# UCirKitBreadboardWithEverything2Top.net
KiCad netlist of a schematic drawn in EAGLE
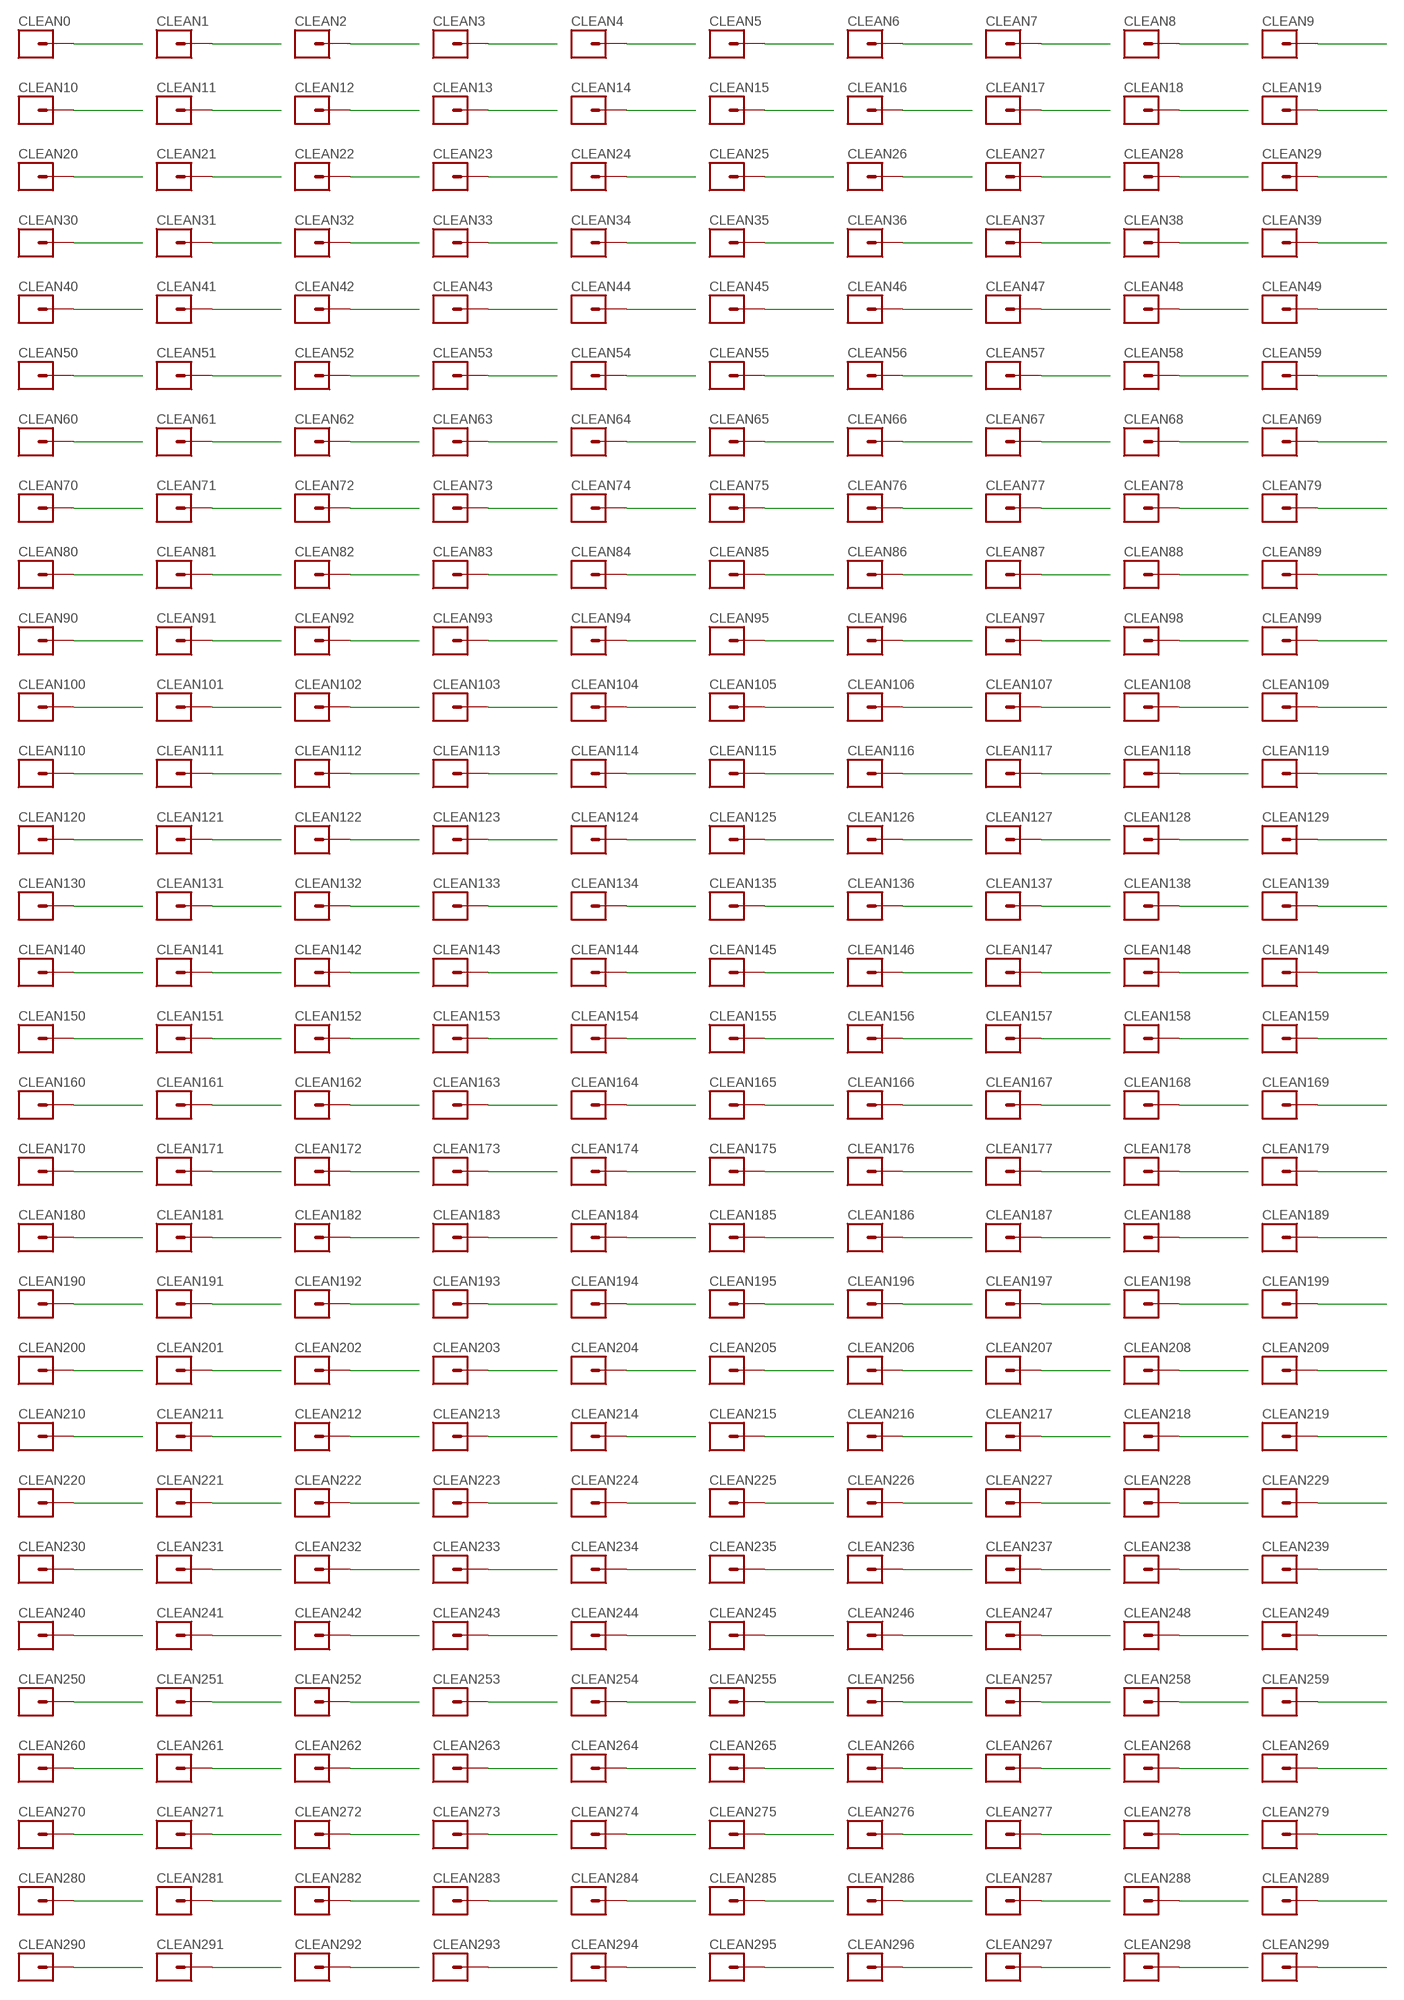
[diagram p0: schematic, sheet 1, part 1 of 2]
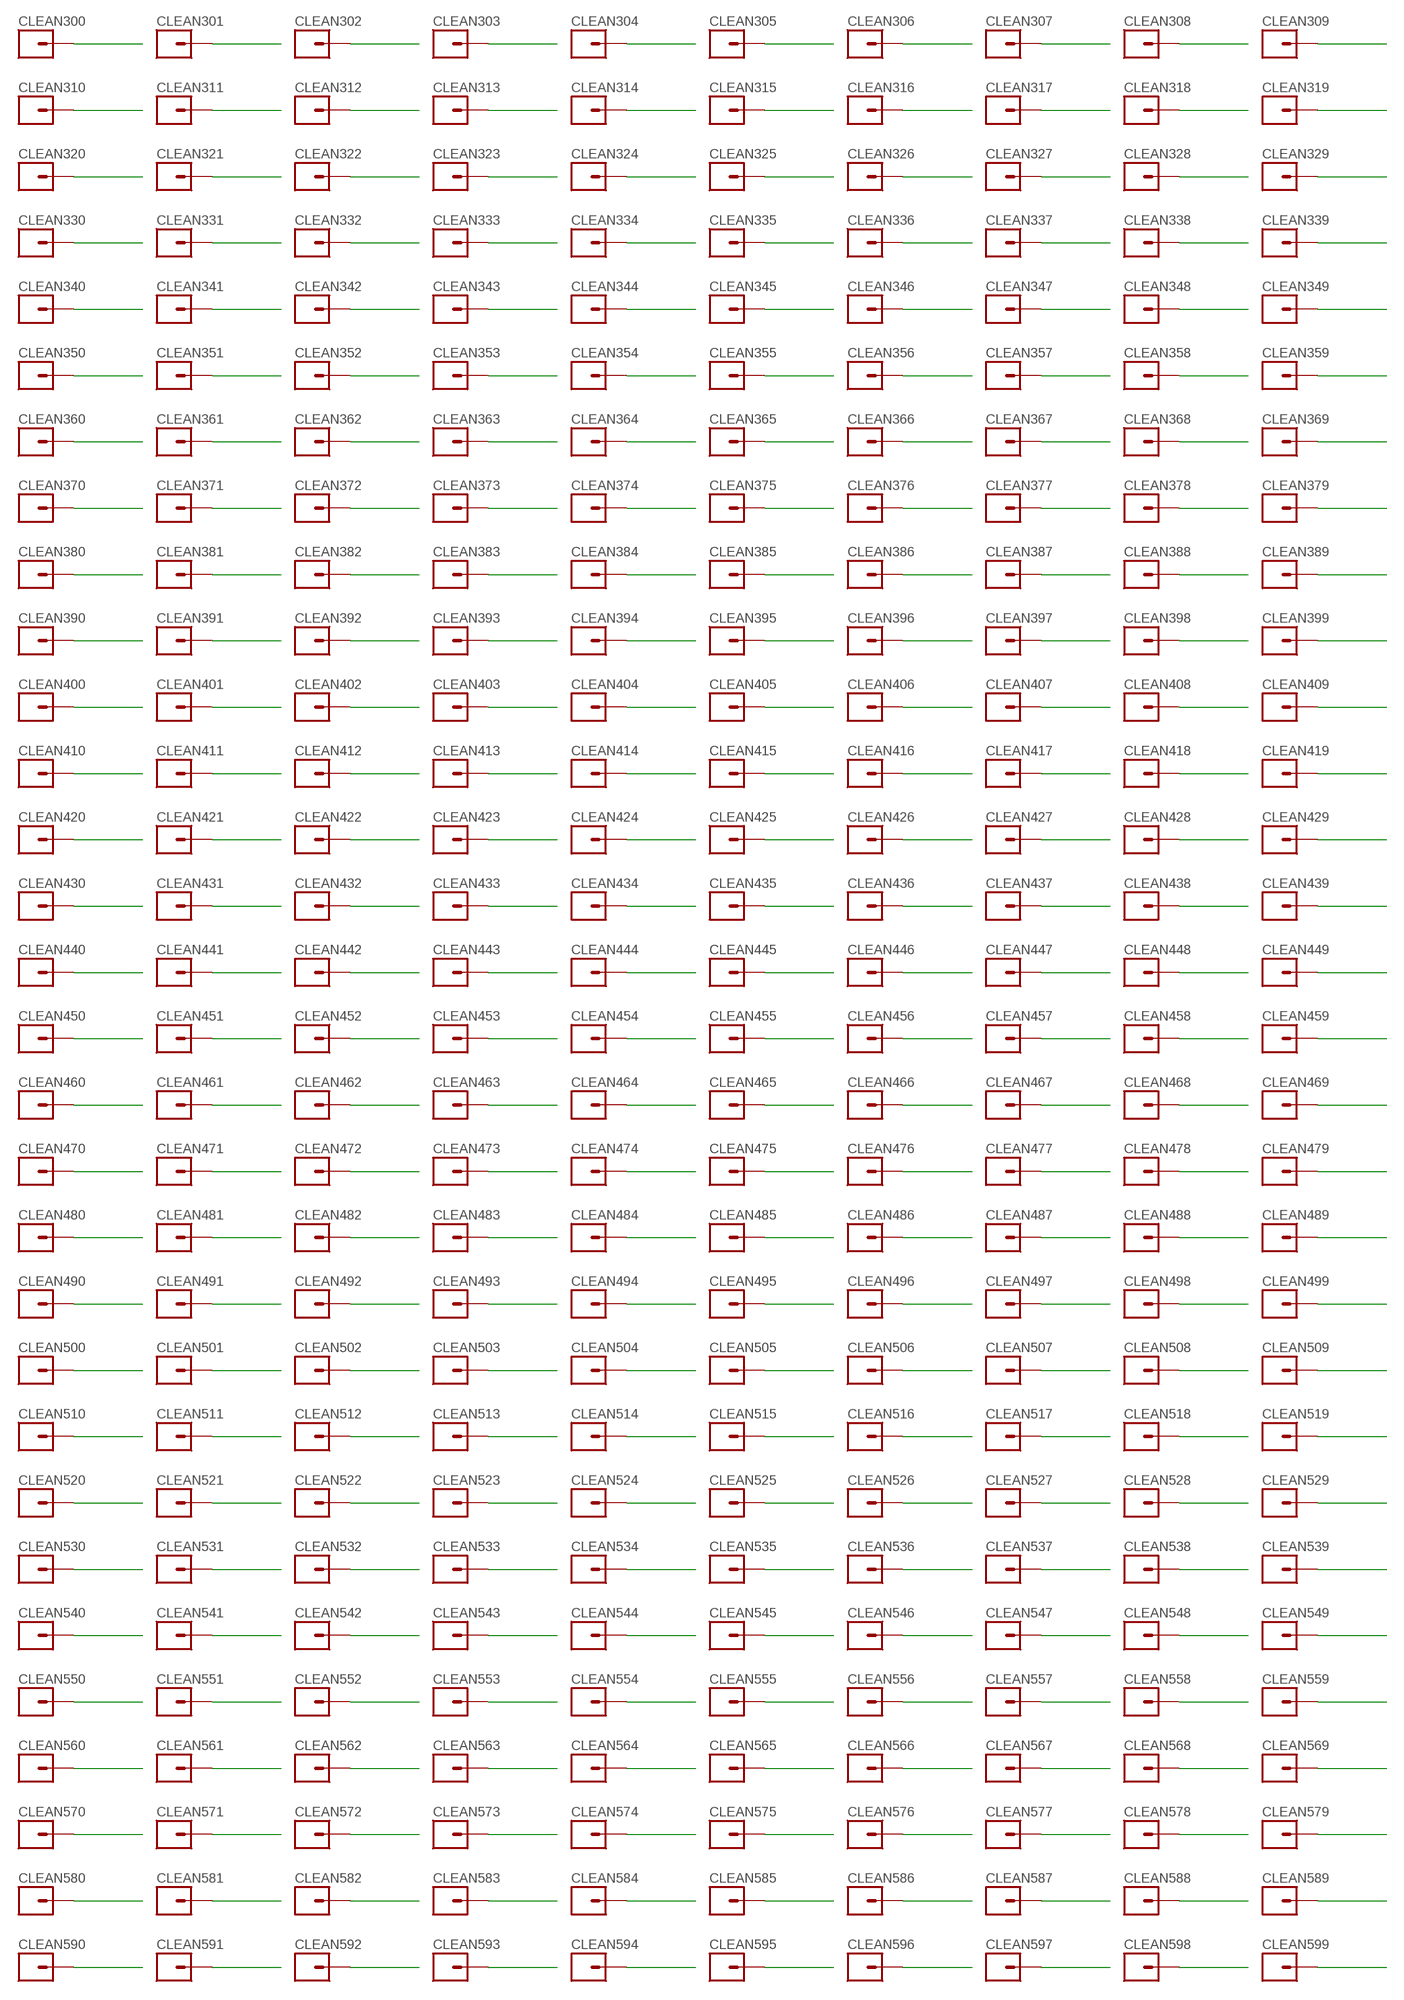
[diagram p1: schematic, sheet 1, part 2 of 2]

(export (version "E")
  (design (tool "Eeschema 10.0.6"))
  (components
    (comp (ref "CLEAN0")
      (value "M01PTH_WITHOUT_TEXT")
      (footprint "eagle-import:1X01_WITHOUT_TEXT")
      (libsource (lib "eagle-import") (part "M01PTH_WITHOUT_TEXT"))
    )
    (comp (ref "CLEAN1")
      (value "M01PTH_WITHOUT_TEXT")
      (footprint "eagle-import:1X01_WITHOUT_TEXT")
      (libsource (lib "eagle-import") (part "M01PTH_WITHOUT_TEXT"))
    )
    (comp (ref "CLEAN2")
      (value "M01PTH_WITHOUT_TEXT")
      (footprint "eagle-import:1X01_WITHOUT_TEXT")
      (libsource (lib "eagle-import") (part "M01PTH_WITHOUT_TEXT"))
    )
    (comp (ref "CLEAN3")
      (value "M01PTH_WITHOUT_TEXT")
      (footprint "eagle-import:1X01_WITHOUT_TEXT")
      (libsource (lib "eagle-import") (part "M01PTH_WITHOUT_TEXT"))
    )
    (comp (ref "CLEAN4")
      (value "M01PTH_WITHOUT_TEXT")
      (footprint "eagle-import:1X01_WITHOUT_TEXT")
      (libsource (lib "eagle-import") (part "M01PTH_WITHOUT_TEXT"))
    )
    (comp (ref "CLEAN5")
      (value "M01PTH_WITHOUT_TEXT")
      (footprint "eagle-import:1X01_WITHOUT_TEXT")
      (libsource (lib "eagle-import") (part "M01PTH_WITHOUT_TEXT"))
    )
    (comp (ref "CLEAN6")
      (value "M01PTH_WITHOUT_TEXT")
      (footprint "eagle-import:1X01_WITHOUT_TEXT")
      (libsource (lib "eagle-import") (part "M01PTH_WITHOUT_TEXT"))
    )
    (comp (ref "CLEAN7")
      (value "M01PTH_WITHOUT_TEXT")
      (footprint "eagle-import:1X01_WITHOUT_TEXT")
      (libsource (lib "eagle-import") (part "M01PTH_WITHOUT_TEXT"))
    )
    (comp (ref "CLEAN8")
      (value "M01PTH_WITHOUT_TEXT")
      (footprint "eagle-import:1X01_WITHOUT_TEXT")
      (libsource (lib "eagle-import") (part "M01PTH_WITHOUT_TEXT"))
    )
    (comp (ref "CLEAN9")
      (value "M01PTH_WITHOUT_TEXT")
      (footprint "eagle-import:1X01_WITHOUT_TEXT")
      (libsource (lib "eagle-import") (part "M01PTH_WITHOUT_TEXT"))
    )
    (comp (ref "CLEAN10")
      (value "M01PTH_WITHOUT_TEXT")
      (footprint "eagle-import:1X01_WITHOUT_TEXT")
      (libsource (lib "eagle-import") (part "M01PTH_WITHOUT_TEXT"))
    )
    (comp (ref "CLEAN11")
      (value "M01PTH_WITHOUT_TEXT")
      (footprint "eagle-import:1X01_WITHOUT_TEXT")
      (libsource (lib "eagle-import") (part "M01PTH_WITHOUT_TEXT"))
    )
    (comp (ref "CLEAN12")
      (value "M01PTH_WITHOUT_TEXT")
      (footprint "eagle-import:1X01_WITHOUT_TEXT")
      (libsource (lib "eagle-import") (part "M01PTH_WITHOUT_TEXT"))
    )
    (comp (ref "CLEAN13")
      (value "M01PTH_WITHOUT_TEXT")
      (footprint "eagle-import:1X01_WITHOUT_TEXT")
      (libsource (lib "eagle-import") (part "M01PTH_WITHOUT_TEXT"))
    )
    (comp (ref "CLEAN14")
      (value "M01PTH_WITHOUT_TEXT")
      (footprint "eagle-import:1X01_WITHOUT_TEXT")
      (libsource (lib "eagle-import") (part "M01PTH_WITHOUT_TEXT"))
    )
    (comp (ref "CLEAN15")
      (value "M01PTH_WITHOUT_TEXT")
      (footprint "eagle-import:1X01_WITHOUT_TEXT")
      (libsource (lib "eagle-import") (part "M01PTH_WITHOUT_TEXT"))
    )
    (comp (ref "CLEAN16")
      (value "M01PTH_WITHOUT_TEXT")
      (footprint "eagle-import:1X01_WITHOUT_TEXT")
      (libsource (lib "eagle-import") (part "M01PTH_WITHOUT_TEXT"))
    )
    (comp (ref "CLEAN17")
      (value "M01PTH_WITHOUT_TEXT")
      (footprint "eagle-import:1X01_WITHOUT_TEXT")
      (libsource (lib "eagle-import") (part "M01PTH_WITHOUT_TEXT"))
    )
    (comp (ref "CLEAN18")
      (value "M01PTH_WITHOUT_TEXT")
      (footprint "eagle-import:1X01_WITHOUT_TEXT")
      (libsource (lib "eagle-import") (part "M01PTH_WITHOUT_TEXT"))
    )
    (comp (ref "CLEAN19")
      (value "M01PTH_WITHOUT_TEXT")
      (footprint "eagle-import:1X01_WITHOUT_TEXT")
      (libsource (lib "eagle-import") (part "M01PTH_WITHOUT_TEXT"))
    )
    (comp (ref "CLEAN20")
      (value "M01PTH_WITHOUT_TEXT")
      (footprint "eagle-import:1X01_WITHOUT_TEXT")
      (libsource (lib "eagle-import") (part "M01PTH_WITHOUT_TEXT"))
    )
    (comp (ref "CLEAN21")
      (value "M01PTH_WITHOUT_TEXT")
      (footprint "eagle-import:1X01_WITHOUT_TEXT")
      (libsource (lib "eagle-import") (part "M01PTH_WITHOUT_TEXT"))
    )
    (comp (ref "CLEAN22")
      (value "M01PTH_WITHOUT_TEXT")
      (footprint "eagle-import:1X01_WITHOUT_TEXT")
      (libsource (lib "eagle-import") (part "M01PTH_WITHOUT_TEXT"))
    )
    (comp (ref "CLEAN23")
      (value "M01PTH_WITHOUT_TEXT")
      (footprint "eagle-import:1X01_WITHOUT_TEXT")
      (libsource (lib "eagle-import") (part "M01PTH_WITHOUT_TEXT"))
    )
    (comp (ref "CLEAN24")
      (value "M01PTH_WITHOUT_TEXT")
      (footprint "eagle-import:1X01_WITHOUT_TEXT")
      (libsource (lib "eagle-import") (part "M01PTH_WITHOUT_TEXT"))
    )
    (comp (ref "CLEAN25")
      (value "M01PTH_WITHOUT_TEXT")
      (footprint "eagle-import:1X01_WITHOUT_TEXT")
      (libsource (lib "eagle-import") (part "M01PTH_WITHOUT_TEXT"))
    )
    (comp (ref "CLEAN26")
      (value "M01PTH_WITHOUT_TEXT")
      (footprint "eagle-import:1X01_WITHOUT_TEXT")
      (libsource (lib "eagle-import") (part "M01PTH_WITHOUT_TEXT"))
    )
    (comp (ref "CLEAN27")
      (value "M01PTH_WITHOUT_TEXT")
      (footprint "eagle-import:1X01_WITHOUT_TEXT")
      (libsource (lib "eagle-import") (part "M01PTH_WITHOUT_TEXT"))
    )
    (comp (ref "CLEAN28")
      (value "M01PTH_WITHOUT_TEXT")
      (footprint "eagle-import:1X01_WITHOUT_TEXT")
      (libsource (lib "eagle-import") (part "M01PTH_WITHOUT_TEXT"))
    )
    (comp (ref "CLEAN29")
      (value "M01PTH_WITHOUT_TEXT")
      (footprint "eagle-import:1X01_WITHOUT_TEXT")
      (libsource (lib "eagle-import") (part "M01PTH_WITHOUT_TEXT"))
    )
    (comp (ref "CLEAN30")
      (value "M01PTH_WITHOUT_TEXT")
      (footprint "eagle-import:1X01_WITHOUT_TEXT")
      (libsource (lib "eagle-import") (part "M01PTH_WITHOUT_TEXT"))
    )
    (comp (ref "CLEAN31")
      (value "M01PTH_WITHOUT_TEXT")
      (footprint "eagle-import:1X01_WITHOUT_TEXT")
      (libsource (lib "eagle-import") (part "M01PTH_WITHOUT_TEXT"))
    )
    (comp (ref "CLEAN32")
      (value "M01PTH_WITHOUT_TEXT")
      (footprint "eagle-import:1X01_WITHOUT_TEXT")
      (libsource (lib "eagle-import") (part "M01PTH_WITHOUT_TEXT"))
    )
    (comp (ref "CLEAN33")
      (value "M01PTH_WITHOUT_TEXT")
      (footprint "eagle-import:1X01_WITHOUT_TEXT")
      (libsource (lib "eagle-import") (part "M01PTH_WITHOUT_TEXT"))
    )
    (comp (ref "CLEAN34")
      (value "M01PTH_WITHOUT_TEXT")
      (footprint "eagle-import:1X01_WITHOUT_TEXT")
      (libsource (lib "eagle-import") (part "M01PTH_WITHOUT_TEXT"))
    )
    (comp (ref "CLEAN35")
      (value "M01PTH_WITHOUT_TEXT")
      (footprint "eagle-import:1X01_WITHOUT_TEXT")
      (libsource (lib "eagle-import") (part "M01PTH_WITHOUT_TEXT"))
    )
    (comp (ref "CLEAN36")
      (value "M01PTH_WITHOUT_TEXT")
      (footprint "eagle-import:1X01_WITHOUT_TEXT")
      (libsource (lib "eagle-import") (part "M01PTH_WITHOUT_TEXT"))
    )
    (comp (ref "CLEAN37")
      (value "M01PTH_WITHOUT_TEXT")
      (footprint "eagle-import:1X01_WITHOUT_TEXT")
      (libsource (lib "eagle-import") (part "M01PTH_WITHOUT_TEXT"))
    )
    (comp (ref "CLEAN38")
      (value "M01PTH_WITHOUT_TEXT")
      (footprint "eagle-import:1X01_WITHOUT_TEXT")
      (libsource (lib "eagle-import") (part "M01PTH_WITHOUT_TEXT"))
    )
    (comp (ref "CLEAN39")
      (value "M01PTH_WITHOUT_TEXT")
      (footprint "eagle-import:1X01_WITHOUT_TEXT")
      (libsource (lib "eagle-import") (part "M01PTH_WITHOUT_TEXT"))
    )
    (comp (ref "CLEAN40")
      (value "M01PTH_WITHOUT_TEXT")
      (footprint "eagle-import:1X01_WITHOUT_TEXT")
      (libsource (lib "eagle-import") (part "M01PTH_WITHOUT_TEXT"))
    )
    (comp (ref "CLEAN41")
      (value "M01PTH_WITHOUT_TEXT")
      (footprint "eagle-import:1X01_WITHOUT_TEXT")
      (libsource (lib "eagle-import") (part "M01PTH_WITHOUT_TEXT"))
    )
    (comp (ref "CLEAN42")
      (value "M01PTH_WITHOUT_TEXT")
      (footprint "eagle-import:1X01_WITHOUT_TEXT")
      (libsource (lib "eagle-import") (part "M01PTH_WITHOUT_TEXT"))
    )
    (comp (ref "CLEAN43")
      (value "M01PTH_WITHOUT_TEXT")
      (footprint "eagle-import:1X01_WITHOUT_TEXT")
      (libsource (lib "eagle-import") (part "M01PTH_WITHOUT_TEXT"))
    )
    (comp (ref "CLEAN44")
      (value "M01PTH_WITHOUT_TEXT")
      (footprint "eagle-import:1X01_WITHOUT_TEXT")
      (libsource (lib "eagle-import") (part "M01PTH_WITHOUT_TEXT"))
    )
    (comp (ref "CLEAN45")
      (value "M01PTH_WITHOUT_TEXT")
      (footprint "eagle-import:1X01_WITHOUT_TEXT")
      (libsource (lib "eagle-import") (part "M01PTH_WITHOUT_TEXT"))
    )
    (comp (ref "CLEAN46")
      (value "M01PTH_WITHOUT_TEXT")
      (footprint "eagle-import:1X01_WITHOUT_TEXT")
      (libsource (lib "eagle-import") (part "M01PTH_WITHOUT_TEXT"))
    )
    (comp (ref "CLEAN47")
      (value "M01PTH_WITHOUT_TEXT")
      (footprint "eagle-import:1X01_WITHOUT_TEXT")
      (libsource (lib "eagle-import") (part "M01PTH_WITHOUT_TEXT"))
    )
    (comp (ref "CLEAN48")
      (value "M01PTH_WITHOUT_TEXT")
      (footprint "eagle-import:1X01_WITHOUT_TEXT")
      (libsource (lib "eagle-import") (part "M01PTH_WITHOUT_TEXT"))
    )
    (comp (ref "CLEAN49")
      (value "M01PTH_WITHOUT_TEXT")
      (footprint "eagle-import:1X01_WITHOUT_TEXT")
      (libsource (lib "eagle-import") (part "M01PTH_WITHOUT_TEXT"))
    )
    (comp (ref "CLEAN50")
      (value "M01PTH_WITHOUT_TEXT")
      (footprint "eagle-import:1X01_WITHOUT_TEXT")
      (libsource (lib "eagle-import") (part "M01PTH_WITHOUT_TEXT"))
    )
    (comp (ref "CLEAN51")
      (value "M01PTH_WITHOUT_TEXT")
      (footprint "eagle-import:1X01_WITHOUT_TEXT")
      (libsource (lib "eagle-import") (part "M01PTH_WITHOUT_TEXT"))
    )
    (comp (ref "CLEAN52")
      (value "M01PTH_WITHOUT_TEXT")
      (footprint "eagle-import:1X01_WITHOUT_TEXT")
      (libsource (lib "eagle-import") (part "M01PTH_WITHOUT_TEXT"))
    )
    (comp (ref "CLEAN53")
      (value "M01PTH_WITHOUT_TEXT")
      (footprint "eagle-import:1X01_WITHOUT_TEXT")
      (libsource (lib "eagle-import") (part "M01PTH_WITHOUT_TEXT"))
    )
    (comp (ref "CLEAN54")
      (value "M01PTH_WITHOUT_TEXT")
      (footprint "eagle-import:1X01_WITHOUT_TEXT")
      (libsource (lib "eagle-import") (part "M01PTH_WITHOUT_TEXT"))
    )
    (comp (ref "CLEAN55")
      (value "M01PTH_WITHOUT_TEXT")
      (footprint "eagle-import:1X01_WITHOUT_TEXT")
      (libsource (lib "eagle-import") (part "M01PTH_WITHOUT_TEXT"))
    )
    (comp (ref "CLEAN56")
      (value "M01PTH_WITHOUT_TEXT")
      (footprint "eagle-import:1X01_WITHOUT_TEXT")
      (libsource (lib "eagle-import") (part "M01PTH_WITHOUT_TEXT"))
    )
    (comp (ref "CLEAN57")
      (value "M01PTH_WITHOUT_TEXT")
      (footprint "eagle-import:1X01_WITHOUT_TEXT")
      (libsource (lib "eagle-import") (part "M01PTH_WITHOUT_TEXT"))
    )
    (comp (ref "CLEAN58")
      (value "M01PTH_WITHOUT_TEXT")
      (footprint "eagle-import:1X01_WITHOUT_TEXT")
      (libsource (lib "eagle-import") (part "M01PTH_WITHOUT_TEXT"))
    )
    (comp (ref "CLEAN59")
      (value "M01PTH_WITHOUT_TEXT")
      (footprint "eagle-import:1X01_WITHOUT_TEXT")
      (libsource (lib "eagle-import") (part "M01PTH_WITHOUT_TEXT"))
    )
    (comp (ref "CLEAN60")
      (value "M01PTH_WITHOUT_TEXT")
      (footprint "eagle-import:1X01_WITHOUT_TEXT")
      (libsource (lib "eagle-import") (part "M01PTH_WITHOUT_TEXT"))
    )
    (comp (ref "CLEAN61")
      (value "M01PTH_WITHOUT_TEXT")
      (footprint "eagle-import:1X01_WITHOUT_TEXT")
      (libsource (lib "eagle-import") (part "M01PTH_WITHOUT_TEXT"))
    )
    (comp (ref "CLEAN62")
      (value "M01PTH_WITHOUT_TEXT")
      (footprint "eagle-import:1X01_WITHOUT_TEXT")
      (libsource (lib "eagle-import") (part "M01PTH_WITHOUT_TEXT"))
    )
    (comp (ref "CLEAN63")
      (value "M01PTH_WITHOUT_TEXT")
      (footprint "eagle-import:1X01_WITHOUT_TEXT")
      (libsource (lib "eagle-import") (part "M01PTH_WITHOUT_TEXT"))
    )
    (comp (ref "CLEAN64")
      (value "M01PTH_WITHOUT_TEXT")
      (footprint "eagle-import:1X01_WITHOUT_TEXT")
      (libsource (lib "eagle-import") (part "M01PTH_WITHOUT_TEXT"))
    )
    (comp (ref "CLEAN65")
      (value "M01PTH_WITHOUT_TEXT")
      (footprint "eagle-import:1X01_WITHOUT_TEXT")
      (libsource (lib "eagle-import") (part "M01PTH_WITHOUT_TEXT"))
    )
    (comp (ref "CLEAN66")
      (value "M01PTH_WITHOUT_TEXT")
      (footprint "eagle-import:1X01_WITHOUT_TEXT")
      (libsource (lib "eagle-import") (part "M01PTH_WITHOUT_TEXT"))
    )
    (comp (ref "CLEAN67")
      (value "M01PTH_WITHOUT_TEXT")
      (footprint "eagle-import:1X01_WITHOUT_TEXT")
      (libsource (lib "eagle-import") (part "M01PTH_WITHOUT_TEXT"))
    )
    (comp (ref "CLEAN68")
      (value "M01PTH_WITHOUT_TEXT")
      (footprint "eagle-import:1X01_WITHOUT_TEXT")
      (libsource (lib "eagle-import") (part "M01PTH_WITHOUT_TEXT"))
    )
    (comp (ref "CLEAN69")
      (value "M01PTH_WITHOUT_TEXT")
      (footprint "eagle-import:1X01_WITHOUT_TEXT")
      (libsource (lib "eagle-import") (part "M01PTH_WITHOUT_TEXT"))
    )
    (comp (ref "CLEAN70")
      (value "M01PTH_WITHOUT_TEXT")
      (footprint "eagle-import:1X01_WITHOUT_TEXT")
      (libsource (lib "eagle-import") (part "M01PTH_WITHOUT_TEXT"))
    )
    (comp (ref "CLEAN71")
      (value "M01PTH_WITHOUT_TEXT")
      (footprint "eagle-import:1X01_WITHOUT_TEXT")
      (libsource (lib "eagle-import") (part "M01PTH_WITHOUT_TEXT"))
    )
    (comp (ref "CLEAN72")
      (value "M01PTH_WITHOUT_TEXT")
      (footprint "eagle-import:1X01_WITHOUT_TEXT")
      (libsource (lib "eagle-import") (part "M01PTH_WITHOUT_TEXT"))
    )
    (comp (ref "CLEAN73")
      (value "M01PTH_WITHOUT_TEXT")
      (footprint "eagle-import:1X01_WITHOUT_TEXT")
      (libsource (lib "eagle-import") (part "M01PTH_WITHOUT_TEXT"))
    )
    (comp (ref "CLEAN74")
      (value "M01PTH_WITHOUT_TEXT")
      (footprint "eagle-import:1X01_WITHOUT_TEXT")
      (libsource (lib "eagle-import") (part "M01PTH_WITHOUT_TEXT"))
    )
    (comp (ref "CLEAN75")
      (value "M01PTH_WITHOUT_TEXT")
      (footprint "eagle-import:1X01_WITHOUT_TEXT")
      (libsource (lib "eagle-import") (part "M01PTH_WITHOUT_TEXT"))
    )
    (comp (ref "CLEAN76")
      (value "M01PTH_WITHOUT_TEXT")
      (footprint "eagle-import:1X01_WITHOUT_TEXT")
      (libsource (lib "eagle-import") (part "M01PTH_WITHOUT_TEXT"))
    )
    (comp (ref "CLEAN77")
      (value "M01PTH_WITHOUT_TEXT")
      (footprint "eagle-import:1X01_WITHOUT_TEXT")
      (libsource (lib "eagle-import") (part "M01PTH_WITHOUT_TEXT"))
    )
    (comp (ref "CLEAN78")
      (value "M01PTH_WITHOUT_TEXT")
      (footprint "eagle-import:1X01_WITHOUT_TEXT")
      (libsource (lib "eagle-import") (part "M01PTH_WITHOUT_TEXT"))
    )
    (comp (ref "CLEAN79")
      (value "M01PTH_WITHOUT_TEXT")
      (footprint "eagle-import:1X01_WITHOUT_TEXT")
      (libsource (lib "eagle-import") (part "M01PTH_WITHOUT_TEXT"))
    )
    (comp (ref "CLEAN80")
      (value "M01PTH_WITHOUT_TEXT")
      (footprint "eagle-import:1X01_WITHOUT_TEXT")
      (libsource (lib "eagle-import") (part "M01PTH_WITHOUT_TEXT"))
    )
    (comp (ref "CLEAN81")
      (value "M01PTH_WITHOUT_TEXT")
      (footprint "eagle-import:1X01_WITHOUT_TEXT")
      (libsource (lib "eagle-import") (part "M01PTH_WITHOUT_TEXT"))
    )
    (comp (ref "CLEAN82")
      (value "M01PTH_WITHOUT_TEXT")
      (footprint "eagle-import:1X01_WITHOUT_TEXT")
      (libsource (lib "eagle-import") (part "M01PTH_WITHOUT_TEXT"))
    )
    (comp (ref "CLEAN83")
      (value "M01PTH_WITHOUT_TEXT")
      (footprint "eagle-import:1X01_WITHOUT_TEXT")
      (libsource (lib "eagle-import") (part "M01PTH_WITHOUT_TEXT"))
    )
    (comp (ref "CLEAN84")
      (value "M01PTH_WITHOUT_TEXT")
      (footprint "eagle-import:1X01_WITHOUT_TEXT")
      (libsource (lib "eagle-import") (part "M01PTH_WITHOUT_TEXT"))
    )
    (comp (ref "CLEAN85")
      (value "M01PTH_WITHOUT_TEXT")
      (footprint "eagle-import:1X01_WITHOUT_TEXT")
      (libsource (lib "eagle-import") (part "M01PTH_WITHOUT_TEXT"))
    )
    (comp (ref "CLEAN86")
      (value "M01PTH_WITHOUT_TEXT")
      (footprint "eagle-import:1X01_WITHOUT_TEXT")
      (libsource (lib "eagle-import") (part "M01PTH_WITHOUT_TEXT"))
    )
    (comp (ref "CLEAN87")
      (value "M01PTH_WITHOUT_TEXT")
      (footprint "eagle-import:1X01_WITHOUT_TEXT")
      (libsource (lib "eagle-import") (part "M01PTH_WITHOUT_TEXT"))
    )
    (comp (ref "CLEAN88")
      (value "M01PTH_WITHOUT_TEXT")
      (footprint "eagle-import:1X01_WITHOUT_TEXT")
      (libsource (lib "eagle-import") (part "M01PTH_WITHOUT_TEXT"))
    )
    (comp (ref "CLEAN89")
      (value "M01PTH_WITHOUT_TEXT")
      (footprint "eagle-import:1X01_WITHOUT_TEXT")
      (libsource (lib "eagle-import") (part "M01PTH_WITHOUT_TEXT"))
    )
    (comp (ref "CLEAN90")
      (value "M01PTH_WITHOUT_TEXT")
      (footprint "eagle-import:1X01_WITHOUT_TEXT")
      (libsource (lib "eagle-import") (part "M01PTH_WITHOUT_TEXT"))
    )
    (comp (ref "CLEAN91")
      (value "M01PTH_WITHOUT_TEXT")
      (footprint "eagle-import:1X01_WITHOUT_TEXT")
      (libsource (lib "eagle-import") (part "M01PTH_WITHOUT_TEXT"))
    )
    (comp (ref "CLEAN92")
      (value "M01PTH_WITHOUT_TEXT")
      (footprint "eagle-import:1X01_WITHOUT_TEXT")
      (libsource (lib "eagle-import") (part "M01PTH_WITHOUT_TEXT"))
    )
    (comp (ref "CLEAN93")
      (value "M01PTH_WITHOUT_TEXT")
      (footprint "eagle-import:1X01_WITHOUT_TEXT")
      (libsource (lib "eagle-import") (part "M01PTH_WITHOUT_TEXT"))
    )
    (comp (ref "CLEAN94")
      (value "M01PTH_WITHOUT_TEXT")
      (footprint "eagle-import:1X01_WITHOUT_TEXT")
      (libsource (lib "eagle-import") (part "M01PTH_WITHOUT_TEXT"))
    )
    (comp (ref "CLEAN95")
      (value "M01PTH_WITHOUT_TEXT")
      (footprint "eagle-import:1X01_WITHOUT_TEXT")
      (libsource (lib "eagle-import") (part "M01PTH_WITHOUT_TEXT"))
    )
    (comp (ref "CLEAN96")
      (value "M01PTH_WITHOUT_TEXT")
      (footprint "eagle-import:1X01_WITHOUT_TEXT")
      (libsource (lib "eagle-import") (part "M01PTH_WITHOUT_TEXT"))
    )
    (comp (ref "CLEAN97")
      (value "M01PTH_WITHOUT_TEXT")
      (footprint "eagle-import:1X01_WITHOUT_TEXT")
      (libsource (lib "eagle-import") (part "M01PTH_WITHOUT_TEXT"))
    )
    (comp (ref "CLEAN98")
      (value "M01PTH_WITHOUT_TEXT")
      (footprint "eagle-import:1X01_WITHOUT_TEXT")
      (libsource (lib "eagle-import") (part "M01PTH_WITHOUT_TEXT"))
    )
    (comp (ref "CLEAN99")
      (value "M01PTH_WITHOUT_TEXT")
      (footprint "eagle-import:1X01_WITHOUT_TEXT")
      (libsource (lib "eagle-import") (part "M01PTH_WITHOUT_TEXT"))
    )
    (comp (ref "CLEAN100")
      (value "M01PTH_WITHOUT_TEXT")
      (footprint "eagle-import:1X01_WITHOUT_TEXT")
      (libsource (lib "eagle-import") (part "M01PTH_WITHOUT_TEXT"))
    )
    (comp (ref "CLEAN101")
      (value "M01PTH_WITHOUT_TEXT")
      (footprint "eagle-import:1X01_WITHOUT_TEXT")
      (libsource (lib "eagle-import") (part "M01PTH_WITHOUT_TEXT"))
    )
    (comp (ref "CLEAN102")
      (value "M01PTH_WITHOUT_TEXT")
      (footprint "eagle-import:1X01_WITHOUT_TEXT")
      (libsource (lib "eagle-import") (part "M01PTH_WITHOUT_TEXT"))
    )
    (comp (ref "CLEAN103")
      (value "M01PTH_WITHOUT_TEXT")
      (footprint "eagle-import:1X01_WITHOUT_TEXT")
      (libsource (lib "eagle-import") (part "M01PTH_WITHOUT_TEXT"))
    )
    (comp (ref "CLEAN104")
      (value "M01PTH_WITHOUT_TEXT")
      (footprint "eagle-import:1X01_WITHOUT_TEXT")
      (libsource (lib "eagle-import") (part "M01PTH_WITHOUT_TEXT"))
    )
    (comp (ref "CLEAN105")
      (value "M01PTH_WITHOUT_TEXT")
      (footprint "eagle-import:1X01_WITHOUT_TEXT")
      (libsource (lib "eagle-import") (part "M01PTH_WITHOUT_TEXT"))
    )
    (comp (ref "CLEAN106")
      (value "M01PTH_WITHOUT_TEXT")
      (footprint "eagle-import:1X01_WITHOUT_TEXT")
      (libsource (lib "eagle-import") (part "M01PTH_WITHOUT_TEXT"))
    )
    (comp (ref "CLEAN107")
      (value "M01PTH_WITHOUT_TEXT")
      (footprint "eagle-import:1X01_WITHOUT_TEXT")
      (libsource (lib "eagle-import") (part "M01PTH_WITHOUT_TEXT"))
    )
    (comp (ref "CLEAN108")
      (value "M01PTH_WITHOUT_TEXT")
      (footprint "eagle-import:1X01_WITHOUT_TEXT")
      (libsource (lib "eagle-import") (part "M01PTH_WITHOUT_TEXT"))
    )
    (comp (ref "CLEAN109")
      (value "M01PTH_WITHOUT_TEXT")
      (footprint "eagle-import:1X01_WITHOUT_TEXT")
      (libsource (lib "eagle-import") (part "M01PTH_WITHOUT_TEXT"))
    )
    (comp (ref "CLEAN110")
      (value "M01PTH_WITHOUT_TEXT")
      (footprint "eagle-import:1X01_WITHOUT_TEXT")
      (libsource (lib "eagle-import") (part "M01PTH_WITHOUT_TEXT"))
    )
    (comp (ref "CLEAN111")
      (value "M01PTH_WITHOUT_TEXT")
      (footprint "eagle-import:1X01_WITHOUT_TEXT")
      (libsource (lib "eagle-import") (part "M01PTH_WITHOUT_TEXT"))
    )
    (comp (ref "CLEAN112")
      (value "M01PTH_WITHOUT_TEXT")
      (footprint "eagle-import:1X01_WITHOUT_TEXT")
      (libsource (lib "eagle-import") (part "M01PTH_WITHOUT_TEXT"))
    )
    (comp (ref "CLEAN113")
      (value "M01PTH_WITHOUT_TEXT")
      (footprint "eagle-import:1X01_WITHOUT_TEXT")
      (libsource (lib "eagle-import") (part "M01PTH_WITHOUT_TEXT"))
    )
    (comp (ref "CLEAN114")
      (value "M01PTH_WITHOUT_TEXT")
      (footprint "eagle-import:1X01_WITHOUT_TEXT")
      (libsource (lib "eagle-import") (part "M01PTH_WITHOUT_TEXT"))
    )
    (comp (ref "CLEAN115")
      (value "M01PTH_WITHOUT_TEXT")
      (footprint "eagle-import:1X01_WITHOUT_TEXT")
      (libsource (lib "eagle-import") (part "M01PTH_WITHOUT_TEXT"))
    )
    (comp (ref "CLEAN116")
      (value "M01PTH_WITHOUT_TEXT")
      (footprint "eagle-import:1X01_WITHOUT_TEXT")
      (libsource (lib "eagle-import") (part "M01PTH_WITHOUT_TEXT"))
    )
    (comp (ref "CLEAN117")
      (value "M01PTH_WITHOUT_TEXT")
      (footprint "eagle-import:1X01_WITHOUT_TEXT")
      (libsource (lib "eagle-import") (part "M01PTH_WITHOUT_TEXT"))
    )
    (comp (ref "CLEAN118")
      (value "M01PTH_WITHOUT_TEXT")
      (footprint "eagle-import:1X01_WITHOUT_TEXT")
      (libsource (lib "eagle-import") (part "M01PTH_WITHOUT_TEXT"))
    )
    (comp (ref "CLEAN119")
      (value "M01PTH_WITHOUT_TEXT")
      (footprint "eagle-import:1X01_WITHOUT_TEXT")
      (libsource (lib "eagle-import") (part "M01PTH_WITHOUT_TEXT"))
    )
    (comp (ref "CLEAN120")
      (value "M01PTH_WITHOUT_TEXT")
      (footprint "eagle-import:1X01_WITHOUT_TEXT")
      (libsource (lib "eagle-import") (part "M01PTH_WITHOUT_TEXT"))
    )
    (comp (ref "CLEAN121")
      (value "M01PTH_WITHOUT_TEXT")
      (footprint "eagle-import:1X01_WITHOUT_TEXT")
      (libsource (lib "eagle-import") (part "M01PTH_WITHOUT_TEXT"))
    )
    (comp (ref "CLEAN122")
      (value "M01PTH_WITHOUT_TEXT")
      (footprint "eagle-import:1X01_WITHOUT_TEXT")
      (libsource (lib "eagle-import") (part "M01PTH_WITHOUT_TEXT"))
    )
    (comp (ref "CLEAN123")
      (value "M01PTH_WITHOUT_TEXT")
      (footprint "eagle-import:1X01_WITHOUT_TEXT")
      (libsource (lib "eagle-import") (part "M01PTH_WITHOUT_TEXT"))
    )
    (comp (ref "CLEAN124")
      (value "M01PTH_WITHOUT_TEXT")
      (footprint "eagle-import:1X01_WITHOUT_TEXT")
      (libsource (lib "eagle-import") (part "M01PTH_WITHOUT_TEXT"))
    )
    (comp (ref "CLEAN125")
      (value "M01PTH_WITHOUT_TEXT")
      (footprint "eagle-import:1X01_WITHOUT_TEXT")
      (libsource (lib "eagle-import") (part "M01PTH_WITHOUT_TEXT"))
    )
    (comp (ref "CLEAN126")
      (value "M01PTH_WITHOUT_TEXT")
      (footprint "eagle-import:1X01_WITHOUT_TEXT")
      (libsource (lib "eagle-import") (part "M01PTH_WITHOUT_TEXT"))
    )
    (comp (ref "CLEAN127")
      (value "M01PTH_WITHOUT_TEXT")
      (footprint "eagle-import:1X01_WITHOUT_TEXT")
      (libsource (lib "eagle-import") (part "M01PTH_WITHOUT_TEXT"))
    )
    (comp (ref "CLEAN128")
      (value "M01PTH_WITHOUT_TEXT")
      (footprint "eagle-import:1X01_WITHOUT_TEXT")
      (libsource (lib "eagle-import") (part "M01PTH_WITHOUT_TEXT"))
    )
    (comp (ref "CLEAN129")
      (value "M01PTH_WITHOUT_TEXT")
      (footprint "eagle-import:1X01_WITHOUT_TEXT")
      (libsource (lib "eagle-import") (part "M01PTH_WITHOUT_TEXT"))
    )
    (comp (ref "CLEAN130")
      (value "M01PTH_WITHOUT_TEXT")
      (footprint "eagle-import:1X01_WITHOUT_TEXT")
      (libsource (lib "eagle-import") (part "M01PTH_WITHOUT_TEXT"))
    )
    (comp (ref "CLEAN131")
      (value "M01PTH_WITHOUT_TEXT")
      (footprint "eagle-import:1X01_WITHOUT_TEXT")
      (libsource (lib "eagle-import") (part "M01PTH_WITHOUT_TEXT"))
    )
    (comp (ref "CLEAN132")
      (value "M01PTH_WITHOUT_TEXT")
      (footprint "eagle-import:1X01_WITHOUT_TEXT")
      (libsource (lib "eagle-import") (part "M01PTH_WITHOUT_TEXT"))
    )
    (comp (ref "CLEAN133")
      (value "M01PTH_WITHOUT_TEXT")
      (footprint "eagle-import:1X01_WITHOUT_TEXT")
      (libsource (lib "eagle-import") (part "M01PTH_WITHOUT_TEXT"))
    )
    (comp (ref "CLEAN134")
      (value "M01PTH_WITHOUT_TEXT")
      (footprint "eagle-import:1X01_WITHOUT_TEXT")
      (libsource (lib "eagle-import") (part "M01PTH_WITHOUT_TEXT"))
    )
    (comp (ref "CLEAN135")
      (value "M01PTH_WITHOUT_TEXT")
      (footprint "eagle-import:1X01_WITHOUT_TEXT")
      (libsource (lib "eagle-import") (part "M01PTH_WITHOUT_TEXT"))
    )
    (comp (ref "CLEAN136")
      (value "M01PTH_WITHOUT_TEXT")
      (footprint "eagle-import:1X01_WITHOUT_TEXT")
      (libsource (lib "eagle-import") (part "M01PTH_WITHOUT_TEXT"))
    )
    (comp (ref "CLEAN137")
      (value "M01PTH_WITHOUT_TEXT")
      (footprint "eagle-import:1X01_WITHOUT_TEXT")
      (libsource (lib "eagle-import") (part "M01PTH_WITHOUT_TEXT"))
    )
    (comp (ref "CLEAN138")
      (value "M01PTH_WITHOUT_TEXT")
      (footprint "eagle-import:1X01_WITHOUT_TEXT")
      (libsource (lib "eagle-import") (part "M01PTH_WITHOUT_TEXT"))
    )
    (comp (ref "CLEAN139")
      (value "M01PTH_WITHOUT_TEXT")
      (footprint "eagle-import:1X01_WITHOUT_TEXT")
      (libsource (lib "eagle-import") (part "M01PTH_WITHOUT_TEXT"))
    )
    (comp (ref "CLEAN140")
      (value "M01PTH_WITHOUT_TEXT")
      (footprint "eagle-import:1X01_WITHOUT_TEXT")
      (libsource (lib "eagle-import") (part "M01PTH_WITHOUT_TEXT"))
    )
    (comp (ref "CLEAN141")
      (value "M01PTH_WITHOUT_TEXT")
      (footprint "eagle-import:1X01_WITHOUT_TEXT")
      (libsource (lib "eagle-import") (part "M01PTH_WITHOUT_TEXT"))
    )
    (comp (ref "CLEAN142")
      (value "M01PTH_WITHOUT_TEXT")
      (footprint "eagle-import:1X01_WITHOUT_TEXT")
      (libsource (lib "eagle-import") (part "M01PTH_WITHOUT_TEXT"))
    )
    (comp (ref "CLEAN143")
      (value "M01PTH_WITHOUT_TEXT")
      (footprint "eagle-import:1X01_WITHOUT_TEXT")
      (libsource (lib "eagle-import") (part "M01PTH_WITHOUT_TEXT"))
    )
    (comp (ref "CLEAN144")
      (value "M01PTH_WITHOUT_TEXT")
      (footprint "eagle-import:1X01_WITHOUT_TEXT")
      (libsource (lib "eagle-import") (part "M01PTH_WITHOUT_TEXT"))
    )
    (comp (ref "CLEAN145")
      (value "M01PTH_WITHOUT_TEXT")
      (footprint "eagle-import:1X01_WITHOUT_TEXT")
      (libsource (lib "eagle-import") (part "M01PTH_WITHOUT_TEXT"))
    )
    (comp (ref "CLEAN146")
      (value "M01PTH_WITHOUT_TEXT")
      (footprint "eagle-import:1X01_WITHOUT_TEXT")
      (libsource (lib "eagle-import") (part "M01PTH_WITHOUT_TEXT"))
    )
    (comp (ref "CLEAN147")
      (value "M01PTH_WITHOUT_TEXT")
      (footprint "eagle-import:1X01_WITHOUT_TEXT")
      (libsource (lib "eagle-import") (part "M01PTH_WITHOUT_TEXT"))
    )
    (comp (ref "CLEAN148")
      (value "M01PTH_WITHOUT_TEXT")
      (footprint "eagle-import:1X01_WITHOUT_TEXT")
      (libsource (lib "eagle-import") (part "M01PTH_WITHOUT_TEXT"))
    )
    (comp (ref "CLEAN149")
      (value "M01PTH_WITHOUT_TEXT")
      (footprint "eagle-import:1X01_WITHOUT_TEXT")
      (libsource (lib "eagle-import") (part "M01PTH_WITHOUT_TEXT"))
    )
    (comp (ref "CLEAN150")
      (value "M01PTH_WITHOUT_TEXT")
      (footprint "eagle-import:1X01_WITHOUT_TEXT")
      (libsource (lib "eagle-import") (part "M01PTH_WITHOUT_TEXT"))
    )
    (comp (ref "CLEAN151")
      (value "M01PTH_WITHOUT_TEXT")
      (footprint "eagle-import:1X01_WITHOUT_TEXT")
      (libsource (lib "eagle-import") (part "M01PTH_WITHOUT_TEXT"))
    )
    (comp (ref "CLEAN152")
      (value "M01PTH_WITHOUT_TEXT")
      (footprint "eagle-import:1X01_WITHOUT_TEXT")
      (libsource (lib "eagle-import") (part "M01PTH_WITHOUT_TEXT"))
    )
    (comp (ref "CLEAN153")
      (value "M01PTH_WITHOUT_TEXT")
      (footprint "eagle-import:1X01_WITHOUT_TEXT")
      (libsource (lib "eagle-import") (part "M01PTH_WITHOUT_TEXT"))
    )
    (comp (ref "CLEAN154")
      (value "M01PTH_WITHOUT_TEXT")
      (footprint "eagle-import:1X01_WITHOUT_TEXT")
      (libsource (lib "eagle-import") (part "M01PTH_WITHOUT_TEXT"))
    )
    (comp (ref "CLEAN155")
      (value "M01PTH_WITHOUT_TEXT")
      (footprint "eagle-import:1X01_WITHOUT_TEXT")
      (libsource (lib "eagle-import") (part "M01PTH_WITHOUT_TEXT"))
    )
    (comp (ref "CLEAN156")
      (value "M01PTH_WITHOUT_TEXT")
      (footprint "eagle-import:1X01_WITHOUT_TEXT")
      (libsource (lib "eagle-import") (part "M01PTH_WITHOUT_TEXT"))
    )
    (comp (ref "CLEAN157")
      (value "M01PTH_WITHOUT_TEXT")
      (footprint "eagle-import:1X01_WITHOUT_TEXT")
      (libsource (lib "eagle-import") (part "M01PTH_WITHOUT_TEXT"))
    )
    (comp (ref "CLEAN158")
      (value "M01PTH_WITHOUT_TEXT")
      (footprint "eagle-import:1X01_WITHOUT_TEXT")
      (libsource (lib "eagle-import") (part "M01PTH_WITHOUT_TEXT"))
    )
    (comp (ref "CLEAN159")
      (value "M01PTH_WITHOUT_TEXT")
      (footprint "eagle-import:1X01_WITHOUT_TEXT")
      (libsource (lib "eagle-import") (part "M01PTH_WITHOUT_TEXT"))
    )
    (comp (ref "CLEAN160")
      (value "M01PTH_WITHOUT_TEXT")
      (footprint "eagle-import:1X01_WITHOUT_TEXT")
      (libsource (lib "eagle-import") (part "M01PTH_WITHOUT_TEXT"))
    )
    (comp (ref "CLEAN161")
      (value "M01PTH_WITHOUT_TEXT")
      (footprint "eagle-import:1X01_WITHOUT_TEXT")
      (libsource (lib "eagle-import") (part "M01PTH_WITHOUT_TEXT"))
    )
    (comp (ref "CLEAN162")
      (value "M01PTH_WITHOUT_TEXT")
      (footprint "eagle-import:1X01_WITHOUT_TEXT")
      (libsource (lib "eagle-import") (part "M01PTH_WITHOUT_TEXT"))
    )
    (comp (ref "CLEAN163")
      (value "M01PTH_WITHOUT_TEXT")
      (footprint "eagle-import:1X01_WITHOUT_TEXT")
      (libsource (lib "eagle-import") (part "M01PTH_WITHOUT_TEXT"))
    )
    (comp (ref "CLEAN164")
      (value "M01PTH_WITHOUT_TEXT")
      (footprint "eagle-import:1X01_WITHOUT_TEXT")
      (libsource (lib "eagle-import") (part "M01PTH_WITHOUT_TEXT"))
    )
    (comp (ref "CLEAN165")
      (value "M01PTH_WITHOUT_TEXT")
      (footprint "eagle-import:1X01_WITHOUT_TEXT")
      (libsource (lib "eagle-import") (part "M01PTH_WITHOUT_TEXT"))
    )
    (comp (ref "CLEAN166")
      (value "M01PTH_WITHOUT_TEXT")
      (footprint "eagle-import:1X01_WITHOUT_TEXT")
      (libsource (lib "eagle-import") (part "M01PTH_WITHOUT_TEXT"))
    )
    (comp (ref "CLEAN167")
      (value "M01PTH_WITHOUT_TEXT")
      (footprint "eagle-import:1X01_WITHOUT_TEXT")
      (libsource (lib "eagle-import") (part "M01PTH_WITHOUT_TEXT"))
    )
    (comp (ref "CLEAN168")
      (value "M01PTH_WITHOUT_TEXT")
      (footprint "eagle-import:1X01_WITHOUT_TEXT")
      (libsource (lib "eagle-import") (part "M01PTH_WITHOUT_TEXT"))
    )
    (comp (ref "CLEAN169")
      (value "M01PTH_WITHOUT_TEXT")
      (footprint "eagle-import:1X01_WITHOUT_TEXT")
      (libsource (lib "eagle-import") (part "M01PTH_WITHOUT_TEXT"))
    )
    (comp (ref "CLEAN170")
      (value "M01PTH_WITHOUT_TEXT")
      (footprint "eagle-import:1X01_WITHOUT_TEXT")
      (libsource (lib "eagle-import") (part "M01PTH_WITHOUT_TEXT"))
    )
    (comp (ref "CLEAN171")
      (value "M01PTH_WITHOUT_TEXT")
      (footprint "eagle-import:1X01_WITHOUT_TEXT")
      (libsource (lib "eagle-import") (part "M01PTH_WITHOUT_TEXT"))
    )
    (comp (ref "CLEAN172")
      (value "M01PTH_WITHOUT_TEXT")
      (footprint "eagle-import:1X01_WITHOUT_TEXT")
      (libsource (lib "eagle-import") (part "M01PTH_WITHOUT_TEXT"))
    )
    (comp (ref "CLEAN173")
      (value "M01PTH_WITHOUT_TEXT")
      (footprint "eagle-import:1X01_WITHOUT_TEXT")
      (libsource (lib "eagle-import") (part "M01PTH_WITHOUT_TEXT"))
    )
    (comp (ref "CLEAN174")
      (value "M01PTH_WITHOUT_TEXT")
      (footprint "eagle-import:1X01_WITHOUT_TEXT")
      (libsource (lib "eagle-import") (part "M01PTH_WITHOUT_TEXT"))
    )
    (comp (ref "CLEAN175")
      (value "M01PTH_WITHOUT_TEXT")
      (footprint "eagle-import:1X01_WITHOUT_TEXT")
      (libsource (lib "eagle-import") (part "M01PTH_WITHOUT_TEXT"))
    )
    (comp (ref "CLEAN176")
      (value "M01PTH_WITHOUT_TEXT")
      (footprint "eagle-import:1X01_WITHOUT_TEXT")
      (libsource (lib "eagle-import") (part "M01PTH_WITHOUT_TEXT"))
    )
    (comp (ref "CLEAN177")
      (value "M01PTH_WITHOUT_TEXT")
      (footprint "eagle-import:1X01_WITHOUT_TEXT")
      (libsource (lib "eagle-import") (part "M01PTH_WITHOUT_TEXT"))
    )
    (comp (ref "CLEAN178")
      (value "M01PTH_WITHOUT_TEXT")
      (footprint "eagle-import:1X01_WITHOUT_TEXT")
      (libsource (lib "eagle-import") (part "M01PTH_WITHOUT_TEXT"))
    )
    (comp (ref "CLEAN179")
      (value "M01PTH_WITHOUT_TEXT")
      (footprint "eagle-import:1X01_WITHOUT_TEXT")
      (libsource (lib "eagle-import") (part "M01PTH_WITHOUT_TEXT"))
    )
    (comp (ref "CLEAN180")
      (value "M01PTH_WITHOUT_TEXT")
      (footprint "eagle-import:1X01_WITHOUT_TEXT")
      (libsource (lib "eagle-import") (part "M01PTH_WITHOUT_TEXT"))
    )
    (comp (ref "CLEAN181")
      (value "M01PTH_WITHOUT_TEXT")
      (footprint "eagle-import:1X01_WITHOUT_TEXT")
      (libsource (lib "eagle-import") (part "M01PTH_WITHOUT_TEXT"))
    )
    (comp (ref "CLEAN182")
      (value "M01PTH_WITHOUT_TEXT")
      (footprint "eagle-import:1X01_WITHOUT_TEXT")
      (libsource (lib "eagle-import") (part "M01PTH_WITHOUT_TEXT"))
    )
    (comp (ref "CLEAN183")
      (value "M01PTH_WITHOUT_TEXT")
      (footprint "eagle-import:1X01_WITHOUT_TEXT")
      (libsource (lib "eagle-import") (part "M01PTH_WITHOUT_TEXT"))
    )
    (comp (ref "CLEAN184")
      (value "M01PTH_WITHOUT_TEXT")
      (footprint "eagle-import:1X01_WITHOUT_TEXT")
      (libsource (lib "eagle-import") (part "M01PTH_WITHOUT_TEXT"))
    )
    (comp (ref "CLEAN185")
      (value "M01PTH_WITHOUT_TEXT")
      (footprint "eagle-import:1X01_WITHOUT_TEXT")
      (libsource (lib "eagle-import") (part "M01PTH_WITHOUT_TEXT"))
    )
    (comp (ref "CLEAN186")
      (value "M01PTH_WITHOUT_TEXT")
      (footprint "eagle-import:1X01_WITHOUT_TEXT")
      (libsource (lib "eagle-import") (part "M01PTH_WITHOUT_TEXT"))
    )
    (comp (ref "CLEAN187")
      (value "M01PTH_WITHOUT_TEXT")
      (footprint "eagle-import:1X01_WITHOUT_TEXT")
      (libsource (lib "eagle-import") (part "M01PTH_WITHOUT_TEXT"))
    )
    (comp (ref "CLEAN188")
      (value "M01PTH_WITHOUT_TEXT")
      (footprint "eagle-import:1X01_WITHOUT_TEXT")
      (libsource (lib "eagle-import") (part "M01PTH_WITHOUT_TEXT"))
    )
    (comp (ref "CLEAN189")
      (value "M01PTH_WITHOUT_TEXT")
      (footprint "eagle-import:1X01_WITHOUT_TEXT")
      (libsource (lib "eagle-import") (part "M01PTH_WITHOUT_TEXT"))
    )
    (comp (ref "CLEAN190")
      (value "M01PTH_WITHOUT_TEXT")
      (footprint "eagle-import:1X01_WITHOUT_TEXT")
      (libsource (lib "eagle-import") (part "M01PTH_WITHOUT_TEXT"))
    )
    (comp (ref "CLEAN191")
      (value "M01PTH_WITHOUT_TEXT")
      (footprint "eagle-import:1X01_WITHOUT_TEXT")
      (libsource (lib "eagle-import") (part "M01PTH_WITHOUT_TEXT"))
    )
    (comp (ref "CLEAN192")
      (value "M01PTH_WITHOUT_TEXT")
      (footprint "eagle-import:1X01_WITHOUT_TEXT")
      (libsource (lib "eagle-import") (part "M01PTH_WITHOUT_TEXT"))
    )
    (comp (ref "CLEAN193")
      (value "M01PTH_WITHOUT_TEXT")
      (footprint "eagle-import:1X01_WITHOUT_TEXT")
      (libsource (lib "eagle-import") (part "M01PTH_WITHOUT_TEXT"))
    )
    (comp (ref "CLEAN194")
      (value "M01PTH_WITHOUT_TEXT")
      (footprint "eagle-import:1X01_WITHOUT_TEXT")
      (libsource (lib "eagle-import") (part "M01PTH_WITHOUT_TEXT"))
    )
    (comp (ref "CLEAN195")
      (value "M01PTH_WITHOUT_TEXT")
      (footprint "eagle-import:1X01_WITHOUT_TEXT")
      (libsource (lib "eagle-import") (part "M01PTH_WITHOUT_TEXT"))
    )
    (comp (ref "CLEAN196")
      (value "M01PTH_WITHOUT_TEXT")
      (footprint "eagle-import:1X01_WITHOUT_TEXT")
      (libsource (lib "eagle-import") (part "M01PTH_WITHOUT_TEXT"))
    )
    (comp (ref "CLEAN197")
      (value "M01PTH_WITHOUT_TEXT")
      (footprint "eagle-import:1X01_WITHOUT_TEXT")
      (libsource (lib "eagle-import") (part "M01PTH_WITHOUT_TEXT"))
    )
    (comp (ref "CLEAN198")
      (value "M01PTH_WITHOUT_TEXT")
      (footprint "eagle-import:1X01_WITHOUT_TEXT")
      (libsource (lib "eagle-import") (part "M01PTH_WITHOUT_TEXT"))
    )
    (comp (ref "CLEAN199")
      (value "M01PTH_WITHOUT_TEXT")
      (footprint "eagle-import:1X01_WITHOUT_TEXT")
      (libsource (lib "eagle-import") (part "M01PTH_WITHOUT_TEXT"))
    )
    (comp (ref "CLEAN200")
      (value "M01PTH_WITHOUT_TEXT")
      (footprint "eagle-import:1X01_WITHOUT_TEXT")
      (libsource (lib "eagle-import") (part "M01PTH_WITHOUT_TEXT"))
    )
    (comp (ref "CLEAN201")
      (value "M01PTH_WITHOUT_TEXT")
      (footprint "eagle-import:1X01_WITHOUT_TEXT")
      (libsource (lib "eagle-import") (part "M01PTH_WITHOUT_TEXT"))
    )
    (comp (ref "CLEAN202")
      (value "M01PTH_WITHOUT_TEXT")
      (footprint "eagle-import:1X01_WITHOUT_TEXT")
      (libsource (lib "eagle-import") (part "M01PTH_WITHOUT_TEXT"))
    )
    (comp (ref "CLEAN203")
      (value "M01PTH_WITHOUT_TEXT")
      (footprint "eagle-import:1X01_WITHOUT_TEXT")
      (libsource (lib "eagle-import") (part "M01PTH_WITHOUT_TEXT"))
    )
    (comp (ref "CLEAN204")
      (value "M01PTH_WITHOUT_TEXT")
      (footprint "eagle-import:1X01_WITHOUT_TEXT")
      (libsource (lib "eagle-import") (part "M01PTH_WITHOUT_TEXT"))
    )
    (comp (ref "CLEAN205")
      (value "M01PTH_WITHOUT_TEXT")
      (footprint "eagle-import:1X01_WITHOUT_TEXT")
      (libsource (lib "eagle-import") (part "M01PTH_WITHOUT_TEXT"))
    )
    (comp (ref "CLEAN206")
      (value "M01PTH_WITHOUT_TEXT")
      (footprint "eagle-import:1X01_WITHOUT_TEXT")
      (libsource (lib "eagle-import") (part "M01PTH_WITHOUT_TEXT"))
    )
    (comp (ref "CLEAN207")
      (value "M01PTH_WITHOUT_TEXT")
      (footprint "eagle-import:1X01_WITHOUT_TEXT")
      (libsource (lib "eagle-import") (part "M01PTH_WITHOUT_TEXT"))
    )
    (comp (ref "CLEAN208")
      (value "M01PTH_WITHOUT_TEXT")
      (footprint "eagle-import:1X01_WITHOUT_TEXT")
      (libsource (lib "eagle-import") (part "M01PTH_WITHOUT_TEXT"))
    )
    (comp (ref "CLEAN209")
      (value "M01PTH_WITHOUT_TEXT")
      (footprint "eagle-import:1X01_WITHOUT_TEXT")
      (libsource (lib "eagle-import") (part "M01PTH_WITHOUT_TEXT"))
    )
    (comp (ref "CLEAN210")
      (value "M01PTH_WITHOUT_TEXT")
      (footprint "eagle-import:1X01_WITHOUT_TEXT")
      (libsource (lib "eagle-import") (part "M01PTH_WITHOUT_TEXT"))
    )
    (comp (ref "CLEAN211")
      (value "M01PTH_WITHOUT_TEXT")
      (footprint "eagle-import:1X01_WITHOUT_TEXT")
      (libsource (lib "eagle-import") (part "M01PTH_WITHOUT_TEXT"))
    )
    (comp (ref "CLEAN212")
      (value "M01PTH_WITHOUT_TEXT")
      (footprint "eagle-import:1X01_WITHOUT_TEXT")
      (libsource (lib "eagle-import") (part "M01PTH_WITHOUT_TEXT"))
    )
    (comp (ref "CLEAN213")
      (value "M01PTH_WITHOUT_TEXT")
      (footprint "eagle-import:1X01_WITHOUT_TEXT")
      (libsource (lib "eagle-import") (part "M01PTH_WITHOUT_TEXT"))
    )
    (comp (ref "CLEAN214")
      (value "M01PTH_WITHOUT_TEXT")
      (footprint "eagle-import:1X01_WITHOUT_TEXT")
      (libsource (lib "eagle-import") (part "M01PTH_WITHOUT_TEXT"))
    )
    (comp (ref "CLEAN215")
      (value "M01PTH_WITHOUT_TEXT")
      (footprint "eagle-import:1X01_WITHOUT_TEXT")
      (libsource (lib "eagle-import") (part "M01PTH_WITHOUT_TEXT"))
    )
    (comp (ref "CLEAN216")
      (value "M01PTH_WITHOUT_TEXT")
      (footprint "eagle-import:1X01_WITHOUT_TEXT")
      (libsource (lib "eagle-import") (part "M01PTH_WITHOUT_TEXT"))
    )
    (comp (ref "CLEAN217")
      (value "M01PTH_WITHOUT_TEXT")
      (footprint "eagle-import:1X01_WITHOUT_TEXT")
      (libsource (lib "eagle-import") (part "M01PTH_WITHOUT_TEXT"))
    )
    (comp (ref "CLEAN218")
      (value "M01PTH_WITHOUT_TEXT")
      (footprint "eagle-import:1X01_WITHOUT_TEXT")
      (libsource (lib "eagle-import") (part "M01PTH_WITHOUT_TEXT"))
    )
    (comp (ref "CLEAN219")
      (value "M01PTH_WITHOUT_TEXT")
      (footprint "eagle-import:1X01_WITHOUT_TEXT")
      (libsource (lib "eagle-import") (part "M01PTH_WITHOUT_TEXT"))
    )
    (comp (ref "CLEAN220")
      (value "M01PTH_WITHOUT_TEXT")
      (footprint "eagle-import:1X01_WITHOUT_TEXT")
      (libsource (lib "eagle-import") (part "M01PTH_WITHOUT_TEXT"))
    )
    (comp (ref "CLEAN221")
      (value "M01PTH_WITHOUT_TEXT")
      (footprint "eagle-import:1X01_WITHOUT_TEXT")
      (libsource (lib "eagle-import") (part "M01PTH_WITHOUT_TEXT"))
    )
    (comp (ref "CLEAN222")
      (value "M01PTH_WITHOUT_TEXT")
      (footprint "eagle-import:1X01_WITHOUT_TEXT")
      (libsource (lib "eagle-import") (part "M01PTH_WITHOUT_TEXT"))
    )
    (comp (ref "CLEAN223")
      (value "M01PTH_WITHOUT_TEXT")
      (footprint "eagle-import:1X01_WITHOUT_TEXT")
      (libsource (lib "eagle-import") (part "M01PTH_WITHOUT_TEXT"))
    )
    (comp (ref "CLEAN224")
      (value "M01PTH_WITHOUT_TEXT")
      (footprint "eagle-import:1X01_WITHOUT_TEXT")
      (libsource (lib "eagle-import") (part "M01PTH_WITHOUT_TEXT"))
    )
    (comp (ref "CLEAN225")
      (value "M01PTH_WITHOUT_TEXT")
      (footprint "eagle-import:1X01_WITHOUT_TEXT")
      (libsource (lib "eagle-import") (part "M01PTH_WITHOUT_TEXT"))
    )
    (comp (ref "CLEAN226")
      (value "M01PTH_WITHOUT_TEXT")
      (footprint "eagle-import:1X01_WITHOUT_TEXT")
      (libsource (lib "eagle-import") (part "M01PTH_WITHOUT_TEXT"))
    )
    (comp (ref "CLEAN227")
      (value "M01PTH_WITHOUT_TEXT")
      (footprint "eagle-import:1X01_WITHOUT_TEXT")
      (libsource (lib "eagle-import") (part "M01PTH_WITHOUT_TEXT"))
    )
    (comp (ref "CLEAN228")
      (value "M01PTH_WITHOUT_TEXT")
      (footprint "eagle-import:1X01_WITHOUT_TEXT")
      (libsource (lib "eagle-import") (part "M01PTH_WITHOUT_TEXT"))
    )
    (comp (ref "CLEAN229")
      (value "M01PTH_WITHOUT_TEXT")
      (footprint "eagle-import:1X01_WITHOUT_TEXT")
      (libsource (lib "eagle-import") (part "M01PTH_WITHOUT_TEXT"))
    )
    (comp (ref "CLEAN230")
      (value "M01PTH_WITHOUT_TEXT")
      (footprint "eagle-import:1X01_WITHOUT_TEXT")
      (libsource (lib "eagle-import") (part "M01PTH_WITHOUT_TEXT"))
    )
    (comp (ref "CLEAN231")
      (value "M01PTH_WITHOUT_TEXT")
      (footprint "eagle-import:1X01_WITHOUT_TEXT")
      (libsource (lib "eagle-import") (part "M01PTH_WITHOUT_TEXT"))
    )
    (comp (ref "CLEAN232")
      (value "M01PTH_WITHOUT_TEXT")
      (footprint "eagle-import:1X01_WITHOUT_TEXT")
      (libsource (lib "eagle-import") (part "M01PTH_WITHOUT_TEXT"))
    )
    (comp (ref "CLEAN233")
      (value "M01PTH_WITHOUT_TEXT")
      (footprint "eagle-import:1X01_WITHOUT_TEXT")
      (libsource (lib "eagle-import") (part "M01PTH_WITHOUT_TEXT"))
    )
    (comp (ref "CLEAN234")
      (value "M01PTH_WITHOUT_TEXT")
      (footprint "eagle-import:1X01_WITHOUT_TEXT")
      (libsource (lib "eagle-import") (part "M01PTH_WITHOUT_TEXT"))
    )
    (comp (ref "CLEAN235")
      (value "M01PTH_WITHOUT_TEXT")
      (footprint "eagle-import:1X01_WITHOUT_TEXT")
      (libsource (lib "eagle-import") (part "M01PTH_WITHOUT_TEXT"))
    )
    (comp (ref "CLEAN236")
      (value "M01PTH_WITHOUT_TEXT")
      (footprint "eagle-import:1X01_WITHOUT_TEXT")
      (libsource (lib "eagle-import") (part "M01PTH_WITHOUT_TEXT"))
    )
    (comp (ref "CLEAN237")
      (value "M01PTH_WITHOUT_TEXT")
      (footprint "eagle-import:1X01_WITHOUT_TEXT")
      (libsource (lib "eagle-import") (part "M01PTH_WITHOUT_TEXT"))
    )
    (comp (ref "CLEAN238")
      (value "M01PTH_WITHOUT_TEXT")
      (footprint "eagle-import:1X01_WITHOUT_TEXT")
      (libsource (lib "eagle-import") (part "M01PTH_WITHOUT_TEXT"))
    )
    (comp (ref "CLEAN239")
      (value "M01PTH_WITHOUT_TEXT")
      (footprint "eagle-import:1X01_WITHOUT_TEXT")
      (libsource (lib "eagle-import") (part "M01PTH_WITHOUT_TEXT"))
    )
    (comp (ref "CLEAN240")
      (value "M01PTH_WITHOUT_TEXT")
      (footprint "eagle-import:1X01_WITHOUT_TEXT")
      (libsource (lib "eagle-import") (part "M01PTH_WITHOUT_TEXT"))
    )
    (comp (ref "CLEAN241")
      (value "M01PTH_WITHOUT_TEXT")
      (footprint "eagle-import:1X01_WITHOUT_TEXT")
      (libsource (lib "eagle-import") (part "M01PTH_WITHOUT_TEXT"))
    )
    (comp (ref "CLEAN242")
      (value "M01PTH_WITHOUT_TEXT")
      (footprint "eagle-import:1X01_WITHOUT_TEXT")
      (libsource (lib "eagle-import") (part "M01PTH_WITHOUT_TEXT"))
    )
    (comp (ref "CLEAN243")
      (value "M01PTH_WITHOUT_TEXT")
      (footprint "eagle-import:1X01_WITHOUT_TEXT")
      (libsource (lib "eagle-import") (part "M01PTH_WITHOUT_TEXT"))
    )
    (comp (ref "CLEAN244")
      (value "M01PTH_WITHOUT_TEXT")
      (footprint "eagle-import:1X01_WITHOUT_TEXT")
      (libsource (lib "eagle-import") (part "M01PTH_WITHOUT_TEXT"))
    )
    (comp (ref "CLEAN245")
      (value "M01PTH_WITHOUT_TEXT")
      (footprint "eagle-import:1X01_WITHOUT_TEXT")
      (libsource (lib "eagle-import") (part "M01PTH_WITHOUT_TEXT"))
    )
    (comp (ref "CLEAN246")
      (value "M01PTH_WITHOUT_TEXT")
      (footprint "eagle-import:1X01_WITHOUT_TEXT")
      (libsource (lib "eagle-import") (part "M01PTH_WITHOUT_TEXT"))
    )
    (comp (ref "CLEAN247")
      (value "M01PTH_WITHOUT_TEXT")
      (footprint "eagle-import:1X01_WITHOUT_TEXT")
      (libsource (lib "eagle-import") (part "M01PTH_WITHOUT_TEXT"))
    )
    (comp (ref "CLEAN248")
      (value "M01PTH_WITHOUT_TEXT")
      (footprint "eagle-import:1X01_WITHOUT_TEXT")
      (libsource (lib "eagle-import") (part "M01PTH_WITHOUT_TEXT"))
    )
    (comp (ref "CLEAN249")
      (value "M01PTH_WITHOUT_TEXT")
      (footprint "eagle-import:1X01_WITHOUT_TEXT")
      (libsource (lib "eagle-import") (part "M01PTH_WITHOUT_TEXT"))
    )
    (comp (ref "CLEAN250")
      (value "M01PTH_WITHOUT_TEXT")
      (footprint "eagle-import:1X01_WITHOUT_TEXT")
      (libsource (lib "eagle-import") (part "M01PTH_WITHOUT_TEXT"))
    )
    (comp (ref "CLEAN251")
      (value "M01PTH_WITHOUT_TEXT")
      (footprint "eagle-import:1X01_WITHOUT_TEXT")
      (libsource (lib "eagle-import") (part "M01PTH_WITHOUT_TEXT"))
    )
    (comp (ref "CLEAN252")
      (value "M01PTH_WITHOUT_TEXT")
      (footprint "eagle-import:1X01_WITHOUT_TEXT")
      (libsource (lib "eagle-import") (part "M01PTH_WITHOUT_TEXT"))
    )
    (comp (ref "CLEAN253")
      (value "M01PTH_WITHOUT_TEXT")
      (footprint "eagle-import:1X01_WITHOUT_TEXT")
      (libsource (lib "eagle-import") (part "M01PTH_WITHOUT_TEXT"))
    )
    (comp (ref "CLEAN254")
      (value "M01PTH_WITHOUT_TEXT")
      (footprint "eagle-import:1X01_WITHOUT_TEXT")
      (libsource (lib "eagle-import") (part "M01PTH_WITHOUT_TEXT"))
    )
    (comp (ref "CLEAN255")
      (value "M01PTH_WITHOUT_TEXT")
      (footprint "eagle-import:1X01_WITHOUT_TEXT")
      (libsource (lib "eagle-import") (part "M01PTH_WITHOUT_TEXT"))
    )
    (comp (ref "CLEAN256")
      (value "M01PTH_WITHOUT_TEXT")
      (footprint "eagle-import:1X01_WITHOUT_TEXT")
      (libsource (lib "eagle-import") (part "M01PTH_WITHOUT_TEXT"))
    )
    (comp (ref "CLEAN257")
      (value "M01PTH_WITHOUT_TEXT")
      (footprint "eagle-import:1X01_WITHOUT_TEXT")
      (libsource (lib "eagle-import") (part "M01PTH_WITHOUT_TEXT"))
    )
    (comp (ref "CLEAN258")
      (value "M01PTH_WITHOUT_TEXT")
      (footprint "eagle-import:1X01_WITHOUT_TEXT")
      (libsource (lib "eagle-import") (part "M01PTH_WITHOUT_TEXT"))
    )
    (comp (ref "CLEAN259")
      (value "M01PTH_WITHOUT_TEXT")
      (footprint "eagle-import:1X01_WITHOUT_TEXT")
      (libsource (lib "eagle-import") (part "M01PTH_WITHOUT_TEXT"))
    )
    (comp (ref "CLEAN260")
      (value "M01PTH_WITHOUT_TEXT")
      (footprint "eagle-import:1X01_WITHOUT_TEXT")
      (libsource (lib "eagle-import") (part "M01PTH_WITHOUT_TEXT"))
    )
    (comp (ref "CLEAN261")
      (value "M01PTH_WITHOUT_TEXT")
      (footprint "eagle-import:1X01_WITHOUT_TEXT")
      (libsource (lib "eagle-import") (part "M01PTH_WITHOUT_TEXT"))
    )
    (comp (ref "CLEAN262")
      (value "M01PTH_WITHOUT_TEXT")
      (footprint "eagle-import:1X01_WITHOUT_TEXT")
      (libsource (lib "eagle-import") (part "M01PTH_WITHOUT_TEXT"))
    )
    (comp (ref "CLEAN263")
      (value "M01PTH_WITHOUT_TEXT")
      (footprint "eagle-import:1X01_WITHOUT_TEXT")
      (libsource (lib "eagle-import") (part "M01PTH_WITHOUT_TEXT"))
    )
    (comp (ref "CLEAN264")
      (value "M01PTH_WITHOUT_TEXT")
      (footprint "eagle-import:1X01_WITHOUT_TEXT")
      (libsource (lib "eagle-import") (part "M01PTH_WITHOUT_TEXT"))
    )
    (comp (ref "CLEAN265")
      (value "M01PTH_WITHOUT_TEXT")
      (footprint "eagle-import:1X01_WITHOUT_TEXT")
      (libsource (lib "eagle-import") (part "M01PTH_WITHOUT_TEXT"))
    )
    (comp (ref "CLEAN266")
      (value "M01PTH_WITHOUT_TEXT")
      (footprint "eagle-import:1X01_WITHOUT_TEXT")
      (libsource (lib "eagle-import") (part "M01PTH_WITHOUT_TEXT"))
    )
    (comp (ref "CLEAN267")
      (value "M01PTH_WITHOUT_TEXT")
      (footprint "eagle-import:1X01_WITHOUT_TEXT")
      (libsource (lib "eagle-import") (part "M01PTH_WITHOUT_TEXT"))
    )
    (comp (ref "CLEAN268")
      (value "M01PTH_WITHOUT_TEXT")
      (footprint "eagle-import:1X01_WITHOUT_TEXT")
      (libsource (lib "eagle-import") (part "M01PTH_WITHOUT_TEXT"))
    )
    (comp (ref "CLEAN269")
      (value "M01PTH_WITHOUT_TEXT")
      (footprint "eagle-import:1X01_WITHOUT_TEXT")
      (libsource (lib "eagle-import") (part "M01PTH_WITHOUT_TEXT"))
    )
    (comp (ref "CLEAN270")
      (value "M01PTH_WITHOUT_TEXT")
      (footprint "eagle-import:1X01_WITHOUT_TEXT")
      (libsource (lib "eagle-import") (part "M01PTH_WITHOUT_TEXT"))
    )
    (comp (ref "CLEAN271")
      (value "M01PTH_WITHOUT_TEXT")
      (footprint "eagle-import:1X01_WITHOUT_TEXT")
      (libsource (lib "eagle-import") (part "M01PTH_WITHOUT_TEXT"))
    )
    (comp (ref "CLEAN272")
      (value "M01PTH_WITHOUT_TEXT")
      (footprint "eagle-import:1X01_WITHOUT_TEXT")
      (libsource (lib "eagle-import") (part "M01PTH_WITHOUT_TEXT"))
    )
    (comp (ref "CLEAN273")
      (value "M01PTH_WITHOUT_TEXT")
      (footprint "eagle-import:1X01_WITHOUT_TEXT")
      (libsource (lib "eagle-import") (part "M01PTH_WITHOUT_TEXT"))
    )
    (comp (ref "CLEAN274")
      (value "M01PTH_WITHOUT_TEXT")
      (footprint "eagle-import:1X01_WITHOUT_TEXT")
      (libsource (lib "eagle-import") (part "M01PTH_WITHOUT_TEXT"))
    )
    (comp (ref "CLEAN275")
      (value "M01PTH_WITHOUT_TEXT")
      (footprint "eagle-import:1X01_WITHOUT_TEXT")
      (libsource (lib "eagle-import") (part "M01PTH_WITHOUT_TEXT"))
    )
    (comp (ref "CLEAN276")
      (value "M01PTH_WITHOUT_TEXT")
      (footprint "eagle-import:1X01_WITHOUT_TEXT")
      (libsource (lib "eagle-import") (part "M01PTH_WITHOUT_TEXT"))
    )
    (comp (ref "CLEAN277")
      (value "M01PTH_WITHOUT_TEXT")
      (footprint "eagle-import:1X01_WITHOUT_TEXT")
      (libsource (lib "eagle-import") (part "M01PTH_WITHOUT_TEXT"))
    )
    (comp (ref "CLEAN278")
      (value "M01PTH_WITHOUT_TEXT")
      (footprint "eagle-import:1X01_WITHOUT_TEXT")
      (libsource (lib "eagle-import") (part "M01PTH_WITHOUT_TEXT"))
    )
    (comp (ref "CLEAN279")
      (value "M01PTH_WITHOUT_TEXT")
      (footprint "eagle-import:1X01_WITHOUT_TEXT")
      (libsource (lib "eagle-import") (part "M01PTH_WITHOUT_TEXT"))
    )
    (comp (ref "CLEAN280")
      (value "M01PTH_WITHOUT_TEXT")
      (footprint "eagle-import:1X01_WITHOUT_TEXT")
      (libsource (lib "eagle-import") (part "M01PTH_WITHOUT_TEXT"))
    )
    (comp (ref "CLEAN281")
      (value "M01PTH_WITHOUT_TEXT")
      (footprint "eagle-import:1X01_WITHOUT_TEXT")
      (libsource (lib "eagle-import") (part "M01PTH_WITHOUT_TEXT"))
    )
    (comp (ref "CLEAN282")
      (value "M01PTH_WITHOUT_TEXT")
      (footprint "eagle-import:1X01_WITHOUT_TEXT")
      (libsource (lib "eagle-import") (part "M01PTH_WITHOUT_TEXT"))
    )
    (comp (ref "CLEAN283")
      (value "M01PTH_WITHOUT_TEXT")
      (footprint "eagle-import:1X01_WITHOUT_TEXT")
      (libsource (lib "eagle-import") (part "M01PTH_WITHOUT_TEXT"))
    )
    (comp (ref "CLEAN284")
      (value "M01PTH_WITHOUT_TEXT")
      (footprint "eagle-import:1X01_WITHOUT_TEXT")
      (libsource (lib "eagle-import") (part "M01PTH_WITHOUT_TEXT"))
    )
    (comp (ref "CLEAN285")
      (value "M01PTH_WITHOUT_TEXT")
      (footprint "eagle-import:1X01_WITHOUT_TEXT")
      (libsource (lib "eagle-import") (part "M01PTH_WITHOUT_TEXT"))
    )
    (comp (ref "CLEAN286")
      (value "M01PTH_WITHOUT_TEXT")
      (footprint "eagle-import:1X01_WITHOUT_TEXT")
      (libsource (lib "eagle-import") (part "M01PTH_WITHOUT_TEXT"))
    )
    (comp (ref "CLEAN287")
      (value "M01PTH_WITHOUT_TEXT")
      (footprint "eagle-import:1X01_WITHOUT_TEXT")
      (libsource (lib "eagle-import") (part "M01PTH_WITHOUT_TEXT"))
    )
    (comp (ref "CLEAN288")
      (value "M01PTH_WITHOUT_TEXT")
      (footprint "eagle-import:1X01_WITHOUT_TEXT")
      (libsource (lib "eagle-import") (part "M01PTH_WITHOUT_TEXT"))
    )
    (comp (ref "CLEAN289")
      (value "M01PTH_WITHOUT_TEXT")
      (footprint "eagle-import:1X01_WITHOUT_TEXT")
      (libsource (lib "eagle-import") (part "M01PTH_WITHOUT_TEXT"))
    )
    (comp (ref "CLEAN290")
      (value "M01PTH_WITHOUT_TEXT")
      (footprint "eagle-import:1X01_WITHOUT_TEXT")
      (libsource (lib "eagle-import") (part "M01PTH_WITHOUT_TEXT"))
    )
    (comp (ref "CLEAN291")
      (value "M01PTH_WITHOUT_TEXT")
      (footprint "eagle-import:1X01_WITHOUT_TEXT")
      (libsource (lib "eagle-import") (part "M01PTH_WITHOUT_TEXT"))
    )
    (comp (ref "CLEAN292")
      (value "M01PTH_WITHOUT_TEXT")
      (footprint "eagle-import:1X01_WITHOUT_TEXT")
      (libsource (lib "eagle-import") (part "M01PTH_WITHOUT_TEXT"))
    )
    (comp (ref "CLEAN293")
      (value "M01PTH_WITHOUT_TEXT")
      (footprint "eagle-import:1X01_WITHOUT_TEXT")
      (libsource (lib "eagle-import") (part "M01PTH_WITHOUT_TEXT"))
    )
    (comp (ref "CLEAN294")
      (value "M01PTH_WITHOUT_TEXT")
      (footprint "eagle-import:1X01_WITHOUT_TEXT")
      (libsource (lib "eagle-import") (part "M01PTH_WITHOUT_TEXT"))
    )
    (comp (ref "CLEAN295")
      (value "M01PTH_WITHOUT_TEXT")
      (footprint "eagle-import:1X01_WITHOUT_TEXT")
      (libsource (lib "eagle-import") (part "M01PTH_WITHOUT_TEXT"))
    )
    (comp (ref "CLEAN296")
      (value "M01PTH_WITHOUT_TEXT")
      (footprint "eagle-import:1X01_WITHOUT_TEXT")
      (libsource (lib "eagle-import") (part "M01PTH_WITHOUT_TEXT"))
    )
    (comp (ref "CLEAN297")
      (value "M01PTH_WITHOUT_TEXT")
      (footprint "eagle-import:1X01_WITHOUT_TEXT")
      (libsource (lib "eagle-import") (part "M01PTH_WITHOUT_TEXT"))
    )
    (comp (ref "CLEAN298")
      (value "M01PTH_WITHOUT_TEXT")
      (footprint "eagle-import:1X01_WITHOUT_TEXT")
      (libsource (lib "eagle-import") (part "M01PTH_WITHOUT_TEXT"))
    )
    (comp (ref "CLEAN299")
      (value "M01PTH_WITHOUT_TEXT")
      (footprint "eagle-import:1X01_WITHOUT_TEXT")
      (libsource (lib "eagle-import") (part "M01PTH_WITHOUT_TEXT"))
    )
    (comp (ref "CLEAN300")
      (value "M01PTH_SMD_3.25X0.85MM_NO_SILK")
      (footprint "eagle-import:1X01_SMD_3.25X0.85MM_NO_SILK")
      (libsource (lib "eagle-import") (part "M01PTH_SMD_3.25X0.85MM_NO_SILK"))
    )
    (comp (ref "CLEAN301")
      (value "M01PTH_SMD_3.25X0.85MM_NO_SILK")
      (footprint "eagle-import:1X01_SMD_3.25X0.85MM_NO_SILK")
      (libsource (lib "eagle-import") (part "M01PTH_SMD_3.25X0.85MM_NO_SILK"))
    )
    (comp (ref "CLEAN302")
      (value "M01PTH_SMD_3.25X0.85MM_NO_SILK")
      (footprint "eagle-import:1X01_SMD_3.25X0.85MM_NO_SILK")
      (libsource (lib "eagle-import") (part "M01PTH_SMD_3.25X0.85MM_NO_SILK"))
    )
    (comp (ref "CLEAN303")
      (value "M01PTH_SMD_3.25X0.85MM_NO_SILK")
      (footprint "eagle-import:1X01_SMD_3.25X0.85MM_NO_SILK")
      (libsource (lib "eagle-import") (part "M01PTH_SMD_3.25X0.85MM_NO_SILK"))
    )
    (comp (ref "CLEAN304")
      (value "M01PTH_SMD_3.25X0.85MM_NO_SILK")
      (footprint "eagle-import:1X01_SMD_3.25X0.85MM_NO_SILK")
      (libsource (lib "eagle-import") (part "M01PTH_SMD_3.25X0.85MM_NO_SILK"))
    )
    (comp (ref "CLEAN305")
      (value "M01PTH_SMD_3.25X0.85MM_NO_SILK")
      (footprint "eagle-import:1X01_SMD_3.25X0.85MM_NO_SILK")
      (libsource (lib "eagle-import") (part "M01PTH_SMD_3.25X0.85MM_NO_SILK"))
    )
    (comp (ref "CLEAN306")
      (value "M01PTH_SMD_3.25X0.85MM_NO_SILK")
      (footprint "eagle-import:1X01_SMD_3.25X0.85MM_NO_SILK")
      (libsource (lib "eagle-import") (part "M01PTH_SMD_3.25X0.85MM_NO_SILK"))
    )
    (comp (ref "CLEAN307")
      (value "M01PTH_SMD_3.25X0.85MM_NO_SILK")
      (footprint "eagle-import:1X01_SMD_3.25X0.85MM_NO_SILK")
      (libsource (lib "eagle-import") (part "M01PTH_SMD_3.25X0.85MM_NO_SILK"))
    )
    (comp (ref "CLEAN308")
      (value "M01PTH_SMD_3.25X0.85MM_NO_SILK")
      (footprint "eagle-import:1X01_SMD_3.25X0.85MM_NO_SILK")
      (libsource (lib "eagle-import") (part "M01PTH_SMD_3.25X0.85MM_NO_SILK"))
    )
    (comp (ref "CLEAN309")
      (value "M01PTH_SMD_3.25X0.85MM_NO_SILK")
      (footprint "eagle-import:1X01_SMD_3.25X0.85MM_NO_SILK")
      (libsource (lib "eagle-import") (part "M01PTH_SMD_3.25X0.85MM_NO_SILK"))
    )
    (comp (ref "CLEAN310")
      (value "M01PTH_SMD_3.25X0.85MM_NO_SILK")
      (footprint "eagle-import:1X01_SMD_3.25X0.85MM_NO_SILK")
      (libsource (lib "eagle-import") (part "M01PTH_SMD_3.25X0.85MM_NO_SILK"))
    )
    (comp (ref "CLEAN311")
      (value "M01PTH_SMD_3.25X0.85MM_NO_SILK")
      (footprint "eagle-import:1X01_SMD_3.25X0.85MM_NO_SILK")
      (libsource (lib "eagle-import") (part "M01PTH_SMD_3.25X0.85MM_NO_SILK"))
    )
    (comp (ref "CLEAN312")
      (value "M01PTH_SMD_3.25X0.85MM_NO_SILK")
      (footprint "eagle-import:1X01_SMD_3.25X0.85MM_NO_SILK")
      (libsource (lib "eagle-import") (part "M01PTH_SMD_3.25X0.85MM_NO_SILK"))
    )
    (comp (ref "CLEAN313")
      (value "M01PTH_SMD_3.25X0.85MM_NO_SILK")
      (footprint "eagle-import:1X01_SMD_3.25X0.85MM_NO_SILK")
      (libsource (lib "eagle-import") (part "M01PTH_SMD_3.25X0.85MM_NO_SILK"))
    )
    (comp (ref "CLEAN314")
      (value "M01PTH_SMD_3.25X0.85MM_NO_SILK")
      (footprint "eagle-import:1X01_SMD_3.25X0.85MM_NO_SILK")
      (libsource (lib "eagle-import") (part "M01PTH_SMD_3.25X0.85MM_NO_SILK"))
    )
    (comp (ref "CLEAN315")
      (value "M01PTH_SMD_3.25X0.85MM_NO_SILK")
      (footprint "eagle-import:1X01_SMD_3.25X0.85MM_NO_SILK")
      (libsource (lib "eagle-import") (part "M01PTH_SMD_3.25X0.85MM_NO_SILK"))
    )
    (comp (ref "CLEAN316")
      (value "M01PTH_SMD_3.25X0.85MM_NO_SILK")
      (footprint "eagle-import:1X01_SMD_3.25X0.85MM_NO_SILK")
      (libsource (lib "eagle-import") (part "M01PTH_SMD_3.25X0.85MM_NO_SILK"))
    )
    (comp (ref "CLEAN317")
      (value "M01PTH_SMD_3.25X0.85MM_NO_SILK")
      (footprint "eagle-import:1X01_SMD_3.25X0.85MM_NO_SILK")
      (libsource (lib "eagle-import") (part "M01PTH_SMD_3.25X0.85MM_NO_SILK"))
    )
    (comp (ref "CLEAN318")
      (value "M01PTH_SMD_3.25X0.85MM_NO_SILK")
      (footprint "eagle-import:1X01_SMD_3.25X0.85MM_NO_SILK")
      (libsource (lib "eagle-import") (part "M01PTH_SMD_3.25X0.85MM_NO_SILK"))
    )
    (comp (ref "CLEAN319")
      (value "M01PTH_SMD_3.25X0.85MM_NO_SILK")
      (footprint "eagle-import:1X01_SMD_3.25X0.85MM_NO_SILK")
      (libsource (lib "eagle-import") (part "M01PTH_SMD_3.25X0.85MM_NO_SILK"))
    )
    (comp (ref "CLEAN320")
      (value "M01PTH_SMD_3.25X0.85MM_NO_SILK")
      (footprint "eagle-import:1X01_SMD_3.25X0.85MM_NO_SILK")
      (libsource (lib "eagle-import") (part "M01PTH_SMD_3.25X0.85MM_NO_SILK"))
    )
    (comp (ref "CLEAN321")
      (value "M01PTH_SMD_3.25X0.85MM_NO_SILK")
      (footprint "eagle-import:1X01_SMD_3.25X0.85MM_NO_SILK")
      (libsource (lib "eagle-import") (part "M01PTH_SMD_3.25X0.85MM_NO_SILK"))
    )
    (comp (ref "CLEAN322")
      (value "M01PTH_SMD_3.25X0.85MM_NO_SILK")
      (footprint "eagle-import:1X01_SMD_3.25X0.85MM_NO_SILK")
      (libsource (lib "eagle-import") (part "M01PTH_SMD_3.25X0.85MM_NO_SILK"))
    )
    (comp (ref "CLEAN323")
      (value "M01PTH_SMD_3.25X0.85MM_NO_SILK")
      (footprint "eagle-import:1X01_SMD_3.25X0.85MM_NO_SILK")
      (libsource (lib "eagle-import") (part "M01PTH_SMD_3.25X0.85MM_NO_SILK"))
    )
    (comp (ref "CLEAN324")
      (value "M01PTH_SMD_3.25X0.85MM_NO_SILK")
      (footprint "eagle-import:1X01_SMD_3.25X0.85MM_NO_SILK")
      (libsource (lib "eagle-import") (part "M01PTH_SMD_3.25X0.85MM_NO_SILK"))
    )
    (comp (ref "CLEAN325")
      (value "M01PTH_SMD_3.25X0.85MM_NO_SILK")
      (footprint "eagle-import:1X01_SMD_3.25X0.85MM_NO_SILK")
      (libsource (lib "eagle-import") (part "M01PTH_SMD_3.25X0.85MM_NO_SILK"))
    )
    (comp (ref "CLEAN326")
      (value "M01PTH_SMD_3.25X0.85MM_NO_SILK")
      (footprint "eagle-import:1X01_SMD_3.25X0.85MM_NO_SILK")
      (libsource (lib "eagle-import") (part "M01PTH_SMD_3.25X0.85MM_NO_SILK"))
    )
    (comp (ref "CLEAN327")
      (value "M01PTH_SMD_3.25X0.85MM_NO_SILK")
      (footprint "eagle-import:1X01_SMD_3.25X0.85MM_NO_SILK")
      (libsource (lib "eagle-import") (part "M01PTH_SMD_3.25X0.85MM_NO_SILK"))
    )
    (comp (ref "CLEAN328")
      (value "M01PTH_SMD_3.25X0.85MM_NO_SILK")
      (footprint "eagle-import:1X01_SMD_3.25X0.85MM_NO_SILK")
      (libsource (lib "eagle-import") (part "M01PTH_SMD_3.25X0.85MM_NO_SILK"))
    )
    (comp (ref "CLEAN329")
      (value "M01PTH_SMD_3.25X0.85MM_NO_SILK")
      (footprint "eagle-import:1X01_SMD_3.25X0.85MM_NO_SILK")
      (libsource (lib "eagle-import") (part "M01PTH_SMD_3.25X0.85MM_NO_SILK"))
    )
    (comp (ref "CLEAN330")
      (value "M01PTH_SMD_3.25X0.85MM_NO_SILK")
      (footprint "eagle-import:1X01_SMD_3.25X0.85MM_NO_SILK")
      (libsource (lib "eagle-import") (part "M01PTH_SMD_3.25X0.85MM_NO_SILK"))
    )
    (comp (ref "CLEAN331")
      (value "M01PTH_SMD_3.25X0.85MM_NO_SILK")
      (footprint "eagle-import:1X01_SMD_3.25X0.85MM_NO_SILK")
      (libsource (lib "eagle-import") (part "M01PTH_SMD_3.25X0.85MM_NO_SILK"))
    )
    (comp (ref "CLEAN332")
      (value "M01PTH_SMD_3.25X0.85MM_NO_SILK")
      (footprint "eagle-import:1X01_SMD_3.25X0.85MM_NO_SILK")
      (libsource (lib "eagle-import") (part "M01PTH_SMD_3.25X0.85MM_NO_SILK"))
    )
    (comp (ref "CLEAN333")
      (value "M01PTH_SMD_3.25X0.85MM_NO_SILK")
      (footprint "eagle-import:1X01_SMD_3.25X0.85MM_NO_SILK")
      (libsource (lib "eagle-import") (part "M01PTH_SMD_3.25X0.85MM_NO_SILK"))
    )
    (comp (ref "CLEAN334")
      (value "M01PTH_SMD_3.25X0.85MM_NO_SILK")
      (footprint "eagle-import:1X01_SMD_3.25X0.85MM_NO_SILK")
      (libsource (lib "eagle-import") (part "M01PTH_SMD_3.25X0.85MM_NO_SILK"))
    )
    (comp (ref "CLEAN335")
      (value "M01PTH_SMD_3.25X0.85MM_NO_SILK")
      (footprint "eagle-import:1X01_SMD_3.25X0.85MM_NO_SILK")
      (libsource (lib "eagle-import") (part "M01PTH_SMD_3.25X0.85MM_NO_SILK"))
    )
    (comp (ref "CLEAN336")
      (value "M01PTH_SMD_3.25X0.85MM_NO_SILK")
      (footprint "eagle-import:1X01_SMD_3.25X0.85MM_NO_SILK")
      (libsource (lib "eagle-import") (part "M01PTH_SMD_3.25X0.85MM_NO_SILK"))
    )
    (comp (ref "CLEAN337")
      (value "M01PTH_SMD_3.25X0.85MM_NO_SILK")
      (footprint "eagle-import:1X01_SMD_3.25X0.85MM_NO_SILK")
      (libsource (lib "eagle-import") (part "M01PTH_SMD_3.25X0.85MM_NO_SILK"))
    )
    (comp (ref "CLEAN338")
      (value "M01PTH_SMD_3.25X0.85MM_NO_SILK")
      (footprint "eagle-import:1X01_SMD_3.25X0.85MM_NO_SILK")
      (libsource (lib "eagle-import") (part "M01PTH_SMD_3.25X0.85MM_NO_SILK"))
    )
    (comp (ref "CLEAN339")
      (value "M01PTH_SMD_3.25X0.85MM_NO_SILK")
      (footprint "eagle-import:1X01_SMD_3.25X0.85MM_NO_SILK")
      (libsource (lib "eagle-import") (part "M01PTH_SMD_3.25X0.85MM_NO_SILK"))
    )
    (comp (ref "CLEAN340")
      (value "M01PTH_SMD_3.25X0.85MM_NO_SILK")
      (footprint "eagle-import:1X01_SMD_3.25X0.85MM_NO_SILK")
      (libsource (lib "eagle-import") (part "M01PTH_SMD_3.25X0.85MM_NO_SILK"))
    )
    (comp (ref "CLEAN341")
      (value "M01PTH_SMD_3.25X0.85MM_NO_SILK")
      (footprint "eagle-import:1X01_SMD_3.25X0.85MM_NO_SILK")
      (libsource (lib "eagle-import") (part "M01PTH_SMD_3.25X0.85MM_NO_SILK"))
    )
    (comp (ref "CLEAN342")
      (value "M01PTH_SMD_3.25X0.85MM_NO_SILK")
      (footprint "eagle-import:1X01_SMD_3.25X0.85MM_NO_SILK")
      (libsource (lib "eagle-import") (part "M01PTH_SMD_3.25X0.85MM_NO_SILK"))
    )
    (comp (ref "CLEAN343")
      (value "M01PTH_SMD_3.25X0.85MM_NO_SILK")
      (footprint "eagle-import:1X01_SMD_3.25X0.85MM_NO_SILK")
      (libsource (lib "eagle-import") (part "M01PTH_SMD_3.25X0.85MM_NO_SILK"))
    )
    (comp (ref "CLEAN344")
      (value "M01PTH_SMD_3.25X0.85MM_NO_SILK")
      (footprint "eagle-import:1X01_SMD_3.25X0.85MM_NO_SILK")
      (libsource (lib "eagle-import") (part "M01PTH_SMD_3.25X0.85MM_NO_SILK"))
    )
    (comp (ref "CLEAN345")
      (value "M01PTH_SMD_3.25X0.85MM_NO_SILK")
      (footprint "eagle-import:1X01_SMD_3.25X0.85MM_NO_SILK")
      (libsource (lib "eagle-import") (part "M01PTH_SMD_3.25X0.85MM_NO_SILK"))
    )
    (comp (ref "CLEAN346")
      (value "M01PTH_SMD_3.25X0.85MM_NO_SILK")
      (footprint "eagle-import:1X01_SMD_3.25X0.85MM_NO_SILK")
      (libsource (lib "eagle-import") (part "M01PTH_SMD_3.25X0.85MM_NO_SILK"))
    )
    (comp (ref "CLEAN347")
      (value "M01PTH_SMD_3.25X0.85MM_NO_SILK")
      (footprint "eagle-import:1X01_SMD_3.25X0.85MM_NO_SILK")
      (libsource (lib "eagle-import") (part "M01PTH_SMD_3.25X0.85MM_NO_SILK"))
    )
    (comp (ref "CLEAN348")
      (value "M01PTH_SMD_3.25X0.85MM_NO_SILK")
      (footprint "eagle-import:1X01_SMD_3.25X0.85MM_NO_SILK")
      (libsource (lib "eagle-import") (part "M01PTH_SMD_3.25X0.85MM_NO_SILK"))
    )
    (comp (ref "CLEAN349")
      (value "M01PTH_SMD_3.25X0.85MM_NO_SILK")
      (footprint "eagle-import:1X01_SMD_3.25X0.85MM_NO_SILK")
      (libsource (lib "eagle-import") (part "M01PTH_SMD_3.25X0.85MM_NO_SILK"))
    )
    (comp (ref "CLEAN350")
      (value "M01PTH_SMD_3.25X0.85MM_NO_SILK")
      (footprint "eagle-import:1X01_SMD_3.25X0.85MM_NO_SILK")
      (libsource (lib "eagle-import") (part "M01PTH_SMD_3.25X0.85MM_NO_SILK"))
    )
    (comp (ref "CLEAN351")
      (value "M01PTH_SMD_3.25X0.85MM_NO_SILK")
      (footprint "eagle-import:1X01_SMD_3.25X0.85MM_NO_SILK")
      (libsource (lib "eagle-import") (part "M01PTH_SMD_3.25X0.85MM_NO_SILK"))
    )
    (comp (ref "CLEAN352")
      (value "M01PTH_SMD_3.25X0.85MM_NO_SILK")
      (footprint "eagle-import:1X01_SMD_3.25X0.85MM_NO_SILK")
      (libsource (lib "eagle-import") (part "M01PTH_SMD_3.25X0.85MM_NO_SILK"))
    )
    (comp (ref "CLEAN353")
      (value "M01PTH_SMD_3.25X0.85MM_NO_SILK")
      (footprint "eagle-import:1X01_SMD_3.25X0.85MM_NO_SILK")
      (libsource (lib "eagle-import") (part "M01PTH_SMD_3.25X0.85MM_NO_SILK"))
    )
    (comp (ref "CLEAN354")
      (value "M01PTH_SMD_3.25X0.85MM_NO_SILK")
      (footprint "eagle-import:1X01_SMD_3.25X0.85MM_NO_SILK")
      (libsource (lib "eagle-import") (part "M01PTH_SMD_3.25X0.85MM_NO_SILK"))
    )
    (comp (ref "CLEAN355")
      (value "M01PTH_SMD_3.25X0.85MM_NO_SILK")
      (footprint "eagle-import:1X01_SMD_3.25X0.85MM_NO_SILK")
      (libsource (lib "eagle-import") (part "M01PTH_SMD_3.25X0.85MM_NO_SILK"))
    )
    (comp (ref "CLEAN356")
      (value "M01PTH_SMD_3.25X0.85MM_NO_SILK")
      (footprint "eagle-import:1X01_SMD_3.25X0.85MM_NO_SILK")
      (libsource (lib "eagle-import") (part "M01PTH_SMD_3.25X0.85MM_NO_SILK"))
    )
    (comp (ref "CLEAN357")
      (value "M01PTH_SMD_3.25X0.85MM_NO_SILK")
      (footprint "eagle-import:1X01_SMD_3.25X0.85MM_NO_SILK")
      (libsource (lib "eagle-import") (part "M01PTH_SMD_3.25X0.85MM_NO_SILK"))
    )
    (comp (ref "CLEAN358")
      (value "M01PTH_SMD_3.25X0.85MM_NO_SILK")
      (footprint "eagle-import:1X01_SMD_3.25X0.85MM_NO_SILK")
      (libsource (lib "eagle-import") (part "M01PTH_SMD_3.25X0.85MM_NO_SILK"))
    )
    (comp (ref "CLEAN359")
      (value "M01PTH_SMD_3.25X0.85MM_NO_SILK")
      (footprint "eagle-import:1X01_SMD_3.25X0.85MM_NO_SILK")
      (libsource (lib "eagle-import") (part "M01PTH_SMD_3.25X0.85MM_NO_SILK"))
    )
    (comp (ref "CLEAN360")
      (value "M01PTH_SMD_3.25X0.85MM_NO_SILK")
      (footprint "eagle-import:1X01_SMD_3.25X0.85MM_NO_SILK")
      (libsource (lib "eagle-import") (part "M01PTH_SMD_3.25X0.85MM_NO_SILK"))
    )
    (comp (ref "CLEAN361")
      (value "M01PTH_SMD_3.25X0.85MM_NO_SILK")
      (footprint "eagle-import:1X01_SMD_3.25X0.85MM_NO_SILK")
      (libsource (lib "eagle-import") (part "M01PTH_SMD_3.25X0.85MM_NO_SILK"))
    )
    (comp (ref "CLEAN362")
      (value "M01PTH_SMD_3.25X0.85MM_NO_SILK")
      (footprint "eagle-import:1X01_SMD_3.25X0.85MM_NO_SILK")
      (libsource (lib "eagle-import") (part "M01PTH_SMD_3.25X0.85MM_NO_SILK"))
    )
    (comp (ref "CLEAN363")
      (value "M01PTH_SMD_3.25X0.85MM_NO_SILK")
      (footprint "eagle-import:1X01_SMD_3.25X0.85MM_NO_SILK")
      (libsource (lib "eagle-import") (part "M01PTH_SMD_3.25X0.85MM_NO_SILK"))
    )
    (comp (ref "CLEAN364")
      (value "M01PTH_SMD_3.25X0.85MM_NO_SILK")
      (footprint "eagle-import:1X01_SMD_3.25X0.85MM_NO_SILK")
      (libsource (lib "eagle-import") (part "M01PTH_SMD_3.25X0.85MM_NO_SILK"))
    )
    (comp (ref "CLEAN365")
      (value "M01PTH_SMD_3.25X0.85MM_NO_SILK")
      (footprint "eagle-import:1X01_SMD_3.25X0.85MM_NO_SILK")
      (libsource (lib "eagle-import") (part "M01PTH_SMD_3.25X0.85MM_NO_SILK"))
    )
    (comp (ref "CLEAN366")
      (value "M01PTH_SMD_3.25X0.85MM_NO_SILK")
      (footprint "eagle-import:1X01_SMD_3.25X0.85MM_NO_SILK")
      (libsource (lib "eagle-import") (part "M01PTH_SMD_3.25X0.85MM_NO_SILK"))
    )
    (comp (ref "CLEAN367")
      (value "M01PTH_SMD_3.25X0.85MM_NO_SILK")
      (footprint "eagle-import:1X01_SMD_3.25X0.85MM_NO_SILK")
      (libsource (lib "eagle-import") (part "M01PTH_SMD_3.25X0.85MM_NO_SILK"))
    )
    (comp (ref "CLEAN368")
      (value "M01PTH_SMD_3.25X0.85MM_NO_SILK")
      (footprint "eagle-import:1X01_SMD_3.25X0.85MM_NO_SILK")
      (libsource (lib "eagle-import") (part "M01PTH_SMD_3.25X0.85MM_NO_SILK"))
    )
    (comp (ref "CLEAN369")
      (value "M01PTH_SMD_3.25X0.85MM_NO_SILK")
      (footprint "eagle-import:1X01_SMD_3.25X0.85MM_NO_SILK")
      (libsource (lib "eagle-import") (part "M01PTH_SMD_3.25X0.85MM_NO_SILK"))
    )
    (comp (ref "CLEAN370")
      (value "M01PTH_SMD_3.25X0.85MM_NO_SILK")
      (footprint "eagle-import:1X01_SMD_3.25X0.85MM_NO_SILK")
      (libsource (lib "eagle-import") (part "M01PTH_SMD_3.25X0.85MM_NO_SILK"))
    )
    (comp (ref "CLEAN371")
      (value "M01PTH_SMD_3.25X0.85MM_NO_SILK")
      (footprint "eagle-import:1X01_SMD_3.25X0.85MM_NO_SILK")
      (libsource (lib "eagle-import") (part "M01PTH_SMD_3.25X0.85MM_NO_SILK"))
    )
    (comp (ref "CLEAN372")
      (value "M01PTH_SMD_3.25X0.85MM_NO_SILK")
      (footprint "eagle-import:1X01_SMD_3.25X0.85MM_NO_SILK")
      (libsource (lib "eagle-import") (part "M01PTH_SMD_3.25X0.85MM_NO_SILK"))
    )
    (comp (ref "CLEAN373")
      (value "M01PTH_SMD_3.25X0.85MM_NO_SILK")
      (footprint "eagle-import:1X01_SMD_3.25X0.85MM_NO_SILK")
      (libsource (lib "eagle-import") (part "M01PTH_SMD_3.25X0.85MM_NO_SILK"))
    )
    (comp (ref "CLEAN374")
      (value "M01PTH_SMD_3.25X0.85MM_NO_SILK")
      (footprint "eagle-import:1X01_SMD_3.25X0.85MM_NO_SILK")
      (libsource (lib "eagle-import") (part "M01PTH_SMD_3.25X0.85MM_NO_SILK"))
    )
    (comp (ref "CLEAN375")
      (value "M01PTH_SMD_3.25X0.85MM_NO_SILK")
      (footprint "eagle-import:1X01_SMD_3.25X0.85MM_NO_SILK")
      (libsource (lib "eagle-import") (part "M01PTH_SMD_3.25X0.85MM_NO_SILK"))
    )
    (comp (ref "CLEAN376")
      (value "M01PTH_SMD_3.25X0.85MM_NO_SILK")
      (footprint "eagle-import:1X01_SMD_3.25X0.85MM_NO_SILK")
      (libsource (lib "eagle-import") (part "M01PTH_SMD_3.25X0.85MM_NO_SILK"))
    )
    (comp (ref "CLEAN377")
      (value "M01PTH_SMD_3.25X0.85MM_NO_SILK")
      (footprint "eagle-import:1X01_SMD_3.25X0.85MM_NO_SILK")
      (libsource (lib "eagle-import") (part "M01PTH_SMD_3.25X0.85MM_NO_SILK"))
    )
    (comp (ref "CLEAN378")
      (value "M01PTH_SMD_3.25X0.85MM_NO_SILK")
      (footprint "eagle-import:1X01_SMD_3.25X0.85MM_NO_SILK")
      (libsource (lib "eagle-import") (part "M01PTH_SMD_3.25X0.85MM_NO_SILK"))
    )
    (comp (ref "CLEAN379")
      (value "M01PTH_SMD_3.25X0.85MM_NO_SILK")
      (footprint "eagle-import:1X01_SMD_3.25X0.85MM_NO_SILK")
      (libsource (lib "eagle-import") (part "M01PTH_SMD_3.25X0.85MM_NO_SILK"))
    )
    (comp (ref "CLEAN380")
      (value "M01PTH_SMD_3.25X0.85MM_NO_SILK")
      (footprint "eagle-import:1X01_SMD_3.25X0.85MM_NO_SILK")
      (libsource (lib "eagle-import") (part "M01PTH_SMD_3.25X0.85MM_NO_SILK"))
    )
    (comp (ref "CLEAN381")
      (value "M01PTH_SMD_3.25X0.85MM_NO_SILK")
      (footprint "eagle-import:1X01_SMD_3.25X0.85MM_NO_SILK")
      (libsource (lib "eagle-import") (part "M01PTH_SMD_3.25X0.85MM_NO_SILK"))
    )
    (comp (ref "CLEAN382")
      (value "M01PTH_SMD_3.25X0.85MM_NO_SILK")
      (footprint "eagle-import:1X01_SMD_3.25X0.85MM_NO_SILK")
      (libsource (lib "eagle-import") (part "M01PTH_SMD_3.25X0.85MM_NO_SILK"))
    )
    (comp (ref "CLEAN383")
      (value "M01PTH_SMD_3.25X0.85MM_NO_SILK")
      (footprint "eagle-import:1X01_SMD_3.25X0.85MM_NO_SILK")
      (libsource (lib "eagle-import") (part "M01PTH_SMD_3.25X0.85MM_NO_SILK"))
    )
    (comp (ref "CLEAN384")
      (value "M01PTH_SMD_3.25X0.85MM_NO_SILK")
      (footprint "eagle-import:1X01_SMD_3.25X0.85MM_NO_SILK")
      (libsource (lib "eagle-import") (part "M01PTH_SMD_3.25X0.85MM_NO_SILK"))
    )
    (comp (ref "CLEAN385")
      (value "M01PTH_SMD_3.25X0.85MM_NO_SILK")
      (footprint "eagle-import:1X01_SMD_3.25X0.85MM_NO_SILK")
      (libsource (lib "eagle-import") (part "M01PTH_SMD_3.25X0.85MM_NO_SILK"))
    )
    (comp (ref "CLEAN386")
      (value "M01PTH_SMD_3.25X0.85MM_NO_SILK")
      (footprint "eagle-import:1X01_SMD_3.25X0.85MM_NO_SILK")
      (libsource (lib "eagle-import") (part "M01PTH_SMD_3.25X0.85MM_NO_SILK"))
    )
    (comp (ref "CLEAN387")
      (value "M01PTH_SMD_3.25X0.85MM_NO_SILK")
      (footprint "eagle-import:1X01_SMD_3.25X0.85MM_NO_SILK")
      (libsource (lib "eagle-import") (part "M01PTH_SMD_3.25X0.85MM_NO_SILK"))
    )
    (comp (ref "CLEAN388")
      (value "M01PTH_SMD_3.25X0.85MM_NO_SILK")
      (footprint "eagle-import:1X01_SMD_3.25X0.85MM_NO_SILK")
      (libsource (lib "eagle-import") (part "M01PTH_SMD_3.25X0.85MM_NO_SILK"))
    )
    (comp (ref "CLEAN389")
      (value "M01PTH_SMD_3.25X0.85MM_NO_SILK")
      (footprint "eagle-import:1X01_SMD_3.25X0.85MM_NO_SILK")
      (libsource (lib "eagle-import") (part "M01PTH_SMD_3.25X0.85MM_NO_SILK"))
    )
    (comp (ref "CLEAN390")
      (value "M01PTH_SMD_3.25X0.85MM_NO_SILK")
      (footprint "eagle-import:1X01_SMD_3.25X0.85MM_NO_SILK")
      (libsource (lib "eagle-import") (part "M01PTH_SMD_3.25X0.85MM_NO_SILK"))
    )
    (comp (ref "CLEAN391")
      (value "M01PTH_SMD_3.25X0.85MM_NO_SILK")
      (footprint "eagle-import:1X01_SMD_3.25X0.85MM_NO_SILK")
      (libsource (lib "eagle-import") (part "M01PTH_SMD_3.25X0.85MM_NO_SILK"))
    )
    (comp (ref "CLEAN392")
      (value "M01PTH_SMD_3.25X0.85MM_NO_SILK")
      (footprint "eagle-import:1X01_SMD_3.25X0.85MM_NO_SILK")
      (libsource (lib "eagle-import") (part "M01PTH_SMD_3.25X0.85MM_NO_SILK"))
    )
    (comp (ref "CLEAN393")
      (value "M01PTH_SMD_3.25X0.85MM_NO_SILK")
      (footprint "eagle-import:1X01_SMD_3.25X0.85MM_NO_SILK")
      (libsource (lib "eagle-import") (part "M01PTH_SMD_3.25X0.85MM_NO_SILK"))
    )
    (comp (ref "CLEAN394")
      (value "M01PTH_SMD_3.25X0.85MM_NO_SILK")
      (footprint "eagle-import:1X01_SMD_3.25X0.85MM_NO_SILK")
      (libsource (lib "eagle-import") (part "M01PTH_SMD_3.25X0.85MM_NO_SILK"))
    )
    (comp (ref "CLEAN395")
      (value "M01PTH_SMD_3.25X0.85MM_NO_SILK")
      (footprint "eagle-import:1X01_SMD_3.25X0.85MM_NO_SILK")
      (libsource (lib "eagle-import") (part "M01PTH_SMD_3.25X0.85MM_NO_SILK"))
    )
    (comp (ref "CLEAN396")
      (value "M01PTH_SMD_3.25X0.85MM_NO_SILK")
      (footprint "eagle-import:1X01_SMD_3.25X0.85MM_NO_SILK")
      (libsource (lib "eagle-import") (part "M01PTH_SMD_3.25X0.85MM_NO_SILK"))
    )
    (comp (ref "CLEAN397")
      (value "M01PTH_SMD_3.25X0.85MM_NO_SILK")
      (footprint "eagle-import:1X01_SMD_3.25X0.85MM_NO_SILK")
      (libsource (lib "eagle-import") (part "M01PTH_SMD_3.25X0.85MM_NO_SILK"))
    )
    (comp (ref "CLEAN398")
      (value "M01PTH_SMD_3.25X0.85MM_NO_SILK")
      (footprint "eagle-import:1X01_SMD_3.25X0.85MM_NO_SILK")
      (libsource (lib "eagle-import") (part "M01PTH_SMD_3.25X0.85MM_NO_SILK"))
    )
    (comp (ref "CLEAN399")
      (value "M01PTH_SMD_3.25X0.85MM_NO_SILK")
      (footprint "eagle-import:1X01_SMD_3.25X0.85MM_NO_SILK")
      (libsource (lib "eagle-import") (part "M01PTH_SMD_3.25X0.85MM_NO_SILK"))
    )
    (comp (ref "CLEAN400")
      (value "M01PTH_SMD_3.25X0.85MM_NO_SILK")
      (footprint "eagle-import:1X01_SMD_3.25X0.85MM_NO_SILK")
      (libsource (lib "eagle-import") (part "M01PTH_SMD_3.25X0.85MM_NO_SILK"))
    )
    (comp (ref "CLEAN401")
      (value "M01PTH_SMD_3.25X0.85MM_NO_SILK")
      (footprint "eagle-import:1X01_SMD_3.25X0.85MM_NO_SILK")
      (libsource (lib "eagle-import") (part "M01PTH_SMD_3.25X0.85MM_NO_SILK"))
    )
    (comp (ref "CLEAN402")
      (value "M01PTH_SMD_3.25X0.85MM_NO_SILK")
      (footprint "eagle-import:1X01_SMD_3.25X0.85MM_NO_SILK")
      (libsource (lib "eagle-import") (part "M01PTH_SMD_3.25X0.85MM_NO_SILK"))
    )
    (comp (ref "CLEAN403")
      (value "M01PTH_SMD_3.25X0.85MM_NO_SILK")
      (footprint "eagle-import:1X01_SMD_3.25X0.85MM_NO_SILK")
      (libsource (lib "eagle-import") (part "M01PTH_SMD_3.25X0.85MM_NO_SILK"))
    )
    (comp (ref "CLEAN404")
      (value "M01PTH_SMD_3.25X0.85MM_NO_SILK")
      (footprint "eagle-import:1X01_SMD_3.25X0.85MM_NO_SILK")
      (libsource (lib "eagle-import") (part "M01PTH_SMD_3.25X0.85MM_NO_SILK"))
    )
    (comp (ref "CLEAN405")
      (value "M01PTH_SMD_3.25X0.85MM_NO_SILK")
      (footprint "eagle-import:1X01_SMD_3.25X0.85MM_NO_SILK")
      (libsource (lib "eagle-import") (part "M01PTH_SMD_3.25X0.85MM_NO_SILK"))
    )
    (comp (ref "CLEAN406")
      (value "M01PTH_SMD_3.25X0.85MM_NO_SILK")
      (footprint "eagle-import:1X01_SMD_3.25X0.85MM_NO_SILK")
      (libsource (lib "eagle-import") (part "M01PTH_SMD_3.25X0.85MM_NO_SILK"))
    )
    (comp (ref "CLEAN407")
      (value "M01PTH_SMD_3.25X0.85MM_NO_SILK")
      (footprint "eagle-import:1X01_SMD_3.25X0.85MM_NO_SILK")
      (libsource (lib "eagle-import") (part "M01PTH_SMD_3.25X0.85MM_NO_SILK"))
    )
    (comp (ref "CLEAN408")
      (value "M01PTH_SMD_3.25X0.85MM_NO_SILK")
      (footprint "eagle-import:1X01_SMD_3.25X0.85MM_NO_SILK")
      (libsource (lib "eagle-import") (part "M01PTH_SMD_3.25X0.85MM_NO_SILK"))
    )
    (comp (ref "CLEAN409")
      (value "M01PTH_SMD_3.25X0.85MM_NO_SILK")
      (footprint "eagle-import:1X01_SMD_3.25X0.85MM_NO_SILK")
      (libsource (lib "eagle-import") (part "M01PTH_SMD_3.25X0.85MM_NO_SILK"))
    )
    (comp (ref "CLEAN410")
      (value "M01PTH_SMD_3.25X0.85MM_NO_SILK")
      (footprint "eagle-import:1X01_SMD_3.25X0.85MM_NO_SILK")
      (libsource (lib "eagle-import") (part "M01PTH_SMD_3.25X0.85MM_NO_SILK"))
    )
    (comp (ref "CLEAN411")
      (value "M01PTH_SMD_3.25X0.85MM_NO_SILK")
      (footprint "eagle-import:1X01_SMD_3.25X0.85MM_NO_SILK")
      (libsource (lib "eagle-import") (part "M01PTH_SMD_3.25X0.85MM_NO_SILK"))
    )
    (comp (ref "CLEAN412")
      (value "M01PTH_SMD_3.25X0.85MM_NO_SILK")
      (footprint "eagle-import:1X01_SMD_3.25X0.85MM_NO_SILK")
      (libsource (lib "eagle-import") (part "M01PTH_SMD_3.25X0.85MM_NO_SILK"))
    )
    (comp (ref "CLEAN413")
      (value "M01PTH_SMD_3.25X0.85MM_NO_SILK")
      (footprint "eagle-import:1X01_SMD_3.25X0.85MM_NO_SILK")
      (libsource (lib "eagle-import") (part "M01PTH_SMD_3.25X0.85MM_NO_SILK"))
    )
    (comp (ref "CLEAN414")
      (value "M01PTH_SMD_3.25X0.85MM_NO_SILK")
      (footprint "eagle-import:1X01_SMD_3.25X0.85MM_NO_SILK")
      (libsource (lib "eagle-import") (part "M01PTH_SMD_3.25X0.85MM_NO_SILK"))
    )
    (comp (ref "CLEAN415")
      (value "M01PTH_SMD_3.25X0.85MM_NO_SILK")
      (footprint "eagle-import:1X01_SMD_3.25X0.85MM_NO_SILK")
      (libsource (lib "eagle-import") (part "M01PTH_SMD_3.25X0.85MM_NO_SILK"))
    )
    (comp (ref "CLEAN416")
      (value "M01PTH_SMD_3.25X0.85MM_NO_SILK")
      (footprint "eagle-import:1X01_SMD_3.25X0.85MM_NO_SILK")
      (libsource (lib "eagle-import") (part "M01PTH_SMD_3.25X0.85MM_NO_SILK"))
    )
    (comp (ref "CLEAN417")
      (value "M01PTH_SMD_3.25X0.85MM_NO_SILK")
      (footprint "eagle-import:1X01_SMD_3.25X0.85MM_NO_SILK")
      (libsource (lib "eagle-import") (part "M01PTH_SMD_3.25X0.85MM_NO_SILK"))
    )
    (comp (ref "CLEAN418")
      (value "M01PTH_SMD_3.25X0.85MM_NO_SILK")
      (footprint "eagle-import:1X01_SMD_3.25X0.85MM_NO_SILK")
      (libsource (lib "eagle-import") (part "M01PTH_SMD_3.25X0.85MM_NO_SILK"))
    )
    (comp (ref "CLEAN419")
      (value "M01PTH_SMD_3.25X0.85MM_NO_SILK")
      (footprint "eagle-import:1X01_SMD_3.25X0.85MM_NO_SILK")
      (libsource (lib "eagle-import") (part "M01PTH_SMD_3.25X0.85MM_NO_SILK"))
    )
    (comp (ref "CLEAN420")
      (value "M01PTH_SMD_3.25X0.85MM_NO_SILK")
      (footprint "eagle-import:1X01_SMD_3.25X0.85MM_NO_SILK")
      (libsource (lib "eagle-import") (part "M01PTH_SMD_3.25X0.85MM_NO_SILK"))
    )
    (comp (ref "CLEAN421")
      (value "M01PTH_SMD_3.25X0.85MM_NO_SILK")
      (footprint "eagle-import:1X01_SMD_3.25X0.85MM_NO_SILK")
      (libsource (lib "eagle-import") (part "M01PTH_SMD_3.25X0.85MM_NO_SILK"))
    )
    (comp (ref "CLEAN422")
      (value "M01PTH_SMD_3.25X0.85MM_NO_SILK")
      (footprint "eagle-import:1X01_SMD_3.25X0.85MM_NO_SILK")
      (libsource (lib "eagle-import") (part "M01PTH_SMD_3.25X0.85MM_NO_SILK"))
    )
    (comp (ref "CLEAN423")
      (value "M01PTH_SMD_3.25X0.85MM_NO_SILK")
      (footprint "eagle-import:1X01_SMD_3.25X0.85MM_NO_SILK")
      (libsource (lib "eagle-import") (part "M01PTH_SMD_3.25X0.85MM_NO_SILK"))
    )
    (comp (ref "CLEAN424")
      (value "M01PTH_SMD_3.25X0.85MM_NO_SILK")
      (footprint "eagle-import:1X01_SMD_3.25X0.85MM_NO_SILK")
      (libsource (lib "eagle-import") (part "M01PTH_SMD_3.25X0.85MM_NO_SILK"))
    )
    (comp (ref "CLEAN425")
      (value "M01PTH_SMD_3.25X0.85MM_NO_SILK")
      (footprint "eagle-import:1X01_SMD_3.25X0.85MM_NO_SILK")
      (libsource (lib "eagle-import") (part "M01PTH_SMD_3.25X0.85MM_NO_SILK"))
    )
    (comp (ref "CLEAN426")
      (value "M01PTH_SMD_3.25X0.85MM_NO_SILK")
      (footprint "eagle-import:1X01_SMD_3.25X0.85MM_NO_SILK")
      (libsource (lib "eagle-import") (part "M01PTH_SMD_3.25X0.85MM_NO_SILK"))
    )
    (comp (ref "CLEAN427")
      (value "M01PTH_SMD_3.25X0.85MM_NO_SILK")
      (footprint "eagle-import:1X01_SMD_3.25X0.85MM_NO_SILK")
      (libsource (lib "eagle-import") (part "M01PTH_SMD_3.25X0.85MM_NO_SILK"))
    )
    (comp (ref "CLEAN428")
      (value "M01PTH_SMD_3.25X0.85MM_NO_SILK")
      (footprint "eagle-import:1X01_SMD_3.25X0.85MM_NO_SILK")
      (libsource (lib "eagle-import") (part "M01PTH_SMD_3.25X0.85MM_NO_SILK"))
    )
    (comp (ref "CLEAN429")
      (value "M01PTH_SMD_3.25X0.85MM_NO_SILK")
      (footprint "eagle-import:1X01_SMD_3.25X0.85MM_NO_SILK")
      (libsource (lib "eagle-import") (part "M01PTH_SMD_3.25X0.85MM_NO_SILK"))
    )
    (comp (ref "CLEAN430")
      (value "M01PTH_SMD_3.25X0.85MM_NO_SILK")
      (footprint "eagle-import:1X01_SMD_3.25X0.85MM_NO_SILK")
      (libsource (lib "eagle-import") (part "M01PTH_SMD_3.25X0.85MM_NO_SILK"))
    )
    (comp (ref "CLEAN431")
      (value "M01PTH_SMD_3.25X0.85MM_NO_SILK")
      (footprint "eagle-import:1X01_SMD_3.25X0.85MM_NO_SILK")
      (libsource (lib "eagle-import") (part "M01PTH_SMD_3.25X0.85MM_NO_SILK"))
    )
    (comp (ref "CLEAN432")
      (value "M01PTH_SMD_3.25X0.85MM_NO_SILK")
      (footprint "eagle-import:1X01_SMD_3.25X0.85MM_NO_SILK")
      (libsource (lib "eagle-import") (part "M01PTH_SMD_3.25X0.85MM_NO_SILK"))
    )
    (comp (ref "CLEAN433")
      (value "M01PTH_SMD_3.25X0.85MM_NO_SILK")
      (footprint "eagle-import:1X01_SMD_3.25X0.85MM_NO_SILK")
      (libsource (lib "eagle-import") (part "M01PTH_SMD_3.25X0.85MM_NO_SILK"))
    )
    (comp (ref "CLEAN434")
      (value "M01PTH_SMD_3.25X0.85MM_NO_SILK")
      (footprint "eagle-import:1X01_SMD_3.25X0.85MM_NO_SILK")
      (libsource (lib "eagle-import") (part "M01PTH_SMD_3.25X0.85MM_NO_SILK"))
    )
    (comp (ref "CLEAN435")
      (value "M01PTH_SMD_3.25X0.85MM_NO_SILK")
      (footprint "eagle-import:1X01_SMD_3.25X0.85MM_NO_SILK")
      (libsource (lib "eagle-import") (part "M01PTH_SMD_3.25X0.85MM_NO_SILK"))
    )
    (comp (ref "CLEAN436")
      (value "M01PTH_SMD_3.25X0.85MM_NO_SILK")
      (footprint "eagle-import:1X01_SMD_3.25X0.85MM_NO_SILK")
      (libsource (lib "eagle-import") (part "M01PTH_SMD_3.25X0.85MM_NO_SILK"))
    )
    (comp (ref "CLEAN437")
      (value "M01PTH_SMD_3.25X0.85MM_NO_SILK")
      (footprint "eagle-import:1X01_SMD_3.25X0.85MM_NO_SILK")
      (libsource (lib "eagle-import") (part "M01PTH_SMD_3.25X0.85MM_NO_SILK"))
    )
    (comp (ref "CLEAN438")
      (value "M01PTH_SMD_3.25X0.85MM_NO_SILK")
      (footprint "eagle-import:1X01_SMD_3.25X0.85MM_NO_SILK")
      (libsource (lib "eagle-import") (part "M01PTH_SMD_3.25X0.85MM_NO_SILK"))
    )
    (comp (ref "CLEAN439")
      (value "M01PTH_SMD_3.25X0.85MM_NO_SILK")
      (footprint "eagle-import:1X01_SMD_3.25X0.85MM_NO_SILK")
      (libsource (lib "eagle-import") (part "M01PTH_SMD_3.25X0.85MM_NO_SILK"))
    )
    (comp (ref "CLEAN440")
      (value "M01PTH_SMD_3.25X0.85MM_NO_SILK")
      (footprint "eagle-import:1X01_SMD_3.25X0.85MM_NO_SILK")
      (libsource (lib "eagle-import") (part "M01PTH_SMD_3.25X0.85MM_NO_SILK"))
    )
    (comp (ref "CLEAN441")
      (value "M01PTH_SMD_3.25X0.85MM_NO_SILK")
      (footprint "eagle-import:1X01_SMD_3.25X0.85MM_NO_SILK")
      (libsource (lib "eagle-import") (part "M01PTH_SMD_3.25X0.85MM_NO_SILK"))
    )
    (comp (ref "CLEAN442")
      (value "M01PTH_SMD_3.25X0.85MM_NO_SILK")
      (footprint "eagle-import:1X01_SMD_3.25X0.85MM_NO_SILK")
      (libsource (lib "eagle-import") (part "M01PTH_SMD_3.25X0.85MM_NO_SILK"))
    )
    (comp (ref "CLEAN443")
      (value "M01PTH_SMD_3.25X0.85MM_NO_SILK")
      (footprint "eagle-import:1X01_SMD_3.25X0.85MM_NO_SILK")
      (libsource (lib "eagle-import") (part "M01PTH_SMD_3.25X0.85MM_NO_SILK"))
    )
    (comp (ref "CLEAN444")
      (value "M01PTH_SMD_3.25X0.85MM_NO_SILK")
      (footprint "eagle-import:1X01_SMD_3.25X0.85MM_NO_SILK")
      (libsource (lib "eagle-import") (part "M01PTH_SMD_3.25X0.85MM_NO_SILK"))
    )
    (comp (ref "CLEAN445")
      (value "M01PTH_SMD_3.25X0.85MM_NO_SILK")
      (footprint "eagle-import:1X01_SMD_3.25X0.85MM_NO_SILK")
      (libsource (lib "eagle-import") (part "M01PTH_SMD_3.25X0.85MM_NO_SILK"))
    )
    (comp (ref "CLEAN446")
      (value "M01PTH_SMD_3.25X0.85MM_NO_SILK")
      (footprint "eagle-import:1X01_SMD_3.25X0.85MM_NO_SILK")
      (libsource (lib "eagle-import") (part "M01PTH_SMD_3.25X0.85MM_NO_SILK"))
    )
    (comp (ref "CLEAN447")
      (value "M01PTH_SMD_3.25X0.85MM_NO_SILK")
      (footprint "eagle-import:1X01_SMD_3.25X0.85MM_NO_SILK")
      (libsource (lib "eagle-import") (part "M01PTH_SMD_3.25X0.85MM_NO_SILK"))
    )
    (comp (ref "CLEAN448")
      (value "M01PTH_SMD_3.25X0.85MM_NO_SILK")
      (footprint "eagle-import:1X01_SMD_3.25X0.85MM_NO_SILK")
      (libsource (lib "eagle-import") (part "M01PTH_SMD_3.25X0.85MM_NO_SILK"))
    )
    (comp (ref "CLEAN449")
      (value "M01PTH_SMD_3.25X0.85MM_NO_SILK")
      (footprint "eagle-import:1X01_SMD_3.25X0.85MM_NO_SILK")
      (libsource (lib "eagle-import") (part "M01PTH_SMD_3.25X0.85MM_NO_SILK"))
    )
    (comp (ref "CLEAN450")
      (value "M01PTH_SMD_3.25X0.85MM_NO_SILK")
      (footprint "eagle-import:1X01_SMD_3.25X0.85MM_NO_SILK")
      (libsource (lib "eagle-import") (part "M01PTH_SMD_3.25X0.85MM_NO_SILK"))
    )
    (comp (ref "CLEAN451")
      (value "M01PTH_SMD_3.25X0.85MM_NO_SILK")
      (footprint "eagle-import:1X01_SMD_3.25X0.85MM_NO_SILK")
      (libsource (lib "eagle-import") (part "M01PTH_SMD_3.25X0.85MM_NO_SILK"))
    )
    (comp (ref "CLEAN452")
      (value "M01PTH_SMD_3.25X0.85MM_NO_SILK")
      (footprint "eagle-import:1X01_SMD_3.25X0.85MM_NO_SILK")
      (libsource (lib "eagle-import") (part "M01PTH_SMD_3.25X0.85MM_NO_SILK"))
    )
    (comp (ref "CLEAN453")
      (value "M01PTH_SMD_3.25X0.85MM_NO_SILK")
      (footprint "eagle-import:1X01_SMD_3.25X0.85MM_NO_SILK")
      (libsource (lib "eagle-import") (part "M01PTH_SMD_3.25X0.85MM_NO_SILK"))
    )
    (comp (ref "CLEAN454")
      (value "M01PTH_SMD_3.25X0.85MM_NO_SILK")
      (footprint "eagle-import:1X01_SMD_3.25X0.85MM_NO_SILK")
      (libsource (lib "eagle-import") (part "M01PTH_SMD_3.25X0.85MM_NO_SILK"))
    )
    (comp (ref "CLEAN455")
      (value "M01PTH_SMD_3.25X0.85MM_NO_SILK")
      (footprint "eagle-import:1X01_SMD_3.25X0.85MM_NO_SILK")
      (libsource (lib "eagle-import") (part "M01PTH_SMD_3.25X0.85MM_NO_SILK"))
    )
    (comp (ref "CLEAN456")
      (value "M01PTH_SMD_3.25X0.85MM_NO_SILK")
      (footprint "eagle-import:1X01_SMD_3.25X0.85MM_NO_SILK")
      (libsource (lib "eagle-import") (part "M01PTH_SMD_3.25X0.85MM_NO_SILK"))
    )
    (comp (ref "CLEAN457")
      (value "M01PTH_SMD_3.25X0.85MM_NO_SILK")
      (footprint "eagle-import:1X01_SMD_3.25X0.85MM_NO_SILK")
      (libsource (lib "eagle-import") (part "M01PTH_SMD_3.25X0.85MM_NO_SILK"))
    )
    (comp (ref "CLEAN458")
      (value "M01PTH_SMD_3.25X0.85MM_NO_SILK")
      (footprint "eagle-import:1X01_SMD_3.25X0.85MM_NO_SILK")
      (libsource (lib "eagle-import") (part "M01PTH_SMD_3.25X0.85MM_NO_SILK"))
    )
    (comp (ref "CLEAN459")
      (value "M01PTH_SMD_3.25X0.85MM_NO_SILK")
      (footprint "eagle-import:1X01_SMD_3.25X0.85MM_NO_SILK")
      (libsource (lib "eagle-import") (part "M01PTH_SMD_3.25X0.85MM_NO_SILK"))
    )
    (comp (ref "CLEAN460")
      (value "M01PTH_SMD_3.25X0.85MM_NO_SILK")
      (footprint "eagle-import:1X01_SMD_3.25X0.85MM_NO_SILK")
      (libsource (lib "eagle-import") (part "M01PTH_SMD_3.25X0.85MM_NO_SILK"))
    )
    (comp (ref "CLEAN461")
      (value "M01PTH_SMD_3.25X0.85MM_NO_SILK")
      (footprint "eagle-import:1X01_SMD_3.25X0.85MM_NO_SILK")
      (libsource (lib "eagle-import") (part "M01PTH_SMD_3.25X0.85MM_NO_SILK"))
    )
    (comp (ref "CLEAN462")
      (value "M01PTH_SMD_3.25X0.85MM_NO_SILK")
      (footprint "eagle-import:1X01_SMD_3.25X0.85MM_NO_SILK")
      (libsource (lib "eagle-import") (part "M01PTH_SMD_3.25X0.85MM_NO_SILK"))
    )
    (comp (ref "CLEAN463")
      (value "M01PTH_SMD_3.25X0.85MM_NO_SILK")
      (footprint "eagle-import:1X01_SMD_3.25X0.85MM_NO_SILK")
      (libsource (lib "eagle-import") (part "M01PTH_SMD_3.25X0.85MM_NO_SILK"))
    )
    (comp (ref "CLEAN464")
      (value "M01PTH_SMD_3.25X0.85MM_NO_SILK")
      (footprint "eagle-import:1X01_SMD_3.25X0.85MM_NO_SILK")
      (libsource (lib "eagle-import") (part "M01PTH_SMD_3.25X0.85MM_NO_SILK"))
    )
    (comp (ref "CLEAN465")
      (value "M01PTH_SMD_3.25X0.85MM_NO_SILK")
      (footprint "eagle-import:1X01_SMD_3.25X0.85MM_NO_SILK")
      (libsource (lib "eagle-import") (part "M01PTH_SMD_3.25X0.85MM_NO_SILK"))
    )
    (comp (ref "CLEAN466")
      (value "M01PTH_SMD_3.25X0.85MM_NO_SILK")
      (footprint "eagle-import:1X01_SMD_3.25X0.85MM_NO_SILK")
      (libsource (lib "eagle-import") (part "M01PTH_SMD_3.25X0.85MM_NO_SILK"))
    )
    (comp (ref "CLEAN467")
      (value "M01PTH_SMD_3.25X0.85MM_NO_SILK")
      (footprint "eagle-import:1X01_SMD_3.25X0.85MM_NO_SILK")
      (libsource (lib "eagle-import") (part "M01PTH_SMD_3.25X0.85MM_NO_SILK"))
    )
    (comp (ref "CLEAN468")
      (value "M01PTH_SMD_3.25X0.85MM_NO_SILK")
      (footprint "eagle-import:1X01_SMD_3.25X0.85MM_NO_SILK")
      (libsource (lib "eagle-import") (part "M01PTH_SMD_3.25X0.85MM_NO_SILK"))
    )
    (comp (ref "CLEAN469")
      (value "M01PTH_SMD_3.25X0.85MM_NO_SILK")
      (footprint "eagle-import:1X01_SMD_3.25X0.85MM_NO_SILK")
      (libsource (lib "eagle-import") (part "M01PTH_SMD_3.25X0.85MM_NO_SILK"))
    )
    (comp (ref "CLEAN470")
      (value "M01PTH_SMD_3.25X0.85MM_NO_SILK")
      (footprint "eagle-import:1X01_SMD_3.25X0.85MM_NO_SILK")
      (libsource (lib "eagle-import") (part "M01PTH_SMD_3.25X0.85MM_NO_SILK"))
    )
    (comp (ref "CLEAN471")
      (value "M01PTH_SMD_3.25X0.85MM_NO_SILK")
      (footprint "eagle-import:1X01_SMD_3.25X0.85MM_NO_SILK")
      (libsource (lib "eagle-import") (part "M01PTH_SMD_3.25X0.85MM_NO_SILK"))
    )
    (comp (ref "CLEAN472")
      (value "M01PTH_SMD_3.25X0.85MM_NO_SILK")
      (footprint "eagle-import:1X01_SMD_3.25X0.85MM_NO_SILK")
      (libsource (lib "eagle-import") (part "M01PTH_SMD_3.25X0.85MM_NO_SILK"))
    )
    (comp (ref "CLEAN473")
      (value "M01PTH_SMD_3.25X0.85MM_NO_SILK")
      (footprint "eagle-import:1X01_SMD_3.25X0.85MM_NO_SILK")
      (libsource (lib "eagle-import") (part "M01PTH_SMD_3.25X0.85MM_NO_SILK"))
    )
    (comp (ref "CLEAN474")
      (value "M01PTH_SMD_3.25X0.85MM_NO_SILK")
      (footprint "eagle-import:1X01_SMD_3.25X0.85MM_NO_SILK")
      (libsource (lib "eagle-import") (part "M01PTH_SMD_3.25X0.85MM_NO_SILK"))
    )
    (comp (ref "CLEAN475")
      (value "M01PTH_SMD_3.25X0.85MM_NO_SILK")
      (footprint "eagle-import:1X01_SMD_3.25X0.85MM_NO_SILK")
      (libsource (lib "eagle-import") (part "M01PTH_SMD_3.25X0.85MM_NO_SILK"))
    )
    (comp (ref "CLEAN476")
      (value "M01PTH_SMD_3.25X0.85MM_NO_SILK")
      (footprint "eagle-import:1X01_SMD_3.25X0.85MM_NO_SILK")
      (libsource (lib "eagle-import") (part "M01PTH_SMD_3.25X0.85MM_NO_SILK"))
    )
    (comp (ref "CLEAN477")
      (value "M01PTH_SMD_3.25X0.85MM_NO_SILK")
      (footprint "eagle-import:1X01_SMD_3.25X0.85MM_NO_SILK")
      (libsource (lib "eagle-import") (part "M01PTH_SMD_3.25X0.85MM_NO_SILK"))
    )
    (comp (ref "CLEAN478")
      (value "M01PTH_SMD_3.25X0.85MM_NO_SILK")
      (footprint "eagle-import:1X01_SMD_3.25X0.85MM_NO_SILK")
      (libsource (lib "eagle-import") (part "M01PTH_SMD_3.25X0.85MM_NO_SILK"))
    )
    (comp (ref "CLEAN479")
      (value "M01PTH_SMD_3.25X0.85MM_NO_SILK")
      (footprint "eagle-import:1X01_SMD_3.25X0.85MM_NO_SILK")
      (libsource (lib "eagle-import") (part "M01PTH_SMD_3.25X0.85MM_NO_SILK"))
    )
    (comp (ref "CLEAN480")
      (value "M01PTH_SMD_3.25X0.85MM_NO_SILK")
      (footprint "eagle-import:1X01_SMD_3.25X0.85MM_NO_SILK")
      (libsource (lib "eagle-import") (part "M01PTH_SMD_3.25X0.85MM_NO_SILK"))
    )
    (comp (ref "CLEAN481")
      (value "M01PTH_SMD_3.25X0.85MM_NO_SILK")
      (footprint "eagle-import:1X01_SMD_3.25X0.85MM_NO_SILK")
      (libsource (lib "eagle-import") (part "M01PTH_SMD_3.25X0.85MM_NO_SILK"))
    )
    (comp (ref "CLEAN482")
      (value "M01PTH_SMD_3.25X0.85MM_NO_SILK")
      (footprint "eagle-import:1X01_SMD_3.25X0.85MM_NO_SILK")
      (libsource (lib "eagle-import") (part "M01PTH_SMD_3.25X0.85MM_NO_SILK"))
    )
    (comp (ref "CLEAN483")
      (value "M01PTH_SMD_3.25X0.85MM_NO_SILK")
      (footprint "eagle-import:1X01_SMD_3.25X0.85MM_NO_SILK")
      (libsource (lib "eagle-import") (part "M01PTH_SMD_3.25X0.85MM_NO_SILK"))
    )
    (comp (ref "CLEAN484")
      (value "M01PTH_SMD_3.25X0.85MM_NO_SILK")
      (footprint "eagle-import:1X01_SMD_3.25X0.85MM_NO_SILK")
      (libsource (lib "eagle-import") (part "M01PTH_SMD_3.25X0.85MM_NO_SILK"))
    )
    (comp (ref "CLEAN485")
      (value "M01PTH_SMD_3.25X0.85MM_NO_SILK")
      (footprint "eagle-import:1X01_SMD_3.25X0.85MM_NO_SILK")
      (libsource (lib "eagle-import") (part "M01PTH_SMD_3.25X0.85MM_NO_SILK"))
    )
    (comp (ref "CLEAN486")
      (value "M01PTH_SMD_3.25X0.85MM_NO_SILK")
      (footprint "eagle-import:1X01_SMD_3.25X0.85MM_NO_SILK")
      (libsource (lib "eagle-import") (part "M01PTH_SMD_3.25X0.85MM_NO_SILK"))
    )
    (comp (ref "CLEAN487")
      (value "M01PTH_SMD_3.25X0.85MM_NO_SILK")
      (footprint "eagle-import:1X01_SMD_3.25X0.85MM_NO_SILK")
      (libsource (lib "eagle-import") (part "M01PTH_SMD_3.25X0.85MM_NO_SILK"))
    )
    (comp (ref "CLEAN488")
      (value "M01PTH_SMD_3.25X0.85MM_NO_SILK")
      (footprint "eagle-import:1X01_SMD_3.25X0.85MM_NO_SILK")
      (libsource (lib "eagle-import") (part "M01PTH_SMD_3.25X0.85MM_NO_SILK"))
    )
    (comp (ref "CLEAN489")
      (value "M01PTH_SMD_3.25X0.85MM_NO_SILK")
      (footprint "eagle-import:1X01_SMD_3.25X0.85MM_NO_SILK")
      (libsource (lib "eagle-import") (part "M01PTH_SMD_3.25X0.85MM_NO_SILK"))
    )
    (comp (ref "CLEAN490")
      (value "M01PTH_SMD_3.25X0.85MM_NO_SILK")
      (footprint "eagle-import:1X01_SMD_3.25X0.85MM_NO_SILK")
      (libsource (lib "eagle-import") (part "M01PTH_SMD_3.25X0.85MM_NO_SILK"))
    )
    (comp (ref "CLEAN491")
      (value "M01PTH_SMD_3.25X0.85MM_NO_SILK")
      (footprint "eagle-import:1X01_SMD_3.25X0.85MM_NO_SILK")
      (libsource (lib "eagle-import") (part "M01PTH_SMD_3.25X0.85MM_NO_SILK"))
    )
    (comp (ref "CLEAN492")
      (value "M01PTH_SMD_3.25X0.85MM_NO_SILK")
      (footprint "eagle-import:1X01_SMD_3.25X0.85MM_NO_SILK")
      (libsource (lib "eagle-import") (part "M01PTH_SMD_3.25X0.85MM_NO_SILK"))
    )
    (comp (ref "CLEAN493")
      (value "M01PTH_SMD_3.25X0.85MM_NO_SILK")
      (footprint "eagle-import:1X01_SMD_3.25X0.85MM_NO_SILK")
      (libsource (lib "eagle-import") (part "M01PTH_SMD_3.25X0.85MM_NO_SILK"))
    )
    (comp (ref "CLEAN494")
      (value "M01PTH_SMD_3.25X0.85MM_NO_SILK")
      (footprint "eagle-import:1X01_SMD_3.25X0.85MM_NO_SILK")
      (libsource (lib "eagle-import") (part "M01PTH_SMD_3.25X0.85MM_NO_SILK"))
    )
    (comp (ref "CLEAN495")
      (value "M01PTH_SMD_3.25X0.85MM_NO_SILK")
      (footprint "eagle-import:1X01_SMD_3.25X0.85MM_NO_SILK")
      (libsource (lib "eagle-import") (part "M01PTH_SMD_3.25X0.85MM_NO_SILK"))
    )
    (comp (ref "CLEAN496")
      (value "M01PTH_SMD_3.25X0.85MM_NO_SILK")
      (footprint "eagle-import:1X01_SMD_3.25X0.85MM_NO_SILK")
      (libsource (lib "eagle-import") (part "M01PTH_SMD_3.25X0.85MM_NO_SILK"))
    )
    (comp (ref "CLEAN497")
      (value "M01PTH_SMD_3.25X0.85MM_NO_SILK")
      (footprint "eagle-import:1X01_SMD_3.25X0.85MM_NO_SILK")
      (libsource (lib "eagle-import") (part "M01PTH_SMD_3.25X0.85MM_NO_SILK"))
    )
    (comp (ref "CLEAN498")
      (value "M01PTH_SMD_3.25X0.85MM_NO_SILK")
      (footprint "eagle-import:1X01_SMD_3.25X0.85MM_NO_SILK")
      (libsource (lib "eagle-import") (part "M01PTH_SMD_3.25X0.85MM_NO_SILK"))
    )
    (comp (ref "CLEAN499")
      (value "M01PTH_SMD_3.25X0.85MM_NO_SILK")
      (footprint "eagle-import:1X01_SMD_3.25X0.85MM_NO_SILK")
      (libsource (lib "eagle-import") (part "M01PTH_SMD_3.25X0.85MM_NO_SILK"))
    )
    (comp (ref "CLEAN500")
      (value "M01PTH_SMD_3.25X0.85MM_NO_SILK")
      (footprint "eagle-import:1X01_SMD_3.25X0.85MM_NO_SILK")
      (libsource (lib "eagle-import") (part "M01PTH_SMD_3.25X0.85MM_NO_SILK"))
    )
    (comp (ref "CLEAN501")
      (value "M01PTH_SMD_3.25X0.85MM_NO_SILK")
      (footprint "eagle-import:1X01_SMD_3.25X0.85MM_NO_SILK")
      (libsource (lib "eagle-import") (part "M01PTH_SMD_3.25X0.85MM_NO_SILK"))
    )
    (comp (ref "CLEAN502")
      (value "M01PTH_SMD_3.25X0.85MM_NO_SILK")
      (footprint "eagle-import:1X01_SMD_3.25X0.85MM_NO_SILK")
      (libsource (lib "eagle-import") (part "M01PTH_SMD_3.25X0.85MM_NO_SILK"))
    )
    (comp (ref "CLEAN503")
      (value "M01PTH_SMD_3.25X0.85MM_NO_SILK")
      (footprint "eagle-import:1X01_SMD_3.25X0.85MM_NO_SILK")
      (libsource (lib "eagle-import") (part "M01PTH_SMD_3.25X0.85MM_NO_SILK"))
    )
    (comp (ref "CLEAN504")
      (value "M01PTH_SMD_3.25X0.85MM_NO_SILK")
      (footprint "eagle-import:1X01_SMD_3.25X0.85MM_NO_SILK")
      (libsource (lib "eagle-import") (part "M01PTH_SMD_3.25X0.85MM_NO_SILK"))
    )
    (comp (ref "CLEAN505")
      (value "M01PTH_SMD_3.25X0.85MM_NO_SILK")
      (footprint "eagle-import:1X01_SMD_3.25X0.85MM_NO_SILK")
      (libsource (lib "eagle-import") (part "M01PTH_SMD_3.25X0.85MM_NO_SILK"))
    )
    (comp (ref "CLEAN506")
      (value "M01PTH_SMD_3.25X0.85MM_NO_SILK")
      (footprint "eagle-import:1X01_SMD_3.25X0.85MM_NO_SILK")
      (libsource (lib "eagle-import") (part "M01PTH_SMD_3.25X0.85MM_NO_SILK"))
    )
    (comp (ref "CLEAN507")
      (value "M01PTH_SMD_3.25X0.85MM_NO_SILK")
      (footprint "eagle-import:1X01_SMD_3.25X0.85MM_NO_SILK")
      (libsource (lib "eagle-import") (part "M01PTH_SMD_3.25X0.85MM_NO_SILK"))
    )
    (comp (ref "CLEAN508")
      (value "M01PTH_SMD_3.25X0.85MM_NO_SILK")
      (footprint "eagle-import:1X01_SMD_3.25X0.85MM_NO_SILK")
      (libsource (lib "eagle-import") (part "M01PTH_SMD_3.25X0.85MM_NO_SILK"))
    )
    (comp (ref "CLEAN509")
      (value "M01PTH_SMD_3.25X0.85MM_NO_SILK")
      (footprint "eagle-import:1X01_SMD_3.25X0.85MM_NO_SILK")
      (libsource (lib "eagle-import") (part "M01PTH_SMD_3.25X0.85MM_NO_SILK"))
    )
    (comp (ref "CLEAN510")
      (value "M01PTH_SMD_3.25X0.85MM_NO_SILK")
      (footprint "eagle-import:1X01_SMD_3.25X0.85MM_NO_SILK")
      (libsource (lib "eagle-import") (part "M01PTH_SMD_3.25X0.85MM_NO_SILK"))
    )
    (comp (ref "CLEAN511")
      (value "M01PTH_SMD_3.25X0.85MM_NO_SILK")
      (footprint "eagle-import:1X01_SMD_3.25X0.85MM_NO_SILK")
      (libsource (lib "eagle-import") (part "M01PTH_SMD_3.25X0.85MM_NO_SILK"))
    )
    (comp (ref "CLEAN512")
      (value "M01PTH_SMD_3.25X0.85MM_NO_SILK")
      (footprint "eagle-import:1X01_SMD_3.25X0.85MM_NO_SILK")
      (libsource (lib "eagle-import") (part "M01PTH_SMD_3.25X0.85MM_NO_SILK"))
    )
    (comp (ref "CLEAN513")
      (value "M01PTH_SMD_3.25X0.85MM_NO_SILK")
      (footprint "eagle-import:1X01_SMD_3.25X0.85MM_NO_SILK")
      (libsource (lib "eagle-import") (part "M01PTH_SMD_3.25X0.85MM_NO_SILK"))
    )
    (comp (ref "CLEAN514")
      (value "M01PTH_SMD_3.25X0.85MM_NO_SILK")
      (footprint "eagle-import:1X01_SMD_3.25X0.85MM_NO_SILK")
      (libsource (lib "eagle-import") (part "M01PTH_SMD_3.25X0.85MM_NO_SILK"))
    )
    (comp (ref "CLEAN515")
      (value "M01PTH_SMD_3.25X0.85MM_NO_SILK")
      (footprint "eagle-import:1X01_SMD_3.25X0.85MM_NO_SILK")
      (libsource (lib "eagle-import") (part "M01PTH_SMD_3.25X0.85MM_NO_SILK"))
    )
    (comp (ref "CLEAN516")
      (value "M01PTH_SMD_3.25X0.85MM_NO_SILK")
      (footprint "eagle-import:1X01_SMD_3.25X0.85MM_NO_SILK")
      (libsource (lib "eagle-import") (part "M01PTH_SMD_3.25X0.85MM_NO_SILK"))
    )
    (comp (ref "CLEAN517")
      (value "M01PTH_SMD_3.25X0.85MM_NO_SILK")
      (footprint "eagle-import:1X01_SMD_3.25X0.85MM_NO_SILK")
      (libsource (lib "eagle-import") (part "M01PTH_SMD_3.25X0.85MM_NO_SILK"))
    )
    (comp (ref "CLEAN518")
      (value "M01PTH_SMD_3.25X0.85MM_NO_SILK")
      (footprint "eagle-import:1X01_SMD_3.25X0.85MM_NO_SILK")
      (libsource (lib "eagle-import") (part "M01PTH_SMD_3.25X0.85MM_NO_SILK"))
    )
    (comp (ref "CLEAN519")
      (value "M01PTH_SMD_3.25X0.85MM_NO_SILK")
      (footprint "eagle-import:1X01_SMD_3.25X0.85MM_NO_SILK")
      (libsource (lib "eagle-import") (part "M01PTH_SMD_3.25X0.85MM_NO_SILK"))
    )
    (comp (ref "CLEAN520")
      (value "M01PTH_SMD_3.25X0.85MM_NO_SILK")
      (footprint "eagle-import:1X01_SMD_3.25X0.85MM_NO_SILK")
      (libsource (lib "eagle-import") (part "M01PTH_SMD_3.25X0.85MM_NO_SILK"))
    )
    (comp (ref "CLEAN521")
      (value "M01PTH_SMD_3.25X0.85MM_NO_SILK")
      (footprint "eagle-import:1X01_SMD_3.25X0.85MM_NO_SILK")
      (libsource (lib "eagle-import") (part "M01PTH_SMD_3.25X0.85MM_NO_SILK"))
    )
    (comp (ref "CLEAN522")
      (value "M01PTH_SMD_3.25X0.85MM_NO_SILK")
      (footprint "eagle-import:1X01_SMD_3.25X0.85MM_NO_SILK")
      (libsource (lib "eagle-import") (part "M01PTH_SMD_3.25X0.85MM_NO_SILK"))
    )
    (comp (ref "CLEAN523")
      (value "M01PTH_SMD_3.25X0.85MM_NO_SILK")
      (footprint "eagle-import:1X01_SMD_3.25X0.85MM_NO_SILK")
      (libsource (lib "eagle-import") (part "M01PTH_SMD_3.25X0.85MM_NO_SILK"))
    )
    (comp (ref "CLEAN524")
      (value "M01PTH_SMD_3.25X0.85MM_NO_SILK")
      (footprint "eagle-import:1X01_SMD_3.25X0.85MM_NO_SILK")
      (libsource (lib "eagle-import") (part "M01PTH_SMD_3.25X0.85MM_NO_SILK"))
    )
    (comp (ref "CLEAN525")
      (value "M01PTH_SMD_3.25X0.85MM_NO_SILK")
      (footprint "eagle-import:1X01_SMD_3.25X0.85MM_NO_SILK")
      (libsource (lib "eagle-import") (part "M01PTH_SMD_3.25X0.85MM_NO_SILK"))
    )
    (comp (ref "CLEAN526")
      (value "M01PTH_SMD_3.25X0.85MM_NO_SILK")
      (footprint "eagle-import:1X01_SMD_3.25X0.85MM_NO_SILK")
      (libsource (lib "eagle-import") (part "M01PTH_SMD_3.25X0.85MM_NO_SILK"))
    )
    (comp (ref "CLEAN527")
      (value "M01PTH_SMD_3.25X0.85MM_NO_SILK")
      (footprint "eagle-import:1X01_SMD_3.25X0.85MM_NO_SILK")
      (libsource (lib "eagle-import") (part "M01PTH_SMD_3.25X0.85MM_NO_SILK"))
    )
    (comp (ref "CLEAN528")
      (value "M01PTH_SMD_3.25X0.85MM_NO_SILK")
      (footprint "eagle-import:1X01_SMD_3.25X0.85MM_NO_SILK")
      (libsource (lib "eagle-import") (part "M01PTH_SMD_3.25X0.85MM_NO_SILK"))
    )
    (comp (ref "CLEAN529")
      (value "M01PTH_SMD_3.25X0.85MM_NO_SILK")
      (footprint "eagle-import:1X01_SMD_3.25X0.85MM_NO_SILK")
      (libsource (lib "eagle-import") (part "M01PTH_SMD_3.25X0.85MM_NO_SILK"))
    )
    (comp (ref "CLEAN530")
      (value "M01PTH_SMD_3.25X0.85MM_NO_SILK")
      (footprint "eagle-import:1X01_SMD_3.25X0.85MM_NO_SILK")
      (libsource (lib "eagle-import") (part "M01PTH_SMD_3.25X0.85MM_NO_SILK"))
    )
    (comp (ref "CLEAN531")
      (value "M01PTH_SMD_3.25X0.85MM_NO_SILK")
      (footprint "eagle-import:1X01_SMD_3.25X0.85MM_NO_SILK")
      (libsource (lib "eagle-import") (part "M01PTH_SMD_3.25X0.85MM_NO_SILK"))
    )
    (comp (ref "CLEAN532")
      (value "M01PTH_SMD_3.25X0.85MM_NO_SILK")
      (footprint "eagle-import:1X01_SMD_3.25X0.85MM_NO_SILK")
      (libsource (lib "eagle-import") (part "M01PTH_SMD_3.25X0.85MM_NO_SILK"))
    )
    (comp (ref "CLEAN533")
      (value "M01PTH_SMD_3.25X0.85MM_NO_SILK")
      (footprint "eagle-import:1X01_SMD_3.25X0.85MM_NO_SILK")
      (libsource (lib "eagle-import") (part "M01PTH_SMD_3.25X0.85MM_NO_SILK"))
    )
    (comp (ref "CLEAN534")
      (value "M01PTH_SMD_3.25X0.85MM_NO_SILK")
      (footprint "eagle-import:1X01_SMD_3.25X0.85MM_NO_SILK")
      (libsource (lib "eagle-import") (part "M01PTH_SMD_3.25X0.85MM_NO_SILK"))
    )
    (comp (ref "CLEAN535")
      (value "M01PTH_SMD_3.25X0.85MM_NO_SILK")
      (footprint "eagle-import:1X01_SMD_3.25X0.85MM_NO_SILK")
      (libsource (lib "eagle-import") (part "M01PTH_SMD_3.25X0.85MM_NO_SILK"))
    )
    (comp (ref "CLEAN536")
      (value "M01PTH_SMD_3.25X0.85MM_NO_SILK")
      (footprint "eagle-import:1X01_SMD_3.25X0.85MM_NO_SILK")
      (libsource (lib "eagle-import") (part "M01PTH_SMD_3.25X0.85MM_NO_SILK"))
    )
    (comp (ref "CLEAN537")
      (value "M01PTH_SMD_3.25X0.85MM_NO_SILK")
      (footprint "eagle-import:1X01_SMD_3.25X0.85MM_NO_SILK")
      (libsource (lib "eagle-import") (part "M01PTH_SMD_3.25X0.85MM_NO_SILK"))
    )
    (comp (ref "CLEAN538")
      (value "M01PTH_SMD_3.25X0.85MM_NO_SILK")
      (footprint "eagle-import:1X01_SMD_3.25X0.85MM_NO_SILK")
      (libsource (lib "eagle-import") (part "M01PTH_SMD_3.25X0.85MM_NO_SILK"))
    )
    (comp (ref "CLEAN539")
      (value "M01PTH_SMD_3.25X0.85MM_NO_SILK")
      (footprint "eagle-import:1X01_SMD_3.25X0.85MM_NO_SILK")
      (libsource (lib "eagle-import") (part "M01PTH_SMD_3.25X0.85MM_NO_SILK"))
    )
    (comp (ref "CLEAN540")
      (value "M01PTH_SMD_3.25X0.85MM_NO_SILK")
      (footprint "eagle-import:1X01_SMD_3.25X0.85MM_NO_SILK")
      (libsource (lib "eagle-import") (part "M01PTH_SMD_3.25X0.85MM_NO_SILK"))
    )
    (comp (ref "CLEAN541")
      (value "M01PTH_SMD_3.25X0.85MM_NO_SILK")
      (footprint "eagle-import:1X01_SMD_3.25X0.85MM_NO_SILK")
      (libsource (lib "eagle-import") (part "M01PTH_SMD_3.25X0.85MM_NO_SILK"))
    )
    (comp (ref "CLEAN542")
      (value "M01PTH_SMD_3.25X0.85MM_NO_SILK")
      (footprint "eagle-import:1X01_SMD_3.25X0.85MM_NO_SILK")
      (libsource (lib "eagle-import") (part "M01PTH_SMD_3.25X0.85MM_NO_SILK"))
    )
    (comp (ref "CLEAN543")
      (value "M01PTH_SMD_3.25X0.85MM_NO_SILK")
      (footprint "eagle-import:1X01_SMD_3.25X0.85MM_NO_SILK")
      (libsource (lib "eagle-import") (part "M01PTH_SMD_3.25X0.85MM_NO_SILK"))
    )
    (comp (ref "CLEAN544")
      (value "M01PTH_SMD_3.25X0.85MM_NO_SILK")
      (footprint "eagle-import:1X01_SMD_3.25X0.85MM_NO_SILK")
      (libsource (lib "eagle-import") (part "M01PTH_SMD_3.25X0.85MM_NO_SILK"))
    )
    (comp (ref "CLEAN545")
      (value "M01PTH_SMD_3.25X0.85MM_NO_SILK")
      (footprint "eagle-import:1X01_SMD_3.25X0.85MM_NO_SILK")
      (libsource (lib "eagle-import") (part "M01PTH_SMD_3.25X0.85MM_NO_SILK"))
    )
    (comp (ref "CLEAN546")
      (value "M01PTH_SMD_3.25X0.85MM_NO_SILK")
      (footprint "eagle-import:1X01_SMD_3.25X0.85MM_NO_SILK")
      (libsource (lib "eagle-import") (part "M01PTH_SMD_3.25X0.85MM_NO_SILK"))
    )
    (comp (ref "CLEAN547")
      (value "M01PTH_SMD_3.25X0.85MM_NO_SILK")
      (footprint "eagle-import:1X01_SMD_3.25X0.85MM_NO_SILK")
      (libsource (lib "eagle-import") (part "M01PTH_SMD_3.25X0.85MM_NO_SILK"))
    )
    (comp (ref "CLEAN548")
      (value "M01PTH_SMD_3.25X0.85MM_NO_SILK")
      (footprint "eagle-import:1X01_SMD_3.25X0.85MM_NO_SILK")
      (libsource (lib "eagle-import") (part "M01PTH_SMD_3.25X0.85MM_NO_SILK"))
    )
    (comp (ref "CLEAN549")
      (value "M01PTH_SMD_3.25X0.85MM_NO_SILK")
      (footprint "eagle-import:1X01_SMD_3.25X0.85MM_NO_SILK")
      (libsource (lib "eagle-import") (part "M01PTH_SMD_3.25X0.85MM_NO_SILK"))
    )
    (comp (ref "CLEAN550")
      (value "M01PTH_SMD_3.25X0.85MM_NO_SILK")
      (footprint "eagle-import:1X01_SMD_3.25X0.85MM_NO_SILK")
      (libsource (lib "eagle-import") (part "M01PTH_SMD_3.25X0.85MM_NO_SILK"))
    )
    (comp (ref "CLEAN551")
      (value "M01PTH_SMD_3.25X0.85MM_NO_SILK")
      (footprint "eagle-import:1X01_SMD_3.25X0.85MM_NO_SILK")
      (libsource (lib "eagle-import") (part "M01PTH_SMD_3.25X0.85MM_NO_SILK"))
    )
    (comp (ref "CLEAN552")
      (value "M01PTH_SMD_3.25X0.85MM_NO_SILK")
      (footprint "eagle-import:1X01_SMD_3.25X0.85MM_NO_SILK")
      (libsource (lib "eagle-import") (part "M01PTH_SMD_3.25X0.85MM_NO_SILK"))
    )
    (comp (ref "CLEAN553")
      (value "M01PTH_SMD_3.25X0.85MM_NO_SILK")
      (footprint "eagle-import:1X01_SMD_3.25X0.85MM_NO_SILK")
      (libsource (lib "eagle-import") (part "M01PTH_SMD_3.25X0.85MM_NO_SILK"))
    )
    (comp (ref "CLEAN554")
      (value "M01PTH_SMD_3.25X0.85MM_NO_SILK")
      (footprint "eagle-import:1X01_SMD_3.25X0.85MM_NO_SILK")
      (libsource (lib "eagle-import") (part "M01PTH_SMD_3.25X0.85MM_NO_SILK"))
    )
    (comp (ref "CLEAN555")
      (value "M01PTH_SMD_3.25X0.85MM_NO_SILK")
      (footprint "eagle-import:1X01_SMD_3.25X0.85MM_NO_SILK")
      (libsource (lib "eagle-import") (part "M01PTH_SMD_3.25X0.85MM_NO_SILK"))
    )
    (comp (ref "CLEAN556")
      (value "M01PTH_SMD_3.25X0.85MM_NO_SILK")
      (footprint "eagle-import:1X01_SMD_3.25X0.85MM_NO_SILK")
      (libsource (lib "eagle-import") (part "M01PTH_SMD_3.25X0.85MM_NO_SILK"))
    )
    (comp (ref "CLEAN557")
      (value "M01PTH_SMD_3.25X0.85MM_NO_SILK")
      (footprint "eagle-import:1X01_SMD_3.25X0.85MM_NO_SILK")
      (libsource (lib "eagle-import") (part "M01PTH_SMD_3.25X0.85MM_NO_SILK"))
    )
    (comp (ref "CLEAN558")
      (value "M01PTH_SMD_3.25X0.85MM_NO_SILK")
      (footprint "eagle-import:1X01_SMD_3.25X0.85MM_NO_SILK")
      (libsource (lib "eagle-import") (part "M01PTH_SMD_3.25X0.85MM_NO_SILK"))
    )
    (comp (ref "CLEAN559")
      (value "M01PTH_SMD_3.25X0.85MM_NO_SILK")
      (footprint "eagle-import:1X01_SMD_3.25X0.85MM_NO_SILK")
      (libsource (lib "eagle-import") (part "M01PTH_SMD_3.25X0.85MM_NO_SILK"))
    )
    (comp (ref "CLEAN560")
      (value "M01PTH_SMD_3.25X0.85MM_NO_SILK")
      (footprint "eagle-import:1X01_SMD_3.25X0.85MM_NO_SILK")
      (libsource (lib "eagle-import") (part "M01PTH_SMD_3.25X0.85MM_NO_SILK"))
    )
    (comp (ref "CLEAN561")
      (value "M01PTH_SMD_3.25X0.85MM_NO_SILK")
      (footprint "eagle-import:1X01_SMD_3.25X0.85MM_NO_SILK")
      (libsource (lib "eagle-import") (part "M01PTH_SMD_3.25X0.85MM_NO_SILK"))
    )
    (comp (ref "CLEAN562")
      (value "M01PTH_SMD_3.25X0.85MM_NO_SILK")
      (footprint "eagle-import:1X01_SMD_3.25X0.85MM_NO_SILK")
      (libsource (lib "eagle-import") (part "M01PTH_SMD_3.25X0.85MM_NO_SILK"))
    )
    (comp (ref "CLEAN563")
      (value "M01PTH_SMD_3.25X0.85MM_NO_SILK")
      (footprint "eagle-import:1X01_SMD_3.25X0.85MM_NO_SILK")
      (libsource (lib "eagle-import") (part "M01PTH_SMD_3.25X0.85MM_NO_SILK"))
    )
    (comp (ref "CLEAN564")
      (value "M01PTH_SMD_3.25X0.85MM_NO_SILK")
      (footprint "eagle-import:1X01_SMD_3.25X0.85MM_NO_SILK")
      (libsource (lib "eagle-import") (part "M01PTH_SMD_3.25X0.85MM_NO_SILK"))
    )
    (comp (ref "CLEAN565")
      (value "M01PTH_SMD_3.25X0.85MM_NO_SILK")
      (footprint "eagle-import:1X01_SMD_3.25X0.85MM_NO_SILK")
      (libsource (lib "eagle-import") (part "M01PTH_SMD_3.25X0.85MM_NO_SILK"))
    )
    (comp (ref "CLEAN566")
      (value "M01PTH_SMD_3.25X0.85MM_NO_SILK")
      (footprint "eagle-import:1X01_SMD_3.25X0.85MM_NO_SILK")
      (libsource (lib "eagle-import") (part "M01PTH_SMD_3.25X0.85MM_NO_SILK"))
    )
    (comp (ref "CLEAN567")
      (value "M01PTH_SMD_3.25X0.85MM_NO_SILK")
      (footprint "eagle-import:1X01_SMD_3.25X0.85MM_NO_SILK")
      (libsource (lib "eagle-import") (part "M01PTH_SMD_3.25X0.85MM_NO_SILK"))
    )
    (comp (ref "CLEAN568")
      (value "M01PTH_SMD_3.25X0.85MM_NO_SILK")
      (footprint "eagle-import:1X01_SMD_3.25X0.85MM_NO_SILK")
      (libsource (lib "eagle-import") (part "M01PTH_SMD_3.25X0.85MM_NO_SILK"))
    )
    (comp (ref "CLEAN569")
      (value "M01PTH_SMD_3.25X0.85MM_NO_SILK")
      (footprint "eagle-import:1X01_SMD_3.25X0.85MM_NO_SILK")
      (libsource (lib "eagle-import") (part "M01PTH_SMD_3.25X0.85MM_NO_SILK"))
    )
    (comp (ref "CLEAN570")
      (value "M01PTH_SMD_3.25X0.85MM_NO_SILK")
      (footprint "eagle-import:1X01_SMD_3.25X0.85MM_NO_SILK")
      (libsource (lib "eagle-import") (part "M01PTH_SMD_3.25X0.85MM_NO_SILK"))
    )
    (comp (ref "CLEAN571")
      (value "M01PTH_SMD_3.25X0.85MM_NO_SILK")
      (footprint "eagle-import:1X01_SMD_3.25X0.85MM_NO_SILK")
      (libsource (lib "eagle-import") (part "M01PTH_SMD_3.25X0.85MM_NO_SILK"))
    )
    (comp (ref "CLEAN572")
      (value "M01PTH_SMD_3.25X0.85MM_NO_SILK")
      (footprint "eagle-import:1X01_SMD_3.25X0.85MM_NO_SILK")
      (libsource (lib "eagle-import") (part "M01PTH_SMD_3.25X0.85MM_NO_SILK"))
    )
    (comp (ref "CLEAN573")
      (value "M01PTH_SMD_3.25X0.85MM_NO_SILK")
      (footprint "eagle-import:1X01_SMD_3.25X0.85MM_NO_SILK")
      (libsource (lib "eagle-import") (part "M01PTH_SMD_3.25X0.85MM_NO_SILK"))
    )
    (comp (ref "CLEAN574")
      (value "M01PTH_SMD_3.25X0.85MM_NO_SILK")
      (footprint "eagle-import:1X01_SMD_3.25X0.85MM_NO_SILK")
      (libsource (lib "eagle-import") (part "M01PTH_SMD_3.25X0.85MM_NO_SILK"))
    )
    (comp (ref "CLEAN575")
      (value "M01PTH_SMD_3.25X0.85MM_NO_SILK")
      (footprint "eagle-import:1X01_SMD_3.25X0.85MM_NO_SILK")
      (libsource (lib "eagle-import") (part "M01PTH_SMD_3.25X0.85MM_NO_SILK"))
    )
    (comp (ref "CLEAN576")
      (value "M01PTH_SMD_3.25X0.85MM_NO_SILK")
      (footprint "eagle-import:1X01_SMD_3.25X0.85MM_NO_SILK")
      (libsource (lib "eagle-import") (part "M01PTH_SMD_3.25X0.85MM_NO_SILK"))
    )
    (comp (ref "CLEAN577")
      (value "M01PTH_SMD_3.25X0.85MM_NO_SILK")
      (footprint "eagle-import:1X01_SMD_3.25X0.85MM_NO_SILK")
      (libsource (lib "eagle-import") (part "M01PTH_SMD_3.25X0.85MM_NO_SILK"))
    )
    (comp (ref "CLEAN578")
      (value "M01PTH_SMD_3.25X0.85MM_NO_SILK")
      (footprint "eagle-import:1X01_SMD_3.25X0.85MM_NO_SILK")
      (libsource (lib "eagle-import") (part "M01PTH_SMD_3.25X0.85MM_NO_SILK"))
    )
    (comp (ref "CLEAN579")
      (value "M01PTH_SMD_3.25X0.85MM_NO_SILK")
      (footprint "eagle-import:1X01_SMD_3.25X0.85MM_NO_SILK")
      (libsource (lib "eagle-import") (part "M01PTH_SMD_3.25X0.85MM_NO_SILK"))
    )
    (comp (ref "CLEAN580")
      (value "M01PTH_SMD_3.25X0.85MM_NO_SILK")
      (footprint "eagle-import:1X01_SMD_3.25X0.85MM_NO_SILK")
      (libsource (lib "eagle-import") (part "M01PTH_SMD_3.25X0.85MM_NO_SILK"))
    )
    (comp (ref "CLEAN581")
      (value "M01PTH_SMD_3.25X0.85MM_NO_SILK")
      (footprint "eagle-import:1X01_SMD_3.25X0.85MM_NO_SILK")
      (libsource (lib "eagle-import") (part "M01PTH_SMD_3.25X0.85MM_NO_SILK"))
    )
    (comp (ref "CLEAN582")
      (value "M01PTH_SMD_3.25X0.85MM_NO_SILK")
      (footprint "eagle-import:1X01_SMD_3.25X0.85MM_NO_SILK")
      (libsource (lib "eagle-import") (part "M01PTH_SMD_3.25X0.85MM_NO_SILK"))
    )
    (comp (ref "CLEAN583")
      (value "M01PTH_SMD_3.25X0.85MM_NO_SILK")
      (footprint "eagle-import:1X01_SMD_3.25X0.85MM_NO_SILK")
      (libsource (lib "eagle-import") (part "M01PTH_SMD_3.25X0.85MM_NO_SILK"))
    )
    (comp (ref "CLEAN584")
      (value "M01PTH_SMD_3.25X0.85MM_NO_SILK")
      (footprint "eagle-import:1X01_SMD_3.25X0.85MM_NO_SILK")
      (libsource (lib "eagle-import") (part "M01PTH_SMD_3.25X0.85MM_NO_SILK"))
    )
    (comp (ref "CLEAN585")
      (value "M01PTH_SMD_3.25X0.85MM_NO_SILK")
      (footprint "eagle-import:1X01_SMD_3.25X0.85MM_NO_SILK")
      (libsource (lib "eagle-import") (part "M01PTH_SMD_3.25X0.85MM_NO_SILK"))
    )
    (comp (ref "CLEAN586")
      (value "M01PTH_SMD_3.25X0.85MM_NO_SILK")
      (footprint "eagle-import:1X01_SMD_3.25X0.85MM_NO_SILK")
      (libsource (lib "eagle-import") (part "M01PTH_SMD_3.25X0.85MM_NO_SILK"))
    )
    (comp (ref "CLEAN587")
      (value "M01PTH_SMD_3.25X0.85MM_NO_SILK")
      (footprint "eagle-import:1X01_SMD_3.25X0.85MM_NO_SILK")
      (libsource (lib "eagle-import") (part "M01PTH_SMD_3.25X0.85MM_NO_SILK"))
    )
    (comp (ref "CLEAN588")
      (value "M01PTH_SMD_3.25X0.85MM_NO_SILK")
      (footprint "eagle-import:1X01_SMD_3.25X0.85MM_NO_SILK")
      (libsource (lib "eagle-import") (part "M01PTH_SMD_3.25X0.85MM_NO_SILK"))
    )
    (comp (ref "CLEAN589")
      (value "M01PTH_SMD_3.25X0.85MM_NO_SILK")
      (footprint "eagle-import:1X01_SMD_3.25X0.85MM_NO_SILK")
      (libsource (lib "eagle-import") (part "M01PTH_SMD_3.25X0.85MM_NO_SILK"))
    )
    (comp (ref "CLEAN590")
      (value "M01PTH_SMD_3.25X0.85MM_NO_SILK")
      (footprint "eagle-import:1X01_SMD_3.25X0.85MM_NO_SILK")
      (libsource (lib "eagle-import") (part "M01PTH_SMD_3.25X0.85MM_NO_SILK"))
    )
    (comp (ref "CLEAN591")
      (value "M01PTH_SMD_3.25X0.85MM_NO_SILK")
      (footprint "eagle-import:1X01_SMD_3.25X0.85MM_NO_SILK")
      (libsource (lib "eagle-import") (part "M01PTH_SMD_3.25X0.85MM_NO_SILK"))
    )
    (comp (ref "CLEAN592")
      (value "M01PTH_SMD_3.25X0.85MM_NO_SILK")
      (footprint "eagle-import:1X01_SMD_3.25X0.85MM_NO_SILK")
      (libsource (lib "eagle-import") (part "M01PTH_SMD_3.25X0.85MM_NO_SILK"))
    )
    (comp (ref "CLEAN593")
      (value "M01PTH_SMD_3.25X0.85MM_NO_SILK")
      (footprint "eagle-import:1X01_SMD_3.25X0.85MM_NO_SILK")
      (libsource (lib "eagle-import") (part "M01PTH_SMD_3.25X0.85MM_NO_SILK"))
    )
    (comp (ref "CLEAN594")
      (value "M01PTH_SMD_3.25X0.85MM_NO_SILK")
      (footprint "eagle-import:1X01_SMD_3.25X0.85MM_NO_SILK")
      (libsource (lib "eagle-import") (part "M01PTH_SMD_3.25X0.85MM_NO_SILK"))
    )
    (comp (ref "CLEAN595")
      (value "M01PTH_SMD_3.25X0.85MM_NO_SILK")
      (footprint "eagle-import:1X01_SMD_3.25X0.85MM_NO_SILK")
      (libsource (lib "eagle-import") (part "M01PTH_SMD_3.25X0.85MM_NO_SILK"))
    )
    (comp (ref "CLEAN596")
      (value "M01PTH_SMD_3.25X0.85MM_NO_SILK")
      (footprint "eagle-import:1X01_SMD_3.25X0.85MM_NO_SILK")
      (libsource (lib "eagle-import") (part "M01PTH_SMD_3.25X0.85MM_NO_SILK"))
    )
    (comp (ref "CLEAN597")
      (value "M01PTH_SMD_3.25X0.85MM_NO_SILK")
      (footprint "eagle-import:1X01_SMD_3.25X0.85MM_NO_SILK")
      (libsource (lib "eagle-import") (part "M01PTH_SMD_3.25X0.85MM_NO_SILK"))
    )
    (comp (ref "CLEAN598")
      (value "M01PTH_SMD_3.25X0.85MM_NO_SILK")
      (footprint "eagle-import:1X01_SMD_3.25X0.85MM_NO_SILK")
      (libsource (lib "eagle-import") (part "M01PTH_SMD_3.25X0.85MM_NO_SILK"))
    )
    (comp (ref "CLEAN599")
      (value "M01PTH_SMD_3.25X0.85MM_NO_SILK")
      (footprint "eagle-import:1X01_SMD_3.25X0.85MM_NO_SILK")
      (libsource (lib "eagle-import") (part "M01PTH_SMD_3.25X0.85MM_NO_SILK"))
    )
  )
  (nets
    (net (code "1") (name "/NEW_0") (class "Default")
      (node (ref "CLEAN360") (pin "P$3") (pinfunction "1_P$3") (pintype "passive"))
      (node (ref "CLEAN6") (pin "1") (pinfunction "1_1") (pintype "passive"))
    )
    (net (code "2") (name "/NEW_1") (class "Default")
      (node (ref "CLEAN361") (pin "P$3") (pinfunction "1_P$3") (pintype "passive"))
      (node (ref "CLEAN7") (pin "1") (pinfunction "1_1") (pintype "passive"))
    )
    (net (code "3") (name "/NEW_2") (class "Default")
      (node (ref "CLEAN16") (pin "1") (pinfunction "1_1") (pintype "passive"))
      (node (ref "CLEAN362") (pin "P$3") (pinfunction "1_P$3") (pintype "passive"))
    )
    (net (code "4") (name "/NEW_3") (class "Default")
      (node (ref "CLEAN17") (pin "1") (pinfunction "1_1") (pintype "passive"))
      (node (ref "CLEAN363") (pin "P$3") (pinfunction "1_P$3") (pintype "passive"))
    )
    (net (code "5") (name "/NEW_4") (class "Default")
      (node (ref "CLEAN26") (pin "1") (pinfunction "1_1") (pintype "passive"))
      (node (ref "CLEAN364") (pin "P$3") (pinfunction "1_P$3") (pintype "passive"))
    )
    (net (code "6") (name "/NEW_5") (class "Default")
      (node (ref "CLEAN27") (pin "1") (pinfunction "1_1") (pintype "passive"))
      (node (ref "CLEAN365") (pin "P$3") (pinfunction "1_P$3") (pintype "passive"))
    )
    (net (code "7") (name "/NEW_6") (class "Default")
      (node (ref "CLEAN36") (pin "1") (pinfunction "1_1") (pintype "passive"))
      (node (ref "CLEAN366") (pin "P$3") (pinfunction "1_P$3") (pintype "passive"))
    )
    (net (code "8") (name "/NEW_7") (class "Default")
      (node (ref "CLEAN367") (pin "P$3") (pinfunction "1_P$3") (pintype "passive"))
      (node (ref "CLEAN37") (pin "1") (pinfunction "1_1") (pintype "passive"))
    )
    (net (code "9") (name "/NEW_8") (class "Default")
      (node (ref "CLEAN368") (pin "P$3") (pinfunction "1_P$3") (pintype "passive"))
      (node (ref "CLEAN46") (pin "1") (pinfunction "1_1") (pintype "passive"))
    )
    (net (code "10") (name "/NEW_9") (class "Default")
      (node (ref "CLEAN369") (pin "P$3") (pinfunction "1_P$3") (pintype "passive"))
      (node (ref "CLEAN47") (pin "1") (pinfunction "1_1") (pintype "passive"))
    )
    (net (code "11") (name "/NEW_10") (class "Default")
      (node (ref "CLEAN370") (pin "P$3") (pinfunction "1_P$3") (pintype "passive"))
      (node (ref "CLEAN56") (pin "1") (pinfunction "1_1") (pintype "passive"))
    )
    (net (code "12") (name "/NEW_11") (class "Default")
      (node (ref "CLEAN371") (pin "P$3") (pinfunction "1_P$3") (pintype "passive"))
      (node (ref "CLEAN57") (pin "1") (pinfunction "1_1") (pintype "passive"))
    )
    (net (code "13") (name "/NEW_12") (class "Default")
      (node (ref "CLEAN372") (pin "P$3") (pinfunction "1_P$3") (pintype "passive"))
      (node (ref "CLEAN66") (pin "1") (pinfunction "1_1") (pintype "passive"))
    )
    (net (code "14") (name "/NEW_13") (class "Default")
      (node (ref "CLEAN373") (pin "P$3") (pinfunction "1_P$3") (pintype "passive"))
      (node (ref "CLEAN67") (pin "1") (pinfunction "1_1") (pintype "passive"))
    )
    (net (code "15") (name "/NEW_14") (class "Default")
      (node (ref "CLEAN374") (pin "P$3") (pinfunction "1_P$3") (pintype "passive"))
      (node (ref "CLEAN76") (pin "1") (pinfunction "1_1") (pintype "passive"))
    )
    (net (code "16") (name "/NEW_15") (class "Default")
      (node (ref "CLEAN375") (pin "P$3") (pinfunction "1_P$3") (pintype "passive"))
      (node (ref "CLEAN77") (pin "1") (pinfunction "1_1") (pintype "passive"))
    )
    (net (code "17") (name "/NEW_16") (class "Default")
      (node (ref "CLEAN376") (pin "P$3") (pinfunction "1_P$3") (pintype "passive"))
      (node (ref "CLEAN86") (pin "1") (pinfunction "1_1") (pintype "passive"))
    )
    (net (code "18") (name "/NEW_17") (class "Default")
      (node (ref "CLEAN377") (pin "P$3") (pinfunction "1_P$3") (pintype "passive"))
      (node (ref "CLEAN87") (pin "1") (pinfunction "1_1") (pintype "passive"))
    )
    (net (code "19") (name "/NEW_18") (class "Default")
      (node (ref "CLEAN378") (pin "P$3") (pinfunction "1_P$3") (pintype "passive"))
      (node (ref "CLEAN96") (pin "1") (pinfunction "1_1") (pintype "passive"))
    )
    (net (code "20") (name "/NEW_19") (class "Default")
      (node (ref "CLEAN379") (pin "P$3") (pinfunction "1_P$3") (pintype "passive"))
      (node (ref "CLEAN97") (pin "1") (pinfunction "1_1") (pintype "passive"))
    )
    (net (code "21") (name "/NEW_20") (class "Default")
      (node (ref "CLEAN106") (pin "1") (pinfunction "1_1") (pintype "passive"))
      (node (ref "CLEAN380") (pin "P$3") (pinfunction "1_P$3") (pintype "passive"))
    )
    (net (code "22") (name "/NEW_21") (class "Default")
      (node (ref "CLEAN107") (pin "1") (pinfunction "1_1") (pintype "passive"))
      (node (ref "CLEAN381") (pin "P$3") (pinfunction "1_P$3") (pintype "passive"))
    )
    (net (code "23") (name "/NEW_22") (class "Default")
      (node (ref "CLEAN116") (pin "1") (pinfunction "1_1") (pintype "passive"))
      (node (ref "CLEAN382") (pin "P$3") (pinfunction "1_P$3") (pintype "passive"))
    )
    (net (code "24") (name "/NEW_23") (class "Default")
      (node (ref "CLEAN117") (pin "1") (pinfunction "1_1") (pintype "passive"))
      (node (ref "CLEAN383") (pin "P$3") (pinfunction "1_P$3") (pintype "passive"))
    )
    (net (code "25") (name "/NEW_24") (class "Default")
      (node (ref "CLEAN126") (pin "1") (pinfunction "1_1") (pintype "passive"))
      (node (ref "CLEAN384") (pin "P$3") (pinfunction "1_P$3") (pintype "passive"))
    )
    (net (code "26") (name "/NEW_25") (class "Default")
      (node (ref "CLEAN127") (pin "1") (pinfunction "1_1") (pintype "passive"))
      (node (ref "CLEAN385") (pin "P$3") (pinfunction "1_P$3") (pintype "passive"))
    )
    (net (code "27") (name "/NEW_26") (class "Default")
      (node (ref "CLEAN136") (pin "1") (pinfunction "1_1") (pintype "passive"))
      (node (ref "CLEAN386") (pin "P$3") (pinfunction "1_P$3") (pintype "passive"))
    )
    (net (code "28") (name "/NEW_27") (class "Default")
      (node (ref "CLEAN137") (pin "1") (pinfunction "1_1") (pintype "passive"))
      (node (ref "CLEAN387") (pin "P$3") (pinfunction "1_P$3") (pintype "passive"))
    )
    (net (code "29") (name "/NEW_28") (class "Default")
      (node (ref "CLEAN146") (pin "1") (pinfunction "1_1") (pintype "passive"))
      (node (ref "CLEAN388") (pin "P$3") (pinfunction "1_P$3") (pintype "passive"))
    )
    (net (code "30") (name "/NEW_29") (class "Default")
      (node (ref "CLEAN147") (pin "1") (pinfunction "1_1") (pintype "passive"))
      (node (ref "CLEAN389") (pin "P$3") (pinfunction "1_P$3") (pintype "passive"))
    )
    (net (code "31") (name "/NEW_30") (class "Default")
      (node (ref "CLEAN156") (pin "1") (pinfunction "1_1") (pintype "passive"))
      (node (ref "CLEAN390") (pin "P$3") (pinfunction "1_P$3") (pintype "passive"))
    )
    (net (code "32") (name "/NEW_31") (class "Default")
      (node (ref "CLEAN157") (pin "1") (pinfunction "1_1") (pintype "passive"))
      (node (ref "CLEAN391") (pin "P$3") (pinfunction "1_P$3") (pintype "passive"))
    )
    (net (code "33") (name "/NEW_32") (class "Default")
      (node (ref "CLEAN166") (pin "1") (pinfunction "1_1") (pintype "passive"))
      (node (ref "CLEAN392") (pin "P$3") (pinfunction "1_P$3") (pintype "passive"))
    )
    (net (code "34") (name "/NEW_33") (class "Default")
      (node (ref "CLEAN167") (pin "1") (pinfunction "1_1") (pintype "passive"))
      (node (ref "CLEAN393") (pin "P$3") (pinfunction "1_P$3") (pintype "passive"))
    )
    (net (code "35") (name "/NEW_34") (class "Default")
      (node (ref "CLEAN176") (pin "1") (pinfunction "1_1") (pintype "passive"))
      (node (ref "CLEAN394") (pin "P$3") (pinfunction "1_P$3") (pintype "passive"))
    )
    (net (code "36") (name "/NEW_35") (class "Default")
      (node (ref "CLEAN177") (pin "1") (pinfunction "1_1") (pintype "passive"))
      (node (ref "CLEAN395") (pin "P$3") (pinfunction "1_P$3") (pintype "passive"))
    )
    (net (code "37") (name "/NEW_36") (class "Default")
      (node (ref "CLEAN186") (pin "1") (pinfunction "1_1") (pintype "passive"))
      (node (ref "CLEAN396") (pin "P$3") (pinfunction "1_P$3") (pintype "passive"))
    )
    (net (code "38") (name "/NEW_37") (class "Default")
      (node (ref "CLEAN187") (pin "1") (pinfunction "1_1") (pintype "passive"))
      (node (ref "CLEAN397") (pin "P$3") (pinfunction "1_P$3") (pintype "passive"))
    )
    (net (code "39") (name "/NEW_38") (class "Default")
      (node (ref "CLEAN196") (pin "1") (pinfunction "1_1") (pintype "passive"))
      (node (ref "CLEAN398") (pin "P$3") (pinfunction "1_P$3") (pintype "passive"))
    )
    (net (code "40") (name "/NEW_39") (class "Default")
      (node (ref "CLEAN197") (pin "1") (pinfunction "1_1") (pintype "passive"))
      (node (ref "CLEAN399") (pin "P$3") (pinfunction "1_P$3") (pintype "passive"))
    )
    (net (code "41") (name "/NEW_40") (class "Default")
      (node (ref "CLEAN206") (pin "1") (pinfunction "1_1") (pintype "passive"))
      (node (ref "CLEAN400") (pin "P$3") (pinfunction "1_P$3") (pintype "passive"))
    )
    (net (code "42") (name "/NEW_41") (class "Default")
      (node (ref "CLEAN207") (pin "1") (pinfunction "1_1") (pintype "passive"))
      (node (ref "CLEAN401") (pin "P$3") (pinfunction "1_P$3") (pintype "passive"))
    )
    (net (code "43") (name "/NEW_42") (class "Default")
      (node (ref "CLEAN216") (pin "1") (pinfunction "1_1") (pintype "passive"))
      (node (ref "CLEAN402") (pin "P$3") (pinfunction "1_P$3") (pintype "passive"))
    )
    (net (code "44") (name "/NEW_43") (class "Default")
      (node (ref "CLEAN217") (pin "1") (pinfunction "1_1") (pintype "passive"))
      (node (ref "CLEAN403") (pin "P$3") (pinfunction "1_P$3") (pintype "passive"))
    )
    (net (code "45") (name "/NEW_44") (class "Default")
      (node (ref "CLEAN226") (pin "1") (pinfunction "1_1") (pintype "passive"))
      (node (ref "CLEAN404") (pin "P$3") (pinfunction "1_P$3") (pintype "passive"))
    )
    (net (code "46") (name "/NEW_45") (class "Default")
      (node (ref "CLEAN227") (pin "1") (pinfunction "1_1") (pintype "passive"))
      (node (ref "CLEAN405") (pin "P$3") (pinfunction "1_P$3") (pintype "passive"))
    )
    (net (code "47") (name "/NEW_46") (class "Default")
      (node (ref "CLEAN236") (pin "1") (pinfunction "1_1") (pintype "passive"))
      (node (ref "CLEAN406") (pin "P$3") (pinfunction "1_P$3") (pintype "passive"))
    )
    (net (code "48") (name "/NEW_47") (class "Default")
      (node (ref "CLEAN237") (pin "1") (pinfunction "1_1") (pintype "passive"))
      (node (ref "CLEAN407") (pin "P$3") (pinfunction "1_P$3") (pintype "passive"))
    )
    (net (code "49") (name "/NEW_48") (class "Default")
      (node (ref "CLEAN246") (pin "1") (pinfunction "1_1") (pintype "passive"))
      (node (ref "CLEAN408") (pin "P$3") (pinfunction "1_P$3") (pintype "passive"))
    )
    (net (code "50") (name "/NEW_49") (class "Default")
      (node (ref "CLEAN247") (pin "1") (pinfunction "1_1") (pintype "passive"))
      (node (ref "CLEAN409") (pin "P$3") (pinfunction "1_P$3") (pintype "passive"))
    )
    (net (code "51") (name "/NEW_50") (class "Default")
      (node (ref "CLEAN256") (pin "1") (pinfunction "1_1") (pintype "passive"))
      (node (ref "CLEAN410") (pin "P$3") (pinfunction "1_P$3") (pintype "passive"))
    )
    (net (code "52") (name "/NEW_51") (class "Default")
      (node (ref "CLEAN257") (pin "1") (pinfunction "1_1") (pintype "passive"))
      (node (ref "CLEAN411") (pin "P$3") (pinfunction "1_P$3") (pintype "passive"))
    )
    (net (code "53") (name "/NEW_52") (class "Default")
      (node (ref "CLEAN266") (pin "1") (pinfunction "1_1") (pintype "passive"))
      (node (ref "CLEAN412") (pin "P$3") (pinfunction "1_P$3") (pintype "passive"))
    )
    (net (code "54") (name "/NEW_53") (class "Default")
      (node (ref "CLEAN267") (pin "1") (pinfunction "1_1") (pintype "passive"))
      (node (ref "CLEAN413") (pin "P$3") (pinfunction "1_P$3") (pintype "passive"))
    )
    (net (code "55") (name "/NEW_54") (class "Default")
      (node (ref "CLEAN276") (pin "1") (pinfunction "1_1") (pintype "passive"))
      (node (ref "CLEAN414") (pin "P$3") (pinfunction "1_P$3") (pintype "passive"))
    )
    (net (code "56") (name "/NEW_55") (class "Default")
      (node (ref "CLEAN277") (pin "1") (pinfunction "1_1") (pintype "passive"))
      (node (ref "CLEAN415") (pin "P$3") (pinfunction "1_P$3") (pintype "passive"))
    )
    (net (code "57") (name "/NEW_56") (class "Default")
      (node (ref "CLEAN286") (pin "1") (pinfunction "1_1") (pintype "passive"))
      (node (ref "CLEAN416") (pin "P$3") (pinfunction "1_P$3") (pintype "passive"))
    )
    (net (code "58") (name "/NEW_57") (class "Default")
      (node (ref "CLEAN287") (pin "1") (pinfunction "1_1") (pintype "passive"))
      (node (ref "CLEAN417") (pin "P$3") (pinfunction "1_P$3") (pintype "passive"))
    )
    (net (code "59") (name "/NEW_58") (class "Default")
      (node (ref "CLEAN296") (pin "1") (pinfunction "1_1") (pintype "passive"))
      (node (ref "CLEAN418") (pin "P$3") (pinfunction "1_P$3") (pintype "passive"))
    )
    (net (code "60") (name "/NEW_59") (class "Default")
      (node (ref "CLEAN297") (pin "1") (pinfunction "1_1") (pintype "passive"))
      (node (ref "CLEAN419") (pin "P$3") (pinfunction "1_P$3") (pintype "passive"))
    )
    (net (code "61") (name "/NEW_60") (class "Default")
      (node (ref "CLEAN420") (pin "P$3") (pinfunction "1_P$3") (pintype "passive"))
      (node (ref "CLEAN8") (pin "1") (pinfunction "1_1") (pintype "passive"))
    )
    (net (code "62") (name "/NEW_61") (class "Default")
      (node (ref "CLEAN421") (pin "P$3") (pinfunction "1_P$3") (pintype "passive"))
      (node (ref "CLEAN9") (pin "1") (pinfunction "1_1") (pintype "passive"))
    )
    (net (code "63") (name "/NEW_62") (class "Default")
      (node (ref "CLEAN18") (pin "1") (pinfunction "1_1") (pintype "passive"))
      (node (ref "CLEAN422") (pin "P$3") (pinfunction "1_P$3") (pintype "passive"))
    )
    (net (code "64") (name "/NEW_63") (class "Default")
      (node (ref "CLEAN19") (pin "1") (pinfunction "1_1") (pintype "passive"))
      (node (ref "CLEAN423") (pin "P$3") (pinfunction "1_P$3") (pintype "passive"))
    )
    (net (code "65") (name "/NEW_64") (class "Default")
      (node (ref "CLEAN28") (pin "1") (pinfunction "1_1") (pintype "passive"))
      (node (ref "CLEAN424") (pin "P$3") (pinfunction "1_P$3") (pintype "passive"))
    )
    (net (code "66") (name "/NEW_65") (class "Default")
      (node (ref "CLEAN29") (pin "1") (pinfunction "1_1") (pintype "passive"))
      (node (ref "CLEAN425") (pin "P$3") (pinfunction "1_P$3") (pintype "passive"))
    )
    (net (code "67") (name "/NEW_66") (class "Default")
      (node (ref "CLEAN38") (pin "1") (pinfunction "1_1") (pintype "passive"))
      (node (ref "CLEAN426") (pin "P$3") (pinfunction "1_P$3") (pintype "passive"))
    )
    (net (code "68") (name "/NEW_67") (class "Default")
      (node (ref "CLEAN39") (pin "1") (pinfunction "1_1") (pintype "passive"))
      (node (ref "CLEAN427") (pin "P$3") (pinfunction "1_P$3") (pintype "passive"))
    )
    (net (code "69") (name "/NEW_68") (class "Default")
      (node (ref "CLEAN428") (pin "P$3") (pinfunction "1_P$3") (pintype "passive"))
      (node (ref "CLEAN48") (pin "1") (pinfunction "1_1") (pintype "passive"))
    )
    (net (code "70") (name "/NEW_69") (class "Default")
      (node (ref "CLEAN429") (pin "P$3") (pinfunction "1_P$3") (pintype "passive"))
      (node (ref "CLEAN49") (pin "1") (pinfunction "1_1") (pintype "passive"))
    )
    (net (code "71") (name "/NEW_70") (class "Default")
      (node (ref "CLEAN430") (pin "P$3") (pinfunction "1_P$3") (pintype "passive"))
      (node (ref "CLEAN58") (pin "1") (pinfunction "1_1") (pintype "passive"))
    )
    (net (code "72") (name "/NEW_71") (class "Default")
      (node (ref "CLEAN431") (pin "P$3") (pinfunction "1_P$3") (pintype "passive"))
      (node (ref "CLEAN59") (pin "1") (pinfunction "1_1") (pintype "passive"))
    )
    (net (code "73") (name "/NEW_72") (class "Default")
      (node (ref "CLEAN432") (pin "P$3") (pinfunction "1_P$3") (pintype "passive"))
      (node (ref "CLEAN68") (pin "1") (pinfunction "1_1") (pintype "passive"))
    )
    (net (code "74") (name "/NEW_73") (class "Default")
      (node (ref "CLEAN433") (pin "P$3") (pinfunction "1_P$3") (pintype "passive"))
      (node (ref "CLEAN69") (pin "1") (pinfunction "1_1") (pintype "passive"))
    )
    (net (code "75") (name "/NEW_74") (class "Default")
      (node (ref "CLEAN434") (pin "P$3") (pinfunction "1_P$3") (pintype "passive"))
      (node (ref "CLEAN78") (pin "1") (pinfunction "1_1") (pintype "passive"))
    )
    (net (code "76") (name "/NEW_75") (class "Default")
      (node (ref "CLEAN435") (pin "P$3") (pinfunction "1_P$3") (pintype "passive"))
      (node (ref "CLEAN79") (pin "1") (pinfunction "1_1") (pintype "passive"))
    )
    (net (code "77") (name "/NEW_76") (class "Default")
      (node (ref "CLEAN436") (pin "P$3") (pinfunction "1_P$3") (pintype "passive"))
      (node (ref "CLEAN88") (pin "1") (pinfunction "1_1") (pintype "passive"))
    )
    (net (code "78") (name "/NEW_77") (class "Default")
      (node (ref "CLEAN437") (pin "P$3") (pinfunction "1_P$3") (pintype "passive"))
      (node (ref "CLEAN89") (pin "1") (pinfunction "1_1") (pintype "passive"))
    )
    (net (code "79") (name "/NEW_78") (class "Default")
      (node (ref "CLEAN438") (pin "P$3") (pinfunction "1_P$3") (pintype "passive"))
      (node (ref "CLEAN98") (pin "1") (pinfunction "1_1") (pintype "passive"))
    )
    (net (code "80") (name "/NEW_79") (class "Default")
      (node (ref "CLEAN439") (pin "P$3") (pinfunction "1_P$3") (pintype "passive"))
      (node (ref "CLEAN99") (pin "1") (pinfunction "1_1") (pintype "passive"))
    )
    (net (code "81") (name "/NEW_80") (class "Default")
      (node (ref "CLEAN108") (pin "1") (pinfunction "1_1") (pintype "passive"))
      (node (ref "CLEAN440") (pin "P$3") (pinfunction "1_P$3") (pintype "passive"))
    )
    (net (code "82") (name "/NEW_81") (class "Default")
      (node (ref "CLEAN109") (pin "1") (pinfunction "1_1") (pintype "passive"))
      (node (ref "CLEAN441") (pin "P$3") (pinfunction "1_P$3") (pintype "passive"))
    )
    (net (code "83") (name "/NEW_82") (class "Default")
      (node (ref "CLEAN118") (pin "1") (pinfunction "1_1") (pintype "passive"))
      (node (ref "CLEAN442") (pin "P$3") (pinfunction "1_P$3") (pintype "passive"))
    )
    (net (code "84") (name "/NEW_83") (class "Default")
      (node (ref "CLEAN119") (pin "1") (pinfunction "1_1") (pintype "passive"))
      (node (ref "CLEAN443") (pin "P$3") (pinfunction "1_P$3") (pintype "passive"))
    )
    (net (code "85") (name "/NEW_84") (class "Default")
      (node (ref "CLEAN128") (pin "1") (pinfunction "1_1") (pintype "passive"))
      (node (ref "CLEAN444") (pin "P$3") (pinfunction "1_P$3") (pintype "passive"))
    )
    (net (code "86") (name "/NEW_85") (class "Default")
      (node (ref "CLEAN129") (pin "1") (pinfunction "1_1") (pintype "passive"))
      (node (ref "CLEAN445") (pin "P$3") (pinfunction "1_P$3") (pintype "passive"))
    )
    (net (code "87") (name "/NEW_86") (class "Default")
      (node (ref "CLEAN138") (pin "1") (pinfunction "1_1") (pintype "passive"))
      (node (ref "CLEAN446") (pin "P$3") (pinfunction "1_P$3") (pintype "passive"))
    )
    (net (code "88") (name "/NEW_87") (class "Default")
      (node (ref "CLEAN139") (pin "1") (pinfunction "1_1") (pintype "passive"))
      (node (ref "CLEAN447") (pin "P$3") (pinfunction "1_P$3") (pintype "passive"))
    )
    (net (code "89") (name "/NEW_88") (class "Default")
      (node (ref "CLEAN148") (pin "1") (pinfunction "1_1") (pintype "passive"))
      (node (ref "CLEAN448") (pin "P$3") (pinfunction "1_P$3") (pintype "passive"))
    )
    (net (code "90") (name "/NEW_89") (class "Default")
      (node (ref "CLEAN149") (pin "1") (pinfunction "1_1") (pintype "passive"))
      (node (ref "CLEAN449") (pin "P$3") (pinfunction "1_P$3") (pintype "passive"))
    )
    (net (code "91") (name "/NEW_90") (class "Default")
      (node (ref "CLEAN158") (pin "1") (pinfunction "1_1") (pintype "passive"))
      (node (ref "CLEAN450") (pin "P$3") (pinfunction "1_P$3") (pintype "passive"))
    )
    (net (code "92") (name "/NEW_91") (class "Default")
      (node (ref "CLEAN159") (pin "1") (pinfunction "1_1") (pintype "passive"))
      (node (ref "CLEAN451") (pin "P$3") (pinfunction "1_P$3") (pintype "passive"))
    )
    (net (code "93") (name "/NEW_92") (class "Default")
      (node (ref "CLEAN168") (pin "1") (pinfunction "1_1") (pintype "passive"))
      (node (ref "CLEAN452") (pin "P$3") (pinfunction "1_P$3") (pintype "passive"))
    )
    (net (code "94") (name "/NEW_93") (class "Default")
      (node (ref "CLEAN169") (pin "1") (pinfunction "1_1") (pintype "passive"))
      (node (ref "CLEAN453") (pin "P$3") (pinfunction "1_P$3") (pintype "passive"))
    )
    (net (code "95") (name "/NEW_94") (class "Default")
      (node (ref "CLEAN178") (pin "1") (pinfunction "1_1") (pintype "passive"))
      (node (ref "CLEAN454") (pin "P$3") (pinfunction "1_P$3") (pintype "passive"))
    )
    (net (code "96") (name "/NEW_95") (class "Default")
      (node (ref "CLEAN179") (pin "1") (pinfunction "1_1") (pintype "passive"))
      (node (ref "CLEAN455") (pin "P$3") (pinfunction "1_P$3") (pintype "passive"))
    )
    (net (code "97") (name "/NEW_96") (class "Default")
      (node (ref "CLEAN188") (pin "1") (pinfunction "1_1") (pintype "passive"))
      (node (ref "CLEAN456") (pin "P$3") (pinfunction "1_P$3") (pintype "passive"))
    )
    (net (code "98") (name "/NEW_97") (class "Default")
      (node (ref "CLEAN189") (pin "1") (pinfunction "1_1") (pintype "passive"))
      (node (ref "CLEAN457") (pin "P$3") (pinfunction "1_P$3") (pintype "passive"))
    )
    (net (code "99") (name "/NEW_98") (class "Default")
      (node (ref "CLEAN198") (pin "1") (pinfunction "1_1") (pintype "passive"))
      (node (ref "CLEAN458") (pin "P$3") (pinfunction "1_P$3") (pintype "passive"))
    )
    (net (code "100") (name "/NEW_99") (class "Default")
      (node (ref "CLEAN199") (pin "1") (pinfunction "1_1") (pintype "passive"))
      (node (ref "CLEAN459") (pin "P$3") (pinfunction "1_P$3") (pintype "passive"))
    )
    (net (code "101") (name "/NEW_100") (class "Default")
      (node (ref "CLEAN208") (pin "1") (pinfunction "1_1") (pintype "passive"))
      (node (ref "CLEAN460") (pin "P$3") (pinfunction "1_P$3") (pintype "passive"))
    )
    (net (code "102") (name "/NEW_101") (class "Default")
      (node (ref "CLEAN209") (pin "1") (pinfunction "1_1") (pintype "passive"))
      (node (ref "CLEAN461") (pin "P$3") (pinfunction "1_P$3") (pintype "passive"))
    )
    (net (code "103") (name "/NEW_102") (class "Default")
      (node (ref "CLEAN218") (pin "1") (pinfunction "1_1") (pintype "passive"))
      (node (ref "CLEAN462") (pin "P$3") (pinfunction "1_P$3") (pintype "passive"))
    )
    (net (code "104") (name "/NEW_103") (class "Default")
      (node (ref "CLEAN219") (pin "1") (pinfunction "1_1") (pintype "passive"))
      (node (ref "CLEAN463") (pin "P$3") (pinfunction "1_P$3") (pintype "passive"))
    )
    (net (code "105") (name "/NEW_104") (class "Default")
      (node (ref "CLEAN228") (pin "1") (pinfunction "1_1") (pintype "passive"))
      (node (ref "CLEAN464") (pin "P$3") (pinfunction "1_P$3") (pintype "passive"))
    )
    (net (code "106") (name "/NEW_105") (class "Default")
      (node (ref "CLEAN229") (pin "1") (pinfunction "1_1") (pintype "passive"))
      (node (ref "CLEAN465") (pin "P$3") (pinfunction "1_P$3") (pintype "passive"))
    )
    (net (code "107") (name "/NEW_106") (class "Default")
      (node (ref "CLEAN238") (pin "1") (pinfunction "1_1") (pintype "passive"))
      (node (ref "CLEAN466") (pin "P$3") (pinfunction "1_P$3") (pintype "passive"))
    )
    (net (code "108") (name "/NEW_107") (class "Default")
      (node (ref "CLEAN239") (pin "1") (pinfunction "1_1") (pintype "passive"))
      (node (ref "CLEAN467") (pin "P$3") (pinfunction "1_P$3") (pintype "passive"))
    )
    (net (code "109") (name "/NEW_108") (class "Default")
      (node (ref "CLEAN248") (pin "1") (pinfunction "1_1") (pintype "passive"))
      (node (ref "CLEAN468") (pin "P$3") (pinfunction "1_P$3") (pintype "passive"))
    )
    (net (code "110") (name "/NEW_109") (class "Default")
      (node (ref "CLEAN249") (pin "1") (pinfunction "1_1") (pintype "passive"))
      (node (ref "CLEAN469") (pin "P$3") (pinfunction "1_P$3") (pintype "passive"))
    )
    (net (code "111") (name "/NEW_110") (class "Default")
      (node (ref "CLEAN258") (pin "1") (pinfunction "1_1") (pintype "passive"))
      (node (ref "CLEAN470") (pin "P$3") (pinfunction "1_P$3") (pintype "passive"))
    )
    (net (code "112") (name "/NEW_111") (class "Default")
      (node (ref "CLEAN259") (pin "1") (pinfunction "1_1") (pintype "passive"))
      (node (ref "CLEAN471") (pin "P$3") (pinfunction "1_P$3") (pintype "passive"))
    )
    (net (code "113") (name "/NEW_112") (class "Default")
      (node (ref "CLEAN268") (pin "1") (pinfunction "1_1") (pintype "passive"))
      (node (ref "CLEAN472") (pin "P$3") (pinfunction "1_P$3") (pintype "passive"))
    )
    (net (code "114") (name "/NEW_113") (class "Default")
      (node (ref "CLEAN269") (pin "1") (pinfunction "1_1") (pintype "passive"))
      (node (ref "CLEAN473") (pin "P$3") (pinfunction "1_P$3") (pintype "passive"))
    )
    (net (code "115") (name "/NEW_114") (class "Default")
      (node (ref "CLEAN278") (pin "1") (pinfunction "1_1") (pintype "passive"))
      (node (ref "CLEAN474") (pin "P$3") (pinfunction "1_P$3") (pintype "passive"))
    )
    (net (code "116") (name "/NEW_115") (class "Default")
      (node (ref "CLEAN279") (pin "1") (pinfunction "1_1") (pintype "passive"))
      (node (ref "CLEAN475") (pin "P$3") (pinfunction "1_P$3") (pintype "passive"))
    )
    (net (code "117") (name "/NEW_116") (class "Default")
      (node (ref "CLEAN288") (pin "1") (pinfunction "1_1") (pintype "passive"))
      (node (ref "CLEAN476") (pin "P$3") (pinfunction "1_P$3") (pintype "passive"))
    )
    (net (code "118") (name "/NEW_117") (class "Default")
      (node (ref "CLEAN289") (pin "1") (pinfunction "1_1") (pintype "passive"))
      (node (ref "CLEAN477") (pin "P$3") (pinfunction "1_P$3") (pintype "passive"))
    )
    (net (code "119") (name "/NEW_118") (class "Default")
      (node (ref "CLEAN298") (pin "1") (pinfunction "1_1") (pintype "passive"))
      (node (ref "CLEAN478") (pin "P$3") (pinfunction "1_P$3") (pintype "passive"))
    )
    (net (code "120") (name "/NEW_119") (class "Default")
      (node (ref "CLEAN299") (pin "1") (pinfunction "1_1") (pintype "passive"))
      (node (ref "CLEAN479") (pin "P$3") (pinfunction "1_P$3") (pintype "passive"))
    )
    (net (code "121") (name "/NEW_120") (class "Default")
      (node (ref "CLEAN0") (pin "1") (pinfunction "1_1") (pintype "passive"))
      (node (ref "CLEAN300") (pin "P$3") (pinfunction "1_P$3") (pintype "passive"))
    )
    (net (code "122") (name "/NEW_121") (class "Default")
      (node (ref "CLEAN1") (pin "1") (pinfunction "1_1") (pintype "passive"))
      (node (ref "CLEAN301") (pin "P$3") (pinfunction "1_P$3") (pintype "passive"))
    )
    (net (code "123") (name "/NEW_122") (class "Default")
      (node (ref "CLEAN10") (pin "1") (pinfunction "1_1") (pintype "passive"))
      (node (ref "CLEAN302") (pin "P$3") (pinfunction "1_P$3") (pintype "passive"))
    )
    (net (code "124") (name "/NEW_123") (class "Default")
      (node (ref "CLEAN11") (pin "1") (pinfunction "1_1") (pintype "passive"))
      (node (ref "CLEAN303") (pin "P$3") (pinfunction "1_P$3") (pintype "passive"))
    )
    (net (code "125") (name "/NEW_124") (class "Default")
      (node (ref "CLEAN20") (pin "1") (pinfunction "1_1") (pintype "passive"))
      (node (ref "CLEAN304") (pin "P$3") (pinfunction "1_P$3") (pintype "passive"))
    )
    (net (code "126") (name "/NEW_125") (class "Default")
      (node (ref "CLEAN21") (pin "1") (pinfunction "1_1") (pintype "passive"))
      (node (ref "CLEAN305") (pin "P$3") (pinfunction "1_P$3") (pintype "passive"))
    )
    (net (code "127") (name "/NEW_126") (class "Default")
      (node (ref "CLEAN30") (pin "1") (pinfunction "1_1") (pintype "passive"))
      (node (ref "CLEAN306") (pin "P$3") (pinfunction "1_P$3") (pintype "passive"))
    )
    (net (code "128") (name "/NEW_127") (class "Default")
      (node (ref "CLEAN307") (pin "P$3") (pinfunction "1_P$3") (pintype "passive"))
      (node (ref "CLEAN31") (pin "1") (pinfunction "1_1") (pintype "passive"))
    )
    (net (code "129") (name "/NEW_128") (class "Default")
      (node (ref "CLEAN308") (pin "P$3") (pinfunction "1_P$3") (pintype "passive"))
      (node (ref "CLEAN40") (pin "1") (pinfunction "1_1") (pintype "passive"))
    )
    (net (code "130") (name "/NEW_129") (class "Default")
      (node (ref "CLEAN309") (pin "P$3") (pinfunction "1_P$3") (pintype "passive"))
      (node (ref "CLEAN41") (pin "1") (pinfunction "1_1") (pintype "passive"))
    )
    (net (code "131") (name "/NEW_130") (class "Default")
      (node (ref "CLEAN310") (pin "P$3") (pinfunction "1_P$3") (pintype "passive"))
      (node (ref "CLEAN50") (pin "1") (pinfunction "1_1") (pintype "passive"))
    )
    (net (code "132") (name "/NEW_131") (class "Default")
      (node (ref "CLEAN311") (pin "P$3") (pinfunction "1_P$3") (pintype "passive"))
      (node (ref "CLEAN51") (pin "1") (pinfunction "1_1") (pintype "passive"))
    )
    (net (code "133") (name "/NEW_132") (class "Default")
      (node (ref "CLEAN312") (pin "P$3") (pinfunction "1_P$3") (pintype "passive"))
      (node (ref "CLEAN60") (pin "1") (pinfunction "1_1") (pintype "passive"))
    )
    (net (code "134") (name "/NEW_133") (class "Default")
      (node (ref "CLEAN313") (pin "P$3") (pinfunction "1_P$3") (pintype "passive"))
      (node (ref "CLEAN61") (pin "1") (pinfunction "1_1") (pintype "passive"))
    )
    (net (code "135") (name "/NEW_134") (class "Default")
      (node (ref "CLEAN314") (pin "P$3") (pinfunction "1_P$3") (pintype "passive"))
      (node (ref "CLEAN70") (pin "1") (pinfunction "1_1") (pintype "passive"))
    )
    (net (code "136") (name "/NEW_135") (class "Default")
      (node (ref "CLEAN315") (pin "P$3") (pinfunction "1_P$3") (pintype "passive"))
      (node (ref "CLEAN71") (pin "1") (pinfunction "1_1") (pintype "passive"))
    )
    (net (code "137") (name "/NEW_136") (class "Default")
      (node (ref "CLEAN316") (pin "P$3") (pinfunction "1_P$3") (pintype "passive"))
      (node (ref "CLEAN80") (pin "1") (pinfunction "1_1") (pintype "passive"))
    )
    (net (code "138") (name "/NEW_137") (class "Default")
      (node (ref "CLEAN317") (pin "P$3") (pinfunction "1_P$3") (pintype "passive"))
      (node (ref "CLEAN81") (pin "1") (pinfunction "1_1") (pintype "passive"))
    )
    (net (code "139") (name "/NEW_138") (class "Default")
      (node (ref "CLEAN318") (pin "P$3") (pinfunction "1_P$3") (pintype "passive"))
      (node (ref "CLEAN90") (pin "1") (pinfunction "1_1") (pintype "passive"))
    )
    (net (code "140") (name "/NEW_139") (class "Default")
      (node (ref "CLEAN319") (pin "P$3") (pinfunction "1_P$3") (pintype "passive"))
      (node (ref "CLEAN91") (pin "1") (pinfunction "1_1") (pintype "passive"))
    )
    (net (code "141") (name "/NEW_140") (class "Default")
      (node (ref "CLEAN100") (pin "1") (pinfunction "1_1") (pintype "passive"))
      (node (ref "CLEAN320") (pin "P$3") (pinfunction "1_P$3") (pintype "passive"))
    )
    (net (code "142") (name "/NEW_141") (class "Default")
      (node (ref "CLEAN101") (pin "1") (pinfunction "1_1") (pintype "passive"))
      (node (ref "CLEAN321") (pin "P$3") (pinfunction "1_P$3") (pintype "passive"))
    )
    (net (code "143") (name "/NEW_142") (class "Default")
      (node (ref "CLEAN110") (pin "1") (pinfunction "1_1") (pintype "passive"))
      (node (ref "CLEAN322") (pin "P$3") (pinfunction "1_P$3") (pintype "passive"))
    )
    (net (code "144") (name "/NEW_143") (class "Default")
      (node (ref "CLEAN111") (pin "1") (pinfunction "1_1") (pintype "passive"))
      (node (ref "CLEAN323") (pin "P$3") (pinfunction "1_P$3") (pintype "passive"))
    )
    (net (code "145") (name "/NEW_144") (class "Default")
      (node (ref "CLEAN120") (pin "1") (pinfunction "1_1") (pintype "passive"))
      (node (ref "CLEAN324") (pin "P$3") (pinfunction "1_P$3") (pintype "passive"))
    )
    (net (code "146") (name "/NEW_145") (class "Default")
      (node (ref "CLEAN121") (pin "1") (pinfunction "1_1") (pintype "passive"))
      (node (ref "CLEAN325") (pin "P$3") (pinfunction "1_P$3") (pintype "passive"))
    )
    (net (code "147") (name "/NEW_146") (class "Default")
      (node (ref "CLEAN130") (pin "1") (pinfunction "1_1") (pintype "passive"))
      (node (ref "CLEAN326") (pin "P$3") (pinfunction "1_P$3") (pintype "passive"))
    )
    (net (code "148") (name "/NEW_147") (class "Default")
      (node (ref "CLEAN131") (pin "1") (pinfunction "1_1") (pintype "passive"))
      (node (ref "CLEAN327") (pin "P$3") (pinfunction "1_P$3") (pintype "passive"))
    )
    (net (code "149") (name "/NEW_148") (class "Default")
      (node (ref "CLEAN140") (pin "1") (pinfunction "1_1") (pintype "passive"))
      (node (ref "CLEAN328") (pin "P$3") (pinfunction "1_P$3") (pintype "passive"))
    )
    (net (code "150") (name "/NEW_149") (class "Default")
      (node (ref "CLEAN141") (pin "1") (pinfunction "1_1") (pintype "passive"))
      (node (ref "CLEAN329") (pin "P$3") (pinfunction "1_P$3") (pintype "passive"))
    )
    (net (code "151") (name "/NEW_150") (class "Default")
      (node (ref "CLEAN150") (pin "1") (pinfunction "1_1") (pintype "passive"))
      (node (ref "CLEAN330") (pin "P$3") (pinfunction "1_P$3") (pintype "passive"))
    )
    (net (code "152") (name "/NEW_151") (class "Default")
      (node (ref "CLEAN151") (pin "1") (pinfunction "1_1") (pintype "passive"))
      (node (ref "CLEAN331") (pin "P$3") (pinfunction "1_P$3") (pintype "passive"))
    )
    (net (code "153") (name "/NEW_152") (class "Default")
      (node (ref "CLEAN160") (pin "1") (pinfunction "1_1") (pintype "passive"))
      (node (ref "CLEAN332") (pin "P$3") (pinfunction "1_P$3") (pintype "passive"))
    )
    (net (code "154") (name "/NEW_153") (class "Default")
      (node (ref "CLEAN161") (pin "1") (pinfunction "1_1") (pintype "passive"))
      (node (ref "CLEAN333") (pin "P$3") (pinfunction "1_P$3") (pintype "passive"))
    )
    (net (code "155") (name "/NEW_154") (class "Default")
      (node (ref "CLEAN170") (pin "1") (pinfunction "1_1") (pintype "passive"))
      (node (ref "CLEAN334") (pin "P$3") (pinfunction "1_P$3") (pintype "passive"))
    )
    (net (code "156") (name "/NEW_155") (class "Default")
      (node (ref "CLEAN171") (pin "1") (pinfunction "1_1") (pintype "passive"))
      (node (ref "CLEAN335") (pin "P$3") (pinfunction "1_P$3") (pintype "passive"))
    )
    (net (code "157") (name "/NEW_156") (class "Default")
      (node (ref "CLEAN180") (pin "1") (pinfunction "1_1") (pintype "passive"))
      (node (ref "CLEAN336") (pin "P$3") (pinfunction "1_P$3") (pintype "passive"))
    )
    (net (code "158") (name "/NEW_157") (class "Default")
      (node (ref "CLEAN181") (pin "1") (pinfunction "1_1") (pintype "passive"))
      (node (ref "CLEAN337") (pin "P$3") (pinfunction "1_P$3") (pintype "passive"))
    )
    (net (code "159") (name "/NEW_158") (class "Default")
      (node (ref "CLEAN190") (pin "1") (pinfunction "1_1") (pintype "passive"))
      (node (ref "CLEAN338") (pin "P$3") (pinfunction "1_P$3") (pintype "passive"))
    )
    (net (code "160") (name "/NEW_159") (class "Default")
      (node (ref "CLEAN191") (pin "1") (pinfunction "1_1") (pintype "passive"))
      (node (ref "CLEAN339") (pin "P$3") (pinfunction "1_P$3") (pintype "passive"))
    )
    (net (code "161") (name "/NEW_160") (class "Default")
      (node (ref "CLEAN200") (pin "1") (pinfunction "1_1") (pintype "passive"))
      (node (ref "CLEAN340") (pin "P$3") (pinfunction "1_P$3") (pintype "passive"))
    )
    (net (code "162") (name "/NEW_161") (class "Default")
      (node (ref "CLEAN201") (pin "1") (pinfunction "1_1") (pintype "passive"))
      (node (ref "CLEAN341") (pin "P$3") (pinfunction "1_P$3") (pintype "passive"))
    )
    (net (code "163") (name "/NEW_162") (class "Default")
      (node (ref "CLEAN210") (pin "1") (pinfunction "1_1") (pintype "passive"))
      (node (ref "CLEAN342") (pin "P$3") (pinfunction "1_P$3") (pintype "passive"))
    )
    (net (code "164") (name "/NEW_163") (class "Default")
      (node (ref "CLEAN211") (pin "1") (pinfunction "1_1") (pintype "passive"))
      (node (ref "CLEAN343") (pin "P$3") (pinfunction "1_P$3") (pintype "passive"))
    )
    (net (code "165") (name "/NEW_164") (class "Default")
      (node (ref "CLEAN220") (pin "1") (pinfunction "1_1") (pintype "passive"))
      (node (ref "CLEAN344") (pin "P$3") (pinfunction "1_P$3") (pintype "passive"))
    )
    (net (code "166") (name "/NEW_165") (class "Default")
      (node (ref "CLEAN221") (pin "1") (pinfunction "1_1") (pintype "passive"))
      (node (ref "CLEAN345") (pin "P$3") (pinfunction "1_P$3") (pintype "passive"))
    )
    (net (code "167") (name "/NEW_166") (class "Default")
      (node (ref "CLEAN230") (pin "1") (pinfunction "1_1") (pintype "passive"))
      (node (ref "CLEAN346") (pin "P$3") (pinfunction "1_P$3") (pintype "passive"))
    )
    (net (code "168") (name "/NEW_167") (class "Default")
      (node (ref "CLEAN231") (pin "1") (pinfunction "1_1") (pintype "passive"))
      (node (ref "CLEAN347") (pin "P$3") (pinfunction "1_P$3") (pintype "passive"))
    )
    (net (code "169") (name "/NEW_168") (class "Default")
      (node (ref "CLEAN240") (pin "1") (pinfunction "1_1") (pintype "passive"))
      (node (ref "CLEAN348") (pin "P$3") (pinfunction "1_P$3") (pintype "passive"))
    )
    (net (code "170") (name "/NEW_169") (class "Default")
      (node (ref "CLEAN241") (pin "1") (pinfunction "1_1") (pintype "passive"))
      (node (ref "CLEAN349") (pin "P$3") (pinfunction "1_P$3") (pintype "passive"))
    )
    (net (code "171") (name "/NEW_170") (class "Default")
      (node (ref "CLEAN250") (pin "1") (pinfunction "1_1") (pintype "passive"))
      (node (ref "CLEAN350") (pin "P$3") (pinfunction "1_P$3") (pintype "passive"))
    )
    (net (code "172") (name "/NEW_171") (class "Default")
      (node (ref "CLEAN251") (pin "1") (pinfunction "1_1") (pintype "passive"))
      (node (ref "CLEAN351") (pin "P$3") (pinfunction "1_P$3") (pintype "passive"))
    )
    (net (code "173") (name "/NEW_172") (class "Default")
      (node (ref "CLEAN260") (pin "1") (pinfunction "1_1") (pintype "passive"))
      (node (ref "CLEAN352") (pin "P$3") (pinfunction "1_P$3") (pintype "passive"))
    )
    (net (code "174") (name "/NEW_173") (class "Default")
      (node (ref "CLEAN261") (pin "1") (pinfunction "1_1") (pintype "passive"))
      (node (ref "CLEAN353") (pin "P$3") (pinfunction "1_P$3") (pintype "passive"))
    )
    (net (code "175") (name "/NEW_174") (class "Default")
      (node (ref "CLEAN270") (pin "1") (pinfunction "1_1") (pintype "passive"))
      (node (ref "CLEAN354") (pin "P$3") (pinfunction "1_P$3") (pintype "passive"))
    )
    (net (code "176") (name "/NEW_175") (class "Default")
      (node (ref "CLEAN271") (pin "1") (pinfunction "1_1") (pintype "passive"))
      (node (ref "CLEAN355") (pin "P$3") (pinfunction "1_P$3") (pintype "passive"))
    )
    (net (code "177") (name "/NEW_176") (class "Default")
      (node (ref "CLEAN280") (pin "1") (pinfunction "1_1") (pintype "passive"))
      (node (ref "CLEAN356") (pin "P$3") (pinfunction "1_P$3") (pintype "passive"))
    )
    (net (code "178") (name "/NEW_177") (class "Default")
      (node (ref "CLEAN281") (pin "1") (pinfunction "1_1") (pintype "passive"))
      (node (ref "CLEAN357") (pin "P$3") (pinfunction "1_P$3") (pintype "passive"))
    )
    (net (code "179") (name "/NEW_178") (class "Default")
      (node (ref "CLEAN290") (pin "1") (pinfunction "1_1") (pintype "passive"))
      (node (ref "CLEAN358") (pin "P$3") (pinfunction "1_P$3") (pintype "passive"))
    )
    (net (code "180") (name "/NEW_179") (class "Default")
      (node (ref "CLEAN291") (pin "1") (pinfunction "1_1") (pintype "passive"))
      (node (ref "CLEAN359") (pin "P$3") (pinfunction "1_P$3") (pintype "passive"))
    )
    (net (code "181") (name "/NEW_180") (class "Default")
      (node (ref "CLEAN2") (pin "1") (pinfunction "1_1") (pintype "passive"))
      (node (ref "CLEAN480") (pin "P$3") (pinfunction "1_P$3") (pintype "passive"))
    )
    (net (code "182") (name "/NEW_181") (class "Default")
      (node (ref "CLEAN3") (pin "1") (pinfunction "1_1") (pintype "passive"))
      (node (ref "CLEAN481") (pin "P$3") (pinfunction "1_P$3") (pintype "passive"))
    )
    (net (code "183") (name "/NEW_182") (class "Default")
      (node (ref "CLEAN12") (pin "1") (pinfunction "1_1") (pintype "passive"))
      (node (ref "CLEAN482") (pin "P$3") (pinfunction "1_P$3") (pintype "passive"))
    )
    (net (code "184") (name "/NEW_183") (class "Default")
      (node (ref "CLEAN13") (pin "1") (pinfunction "1_1") (pintype "passive"))
      (node (ref "CLEAN483") (pin "P$3") (pinfunction "1_P$3") (pintype "passive"))
    )
    (net (code "185") (name "/NEW_184") (class "Default")
      (node (ref "CLEAN22") (pin "1") (pinfunction "1_1") (pintype "passive"))
      (node (ref "CLEAN484") (pin "P$3") (pinfunction "1_P$3") (pintype "passive"))
    )
    (net (code "186") (name "/NEW_185") (class "Default")
      (node (ref "CLEAN23") (pin "1") (pinfunction "1_1") (pintype "passive"))
      (node (ref "CLEAN485") (pin "P$3") (pinfunction "1_P$3") (pintype "passive"))
    )
    (net (code "187") (name "/NEW_186") (class "Default")
      (node (ref "CLEAN32") (pin "1") (pinfunction "1_1") (pintype "passive"))
      (node (ref "CLEAN486") (pin "P$3") (pinfunction "1_P$3") (pintype "passive"))
    )
    (net (code "188") (name "/NEW_187") (class "Default")
      (node (ref "CLEAN33") (pin "1") (pinfunction "1_1") (pintype "passive"))
      (node (ref "CLEAN487") (pin "P$3") (pinfunction "1_P$3") (pintype "passive"))
    )
    (net (code "189") (name "/NEW_188") (class "Default")
      (node (ref "CLEAN42") (pin "1") (pinfunction "1_1") (pintype "passive"))
      (node (ref "CLEAN488") (pin "P$3") (pinfunction "1_P$3") (pintype "passive"))
    )
    (net (code "190") (name "/NEW_189") (class "Default")
      (node (ref "CLEAN43") (pin "1") (pinfunction "1_1") (pintype "passive"))
      (node (ref "CLEAN489") (pin "P$3") (pinfunction "1_P$3") (pintype "passive"))
    )
    (net (code "191") (name "/NEW_190") (class "Default")
      (node (ref "CLEAN490") (pin "P$3") (pinfunction "1_P$3") (pintype "passive"))
      (node (ref "CLEAN52") (pin "1") (pinfunction "1_1") (pintype "passive"))
    )
    (net (code "192") (name "/NEW_191") (class "Default")
      (node (ref "CLEAN491") (pin "P$3") (pinfunction "1_P$3") (pintype "passive"))
      (node (ref "CLEAN53") (pin "1") (pinfunction "1_1") (pintype "passive"))
    )
    (net (code "193") (name "/NEW_192") (class "Default")
      (node (ref "CLEAN492") (pin "P$3") (pinfunction "1_P$3") (pintype "passive"))
      (node (ref "CLEAN62") (pin "1") (pinfunction "1_1") (pintype "passive"))
    )
    (net (code "194") (name "/NEW_193") (class "Default")
      (node (ref "CLEAN493") (pin "P$3") (pinfunction "1_P$3") (pintype "passive"))
      (node (ref "CLEAN63") (pin "1") (pinfunction "1_1") (pintype "passive"))
    )
    (net (code "195") (name "/NEW_194") (class "Default")
      (node (ref "CLEAN494") (pin "P$3") (pinfunction "1_P$3") (pintype "passive"))
      (node (ref "CLEAN72") (pin "1") (pinfunction "1_1") (pintype "passive"))
    )
    (net (code "196") (name "/NEW_195") (class "Default")
      (node (ref "CLEAN495") (pin "P$3") (pinfunction "1_P$3") (pintype "passive"))
      (node (ref "CLEAN73") (pin "1") (pinfunction "1_1") (pintype "passive"))
    )
    (net (code "197") (name "/NEW_196") (class "Default")
      (node (ref "CLEAN496") (pin "P$3") (pinfunction "1_P$3") (pintype "passive"))
      (node (ref "CLEAN82") (pin "1") (pinfunction "1_1") (pintype "passive"))
    )
    (net (code "198") (name "/NEW_197") (class "Default")
      (node (ref "CLEAN497") (pin "P$3") (pinfunction "1_P$3") (pintype "passive"))
      (node (ref "CLEAN83") (pin "1") (pinfunction "1_1") (pintype "passive"))
    )
    (net (code "199") (name "/NEW_198") (class "Default")
      (node (ref "CLEAN498") (pin "P$3") (pinfunction "1_P$3") (pintype "passive"))
      (node (ref "CLEAN92") (pin "1") (pinfunction "1_1") (pintype "passive"))
    )
    (net (code "200") (name "/NEW_199") (class "Default")
      (node (ref "CLEAN499") (pin "P$3") (pinfunction "1_P$3") (pintype "passive"))
      (node (ref "CLEAN93") (pin "1") (pinfunction "1_1") (pintype "passive"))
    )
    (net (code "201") (name "/NEW_200") (class "Default")
      (node (ref "CLEAN102") (pin "1") (pinfunction "1_1") (pintype "passive"))
      (node (ref "CLEAN500") (pin "P$3") (pinfunction "1_P$3") (pintype "passive"))
    )
    (net (code "202") (name "/NEW_201") (class "Default")
      (node (ref "CLEAN103") (pin "1") (pinfunction "1_1") (pintype "passive"))
      (node (ref "CLEAN501") (pin "P$3") (pinfunction "1_P$3") (pintype "passive"))
    )
    (net (code "203") (name "/NEW_202") (class "Default")
      (node (ref "CLEAN112") (pin "1") (pinfunction "1_1") (pintype "passive"))
      (node (ref "CLEAN502") (pin "P$3") (pinfunction "1_P$3") (pintype "passive"))
    )
    (net (code "204") (name "/NEW_203") (class "Default")
      (node (ref "CLEAN113") (pin "1") (pinfunction "1_1") (pintype "passive"))
      (node (ref "CLEAN503") (pin "P$3") (pinfunction "1_P$3") (pintype "passive"))
    )
    (net (code "205") (name "/NEW_204") (class "Default")
      (node (ref "CLEAN122") (pin "1") (pinfunction "1_1") (pintype "passive"))
      (node (ref "CLEAN504") (pin "P$3") (pinfunction "1_P$3") (pintype "passive"))
    )
    (net (code "206") (name "/NEW_205") (class "Default")
      (node (ref "CLEAN123") (pin "1") (pinfunction "1_1") (pintype "passive"))
      (node (ref "CLEAN505") (pin "P$3") (pinfunction "1_P$3") (pintype "passive"))
    )
    (net (code "207") (name "/NEW_206") (class "Default")
      (node (ref "CLEAN132") (pin "1") (pinfunction "1_1") (pintype "passive"))
      (node (ref "CLEAN506") (pin "P$3") (pinfunction "1_P$3") (pintype "passive"))
    )
    (net (code "208") (name "/NEW_207") (class "Default")
      (node (ref "CLEAN133") (pin "1") (pinfunction "1_1") (pintype "passive"))
      (node (ref "CLEAN507") (pin "P$3") (pinfunction "1_P$3") (pintype "passive"))
    )
    (net (code "209") (name "/NEW_208") (class "Default")
      (node (ref "CLEAN142") (pin "1") (pinfunction "1_1") (pintype "passive"))
      (node (ref "CLEAN508") (pin "P$3") (pinfunction "1_P$3") (pintype "passive"))
    )
    (net (code "210") (name "/NEW_209") (class "Default")
      (node (ref "CLEAN143") (pin "1") (pinfunction "1_1") (pintype "passive"))
      (node (ref "CLEAN509") (pin "P$3") (pinfunction "1_P$3") (pintype "passive"))
    )
    (net (code "211") (name "/NEW_210") (class "Default")
      (node (ref "CLEAN152") (pin "1") (pinfunction "1_1") (pintype "passive"))
      (node (ref "CLEAN510") (pin "P$3") (pinfunction "1_P$3") (pintype "passive"))
    )
    (net (code "212") (name "/NEW_211") (class "Default")
      (node (ref "CLEAN153") (pin "1") (pinfunction "1_1") (pintype "passive"))
      (node (ref "CLEAN511") (pin "P$3") (pinfunction "1_P$3") (pintype "passive"))
    )
    (net (code "213") (name "/NEW_212") (class "Default")
      (node (ref "CLEAN162") (pin "1") (pinfunction "1_1") (pintype "passive"))
      (node (ref "CLEAN512") (pin "P$3") (pinfunction "1_P$3") (pintype "passive"))
    )
    (net (code "214") (name "/NEW_213") (class "Default")
      (node (ref "CLEAN163") (pin "1") (pinfunction "1_1") (pintype "passive"))
      (node (ref "CLEAN513") (pin "P$3") (pinfunction "1_P$3") (pintype "passive"))
    )
    (net (code "215") (name "/NEW_214") (class "Default")
      (node (ref "CLEAN172") (pin "1") (pinfunction "1_1") (pintype "passive"))
      (node (ref "CLEAN514") (pin "P$3") (pinfunction "1_P$3") (pintype "passive"))
    )
    (net (code "216") (name "/NEW_215") (class "Default")
      (node (ref "CLEAN173") (pin "1") (pinfunction "1_1") (pintype "passive"))
      (node (ref "CLEAN515") (pin "P$3") (pinfunction "1_P$3") (pintype "passive"))
    )
    (net (code "217") (name "/NEW_216") (class "Default")
      (node (ref "CLEAN182") (pin "1") (pinfunction "1_1") (pintype "passive"))
      (node (ref "CLEAN516") (pin "P$3") (pinfunction "1_P$3") (pintype "passive"))
    )
    (net (code "218") (name "/NEW_217") (class "Default")
      (node (ref "CLEAN183") (pin "1") (pinfunction "1_1") (pintype "passive"))
      (node (ref "CLEAN517") (pin "P$3") (pinfunction "1_P$3") (pintype "passive"))
    )
    (net (code "219") (name "/NEW_218") (class "Default")
      (node (ref "CLEAN192") (pin "1") (pinfunction "1_1") (pintype "passive"))
      (node (ref "CLEAN518") (pin "P$3") (pinfunction "1_P$3") (pintype "passive"))
    )
    (net (code "220") (name "/NEW_219") (class "Default")
      (node (ref "CLEAN193") (pin "1") (pinfunction "1_1") (pintype "passive"))
      (node (ref "CLEAN519") (pin "P$3") (pinfunction "1_P$3") (pintype "passive"))
    )
    (net (code "221") (name "/NEW_220") (class "Default")
      (node (ref "CLEAN202") (pin "1") (pinfunction "1_1") (pintype "passive"))
      (node (ref "CLEAN520") (pin "P$3") (pinfunction "1_P$3") (pintype "passive"))
    )
    (net (code "222") (name "/NEW_221") (class "Default")
      (node (ref "CLEAN203") (pin "1") (pinfunction "1_1") (pintype "passive"))
      (node (ref "CLEAN521") (pin "P$3") (pinfunction "1_P$3") (pintype "passive"))
    )
    (net (code "223") (name "/NEW_222") (class "Default")
      (node (ref "CLEAN212") (pin "1") (pinfunction "1_1") (pintype "passive"))
      (node (ref "CLEAN522") (pin "P$3") (pinfunction "1_P$3") (pintype "passive"))
    )
    (net (code "224") (name "/NEW_223") (class "Default")
      (node (ref "CLEAN213") (pin "1") (pinfunction "1_1") (pintype "passive"))
      (node (ref "CLEAN523") (pin "P$3") (pinfunction "1_P$3") (pintype "passive"))
    )
    (net (code "225") (name "/NEW_224") (class "Default")
      (node (ref "CLEAN222") (pin "1") (pinfunction "1_1") (pintype "passive"))
      (node (ref "CLEAN524") (pin "P$3") (pinfunction "1_P$3") (pintype "passive"))
    )
    (net (code "226") (name "/NEW_225") (class "Default")
      (node (ref "CLEAN223") (pin "1") (pinfunction "1_1") (pintype "passive"))
      (node (ref "CLEAN525") (pin "P$3") (pinfunction "1_P$3") (pintype "passive"))
    )
    (net (code "227") (name "/NEW_226") (class "Default")
      (node (ref "CLEAN232") (pin "1") (pinfunction "1_1") (pintype "passive"))
      (node (ref "CLEAN526") (pin "P$3") (pinfunction "1_P$3") (pintype "passive"))
    )
    (net (code "228") (name "/NEW_227") (class "Default")
      (node (ref "CLEAN233") (pin "1") (pinfunction "1_1") (pintype "passive"))
      (node (ref "CLEAN527") (pin "P$3") (pinfunction "1_P$3") (pintype "passive"))
    )
    (net (code "229") (name "/NEW_228") (class "Default")
      (node (ref "CLEAN242") (pin "1") (pinfunction "1_1") (pintype "passive"))
      (node (ref "CLEAN528") (pin "P$3") (pinfunction "1_P$3") (pintype "passive"))
    )
    (net (code "230") (name "/NEW_229") (class "Default")
      (node (ref "CLEAN243") (pin "1") (pinfunction "1_1") (pintype "passive"))
      (node (ref "CLEAN529") (pin "P$3") (pinfunction "1_P$3") (pintype "passive"))
    )
    (net (code "231") (name "/NEW_230") (class "Default")
      (node (ref "CLEAN252") (pin "1") (pinfunction "1_1") (pintype "passive"))
      (node (ref "CLEAN530") (pin "P$3") (pinfunction "1_P$3") (pintype "passive"))
    )
    (net (code "232") (name "/NEW_231") (class "Default")
      (node (ref "CLEAN253") (pin "1") (pinfunction "1_1") (pintype "passive"))
      (node (ref "CLEAN531") (pin "P$3") (pinfunction "1_P$3") (pintype "passive"))
    )
    (net (code "233") (name "/NEW_232") (class "Default")
      (node (ref "CLEAN262") (pin "1") (pinfunction "1_1") (pintype "passive"))
      (node (ref "CLEAN532") (pin "P$3") (pinfunction "1_P$3") (pintype "passive"))
    )
    (net (code "234") (name "/NEW_233") (class "Default")
      (node (ref "CLEAN263") (pin "1") (pinfunction "1_1") (pintype "passive"))
      (node (ref "CLEAN533") (pin "P$3") (pinfunction "1_P$3") (pintype "passive"))
    )
    (net (code "235") (name "/NEW_234") (class "Default")
      (node (ref "CLEAN272") (pin "1") (pinfunction "1_1") (pintype "passive"))
      (node (ref "CLEAN534") (pin "P$3") (pinfunction "1_P$3") (pintype "passive"))
    )
    (net (code "236") (name "/NEW_235") (class "Default")
      (node (ref "CLEAN273") (pin "1") (pinfunction "1_1") (pintype "passive"))
      (node (ref "CLEAN535") (pin "P$3") (pinfunction "1_P$3") (pintype "passive"))
    )
    (net (code "237") (name "/NEW_236") (class "Default")
      (node (ref "CLEAN282") (pin "1") (pinfunction "1_1") (pintype "passive"))
      (node (ref "CLEAN536") (pin "P$3") (pinfunction "1_P$3") (pintype "passive"))
    )
    (net (code "238") (name "/NEW_237") (class "Default")
      (node (ref "CLEAN283") (pin "1") (pinfunction "1_1") (pintype "passive"))
      (node (ref "CLEAN537") (pin "P$3") (pinfunction "1_P$3") (pintype "passive"))
    )
    (net (code "239") (name "/NEW_238") (class "Default")
      (node (ref "CLEAN292") (pin "1") (pinfunction "1_1") (pintype "passive"))
      (node (ref "CLEAN538") (pin "P$3") (pinfunction "1_P$3") (pintype "passive"))
    )
    (net (code "240") (name "/NEW_239") (class "Default")
      (node (ref "CLEAN293") (pin "1") (pinfunction "1_1") (pintype "passive"))
      (node (ref "CLEAN539") (pin "P$3") (pinfunction "1_P$3") (pintype "passive"))
    )
    (net (code "241") (name "/NEW_240") (class "Default")
      (node (ref "CLEAN4") (pin "1") (pinfunction "1_1") (pintype "passive"))
      (node (ref "CLEAN560") (pin "P$3") (pinfunction "1_P$3") (pintype "passive"))
    )
    (net (code "242") (name "/NEW_241") (class "Default")
      (node (ref "CLEAN14") (pin "1") (pinfunction "1_1") (pintype "passive"))
      (node (ref "CLEAN561") (pin "P$3") (pinfunction "1_P$3") (pintype "passive"))
    )
    (net (code "243") (name "/NEW_242") (class "Default")
      (node (ref "CLEAN24") (pin "1") (pinfunction "1_1") (pintype "passive"))
      (node (ref "CLEAN562") (pin "P$3") (pinfunction "1_P$3") (pintype "passive"))
    )
    (net (code "244") (name "/NEW_243") (class "Default")
      (node (ref "CLEAN34") (pin "1") (pinfunction "1_1") (pintype "passive"))
      (node (ref "CLEAN563") (pin "P$3") (pinfunction "1_P$3") (pintype "passive"))
    )
    (net (code "245") (name "/NEW_244") (class "Default")
      (node (ref "CLEAN44") (pin "1") (pinfunction "1_1") (pintype "passive"))
      (node (ref "CLEAN564") (pin "P$3") (pinfunction "1_P$3") (pintype "passive"))
    )
    (net (code "246") (name "/NEW_245") (class "Default")
      (node (ref "CLEAN54") (pin "1") (pinfunction "1_1") (pintype "passive"))
      (node (ref "CLEAN565") (pin "P$3") (pinfunction "1_P$3") (pintype "passive"))
    )
    (net (code "247") (name "/NEW_246") (class "Default")
      (node (ref "CLEAN566") (pin "P$3") (pinfunction "1_P$3") (pintype "passive"))
      (node (ref "CLEAN64") (pin "1") (pinfunction "1_1") (pintype "passive"))
    )
    (net (code "248") (name "/NEW_247") (class "Default")
      (node (ref "CLEAN567") (pin "P$3") (pinfunction "1_P$3") (pintype "passive"))
      (node (ref "CLEAN74") (pin "1") (pinfunction "1_1") (pintype "passive"))
    )
    (net (code "249") (name "/NEW_248") (class "Default")
      (node (ref "CLEAN568") (pin "P$3") (pinfunction "1_P$3") (pintype "passive"))
      (node (ref "CLEAN84") (pin "1") (pinfunction "1_1") (pintype "passive"))
    )
    (net (code "250") (name "/NEW_249") (class "Default")
      (node (ref "CLEAN569") (pin "P$3") (pinfunction "1_P$3") (pintype "passive"))
      (node (ref "CLEAN94") (pin "1") (pinfunction "1_1") (pintype "passive"))
    )
    (net (code "251") (name "/NEW_250") (class "Default")
      (node (ref "CLEAN104") (pin "1") (pinfunction "1_1") (pintype "passive"))
      (node (ref "CLEAN570") (pin "P$3") (pinfunction "1_P$3") (pintype "passive"))
    )
    (net (code "252") (name "/NEW_251") (class "Default")
      (node (ref "CLEAN114") (pin "1") (pinfunction "1_1") (pintype "passive"))
      (node (ref "CLEAN571") (pin "P$3") (pinfunction "1_P$3") (pintype "passive"))
    )
    (net (code "253") (name "/NEW_252") (class "Default")
      (node (ref "CLEAN124") (pin "1") (pinfunction "1_1") (pintype "passive"))
      (node (ref "CLEAN572") (pin "P$3") (pinfunction "1_P$3") (pintype "passive"))
    )
    (net (code "254") (name "/NEW_253") (class "Default")
      (node (ref "CLEAN134") (pin "1") (pinfunction "1_1") (pintype "passive"))
      (node (ref "CLEAN573") (pin "P$3") (pinfunction "1_P$3") (pintype "passive"))
    )
    (net (code "255") (name "/NEW_254") (class "Default")
      (node (ref "CLEAN144") (pin "1") (pinfunction "1_1") (pintype "passive"))
      (node (ref "CLEAN574") (pin "P$3") (pinfunction "1_P$3") (pintype "passive"))
    )
    (net (code "256") (name "/NEW_255") (class "Default")
      (node (ref "CLEAN154") (pin "1") (pinfunction "1_1") (pintype "passive"))
      (node (ref "CLEAN575") (pin "P$3") (pinfunction "1_P$3") (pintype "passive"))
    )
    (net (code "257") (name "/NEW_256") (class "Default")
      (node (ref "CLEAN164") (pin "1") (pinfunction "1_1") (pintype "passive"))
      (node (ref "CLEAN576") (pin "P$3") (pinfunction "1_P$3") (pintype "passive"))
    )
    (net (code "258") (name "/NEW_257") (class "Default")
      (node (ref "CLEAN174") (pin "1") (pinfunction "1_1") (pintype "passive"))
      (node (ref "CLEAN577") (pin "P$3") (pinfunction "1_P$3") (pintype "passive"))
    )
    (net (code "259") (name "/NEW_258") (class "Default")
      (node (ref "CLEAN184") (pin "1") (pinfunction "1_1") (pintype "passive"))
      (node (ref "CLEAN578") (pin "P$3") (pinfunction "1_P$3") (pintype "passive"))
    )
    (net (code "260") (name "/NEW_259") (class "Default")
      (node (ref "CLEAN194") (pin "1") (pinfunction "1_1") (pintype "passive"))
      (node (ref "CLEAN579") (pin "P$3") (pinfunction "1_P$3") (pintype "passive"))
    )
    (net (code "261") (name "/NEW_260") (class "Default")
      (node (ref "CLEAN294") (pin "1") (pinfunction "1_1") (pintype "passive"))
      (node (ref "CLEAN590") (pin "P$3") (pinfunction "1_P$3") (pintype "passive"))
    )
    (net (code "262") (name "/NEW_261") (class "Default")
      (node (ref "CLEAN284") (pin "1") (pinfunction "1_1") (pintype "passive"))
      (node (ref "CLEAN591") (pin "P$3") (pinfunction "1_P$3") (pintype "passive"))
    )
    (net (code "263") (name "/NEW_262") (class "Default")
      (node (ref "CLEAN274") (pin "1") (pinfunction "1_1") (pintype "passive"))
      (node (ref "CLEAN592") (pin "P$3") (pinfunction "1_P$3") (pintype "passive"))
    )
    (net (code "264") (name "/NEW_263") (class "Default")
      (node (ref "CLEAN264") (pin "1") (pinfunction "1_1") (pintype "passive"))
      (node (ref "CLEAN593") (pin "P$3") (pinfunction "1_P$3") (pintype "passive"))
    )
    (net (code "265") (name "/NEW_264") (class "Default")
      (node (ref "CLEAN254") (pin "1") (pinfunction "1_1") (pintype "passive"))
      (node (ref "CLEAN594") (pin "P$3") (pinfunction "1_P$3") (pintype "passive"))
    )
    (net (code "266") (name "/NEW_265") (class "Default")
      (node (ref "CLEAN244") (pin "1") (pinfunction "1_1") (pintype "passive"))
      (node (ref "CLEAN595") (pin "P$3") (pinfunction "1_P$3") (pintype "passive"))
    )
    (net (code "267") (name "/NEW_266") (class "Default")
      (node (ref "CLEAN234") (pin "1") (pinfunction "1_1") (pintype "passive"))
      (node (ref "CLEAN596") (pin "P$3") (pinfunction "1_P$3") (pintype "passive"))
    )
    (net (code "268") (name "/NEW_267") (class "Default")
      (node (ref "CLEAN224") (pin "1") (pinfunction "1_1") (pintype "passive"))
      (node (ref "CLEAN597") (pin "P$3") (pinfunction "1_P$3") (pintype "passive"))
    )
    (net (code "269") (name "/NEW_268") (class "Default")
      (node (ref "CLEAN214") (pin "1") (pinfunction "1_1") (pintype "passive"))
      (node (ref "CLEAN598") (pin "P$3") (pinfunction "1_P$3") (pintype "passive"))
    )
    (net (code "270") (name "/NEW_269") (class "Default")
      (node (ref "CLEAN204") (pin "1") (pinfunction "1_1") (pintype "passive"))
      (node (ref "CLEAN599") (pin "P$3") (pinfunction "1_P$3") (pintype "passive"))
    )
    (net (code "271") (name "/NEW_270") (class "Default")
      (node (ref "CLEAN195") (pin "1") (pinfunction "1_1") (pintype "passive"))
      (node (ref "CLEAN540") (pin "P$3") (pinfunction "1_P$3") (pintype "passive"))
    )
    (net (code "272") (name "/NEW_271") (class "Default")
      (node (ref "CLEAN185") (pin "1") (pinfunction "1_1") (pintype "passive"))
      (node (ref "CLEAN541") (pin "P$3") (pinfunction "1_P$3") (pintype "passive"))
    )
    (net (code "273") (name "/NEW_272") (class "Default")
      (node (ref "CLEAN175") (pin "1") (pinfunction "1_1") (pintype "passive"))
      (node (ref "CLEAN542") (pin "P$3") (pinfunction "1_P$3") (pintype "passive"))
    )
    (net (code "274") (name "/NEW_273") (class "Default")
      (node (ref "CLEAN165") (pin "1") (pinfunction "1_1") (pintype "passive"))
      (node (ref "CLEAN543") (pin "P$3") (pinfunction "1_P$3") (pintype "passive"))
    )
    (net (code "275") (name "/NEW_274") (class "Default")
      (node (ref "CLEAN155") (pin "1") (pinfunction "1_1") (pintype "passive"))
      (node (ref "CLEAN544") (pin "P$3") (pinfunction "1_P$3") (pintype "passive"))
    )
    (net (code "276") (name "/NEW_275") (class "Default")
      (node (ref "CLEAN145") (pin "1") (pinfunction "1_1") (pintype "passive"))
      (node (ref "CLEAN545") (pin "P$3") (pinfunction "1_P$3") (pintype "passive"))
    )
    (net (code "277") (name "/NEW_276") (class "Default")
      (node (ref "CLEAN135") (pin "1") (pinfunction "1_1") (pintype "passive"))
      (node (ref "CLEAN546") (pin "P$3") (pinfunction "1_P$3") (pintype "passive"))
    )
    (net (code "278") (name "/NEW_277") (class "Default")
      (node (ref "CLEAN125") (pin "1") (pinfunction "1_1") (pintype "passive"))
      (node (ref "CLEAN547") (pin "P$3") (pinfunction "1_P$3") (pintype "passive"))
    )
    (net (code "279") (name "/NEW_278") (class "Default")
      (node (ref "CLEAN115") (pin "1") (pinfunction "1_1") (pintype "passive"))
      (node (ref "CLEAN548") (pin "P$3") (pinfunction "1_P$3") (pintype "passive"))
    )
    (net (code "280") (name "/NEW_279") (class "Default")
      (node (ref "CLEAN105") (pin "1") (pinfunction "1_1") (pintype "passive"))
      (node (ref "CLEAN549") (pin "P$3") (pinfunction "1_P$3") (pintype "passive"))
    )
    (net (code "281") (name "/NEW_280") (class "Default")
      (node (ref "CLEAN550") (pin "P$3") (pinfunction "1_P$3") (pintype "passive"))
      (node (ref "CLEAN95") (pin "1") (pinfunction "1_1") (pintype "passive"))
    )
    (net (code "282") (name "/NEW_281") (class "Default")
      (node (ref "CLEAN551") (pin "P$3") (pinfunction "1_P$3") (pintype "passive"))
      (node (ref "CLEAN85") (pin "1") (pinfunction "1_1") (pintype "passive"))
    )
    (net (code "283") (name "/NEW_282") (class "Default")
      (node (ref "CLEAN552") (pin "P$3") (pinfunction "1_P$3") (pintype "passive"))
      (node (ref "CLEAN75") (pin "1") (pinfunction "1_1") (pintype "passive"))
    )
    (net (code "284") (name "/NEW_283") (class "Default")
      (node (ref "CLEAN553") (pin "P$3") (pinfunction "1_P$3") (pintype "passive"))
      (node (ref "CLEAN65") (pin "1") (pinfunction "1_1") (pintype "passive"))
    )
    (net (code "285") (name "/NEW_284") (class "Default")
      (node (ref "CLEAN55") (pin "1") (pinfunction "1_1") (pintype "passive"))
      (node (ref "CLEAN554") (pin "P$3") (pinfunction "1_P$3") (pintype "passive"))
    )
    (net (code "286") (name "/NEW_285") (class "Default")
      (node (ref "CLEAN45") (pin "1") (pinfunction "1_1") (pintype "passive"))
      (node (ref "CLEAN555") (pin "P$3") (pinfunction "1_P$3") (pintype "passive"))
    )
    (net (code "287") (name "/NEW_286") (class "Default")
      (node (ref "CLEAN35") (pin "1") (pinfunction "1_1") (pintype "passive"))
      (node (ref "CLEAN556") (pin "P$3") (pinfunction "1_P$3") (pintype "passive"))
    )
    (net (code "288") (name "/NEW_287") (class "Default")
      (node (ref "CLEAN25") (pin "1") (pinfunction "1_1") (pintype "passive"))
      (node (ref "CLEAN557") (pin "P$3") (pinfunction "1_P$3") (pintype "passive"))
    )
    (net (code "289") (name "/NEW_288") (class "Default")
      (node (ref "CLEAN15") (pin "1") (pinfunction "1_1") (pintype "passive"))
      (node (ref "CLEAN558") (pin "P$3") (pinfunction "1_P$3") (pintype "passive"))
    )
    (net (code "290") (name "/NEW_289") (class "Default")
      (node (ref "CLEAN5") (pin "1") (pinfunction "1_1") (pintype "passive"))
      (node (ref "CLEAN559") (pin "P$3") (pinfunction "1_P$3") (pintype "passive"))
    )
    (net (code "291") (name "/NEW_290") (class "Default")
      (node (ref "CLEAN205") (pin "1") (pinfunction "1_1") (pintype "passive"))
      (node (ref "CLEAN580") (pin "P$3") (pinfunction "1_P$3") (pintype "passive"))
    )
    (net (code "292") (name "/NEW_291") (class "Default")
      (node (ref "CLEAN215") (pin "1") (pinfunction "1_1") (pintype "passive"))
      (node (ref "CLEAN581") (pin "P$3") (pinfunction "1_P$3") (pintype "passive"))
    )
    (net (code "293") (name "/NEW_292") (class "Default")
      (node (ref "CLEAN225") (pin "1") (pinfunction "1_1") (pintype "passive"))
      (node (ref "CLEAN582") (pin "P$3") (pinfunction "1_P$3") (pintype "passive"))
    )
    (net (code "294") (name "/NEW_293") (class "Default")
      (node (ref "CLEAN235") (pin "1") (pinfunction "1_1") (pintype "passive"))
      (node (ref "CLEAN583") (pin "P$3") (pinfunction "1_P$3") (pintype "passive"))
    )
    (net (code "295") (name "/NEW_294") (class "Default")
      (node (ref "CLEAN245") (pin "1") (pinfunction "1_1") (pintype "passive"))
      (node (ref "CLEAN584") (pin "P$3") (pinfunction "1_P$3") (pintype "passive"))
    )
    (net (code "296") (name "/NEW_295") (class "Default")
      (node (ref "CLEAN255") (pin "1") (pinfunction "1_1") (pintype "passive"))
      (node (ref "CLEAN585") (pin "P$3") (pinfunction "1_P$3") (pintype "passive"))
    )
    (net (code "297") (name "/NEW_296") (class "Default")
      (node (ref "CLEAN265") (pin "1") (pinfunction "1_1") (pintype "passive"))
      (node (ref "CLEAN586") (pin "P$3") (pinfunction "1_P$3") (pintype "passive"))
    )
    (net (code "298") (name "/NEW_297") (class "Default")
      (node (ref "CLEAN275") (pin "1") (pinfunction "1_1") (pintype "passive"))
      (node (ref "CLEAN587") (pin "P$3") (pinfunction "1_P$3") (pintype "passive"))
    )
    (net (code "299") (name "/NEW_298") (class "Default")
      (node (ref "CLEAN285") (pin "1") (pinfunction "1_1") (pintype "passive"))
      (node (ref "CLEAN588") (pin "P$3") (pinfunction "1_P$3") (pintype "passive"))
    )
    (net (code "300") (name "/NEW_299") (class "Default")
      (node (ref "CLEAN295") (pin "1") (pinfunction "1_1") (pintype "passive"))
      (node (ref "CLEAN589") (pin "P$3") (pinfunction "1_P$3") (pintype "passive"))
    )
  )
)
